# Sheet1.net
KiCad netlist of a schematic drawn in Altium Designer
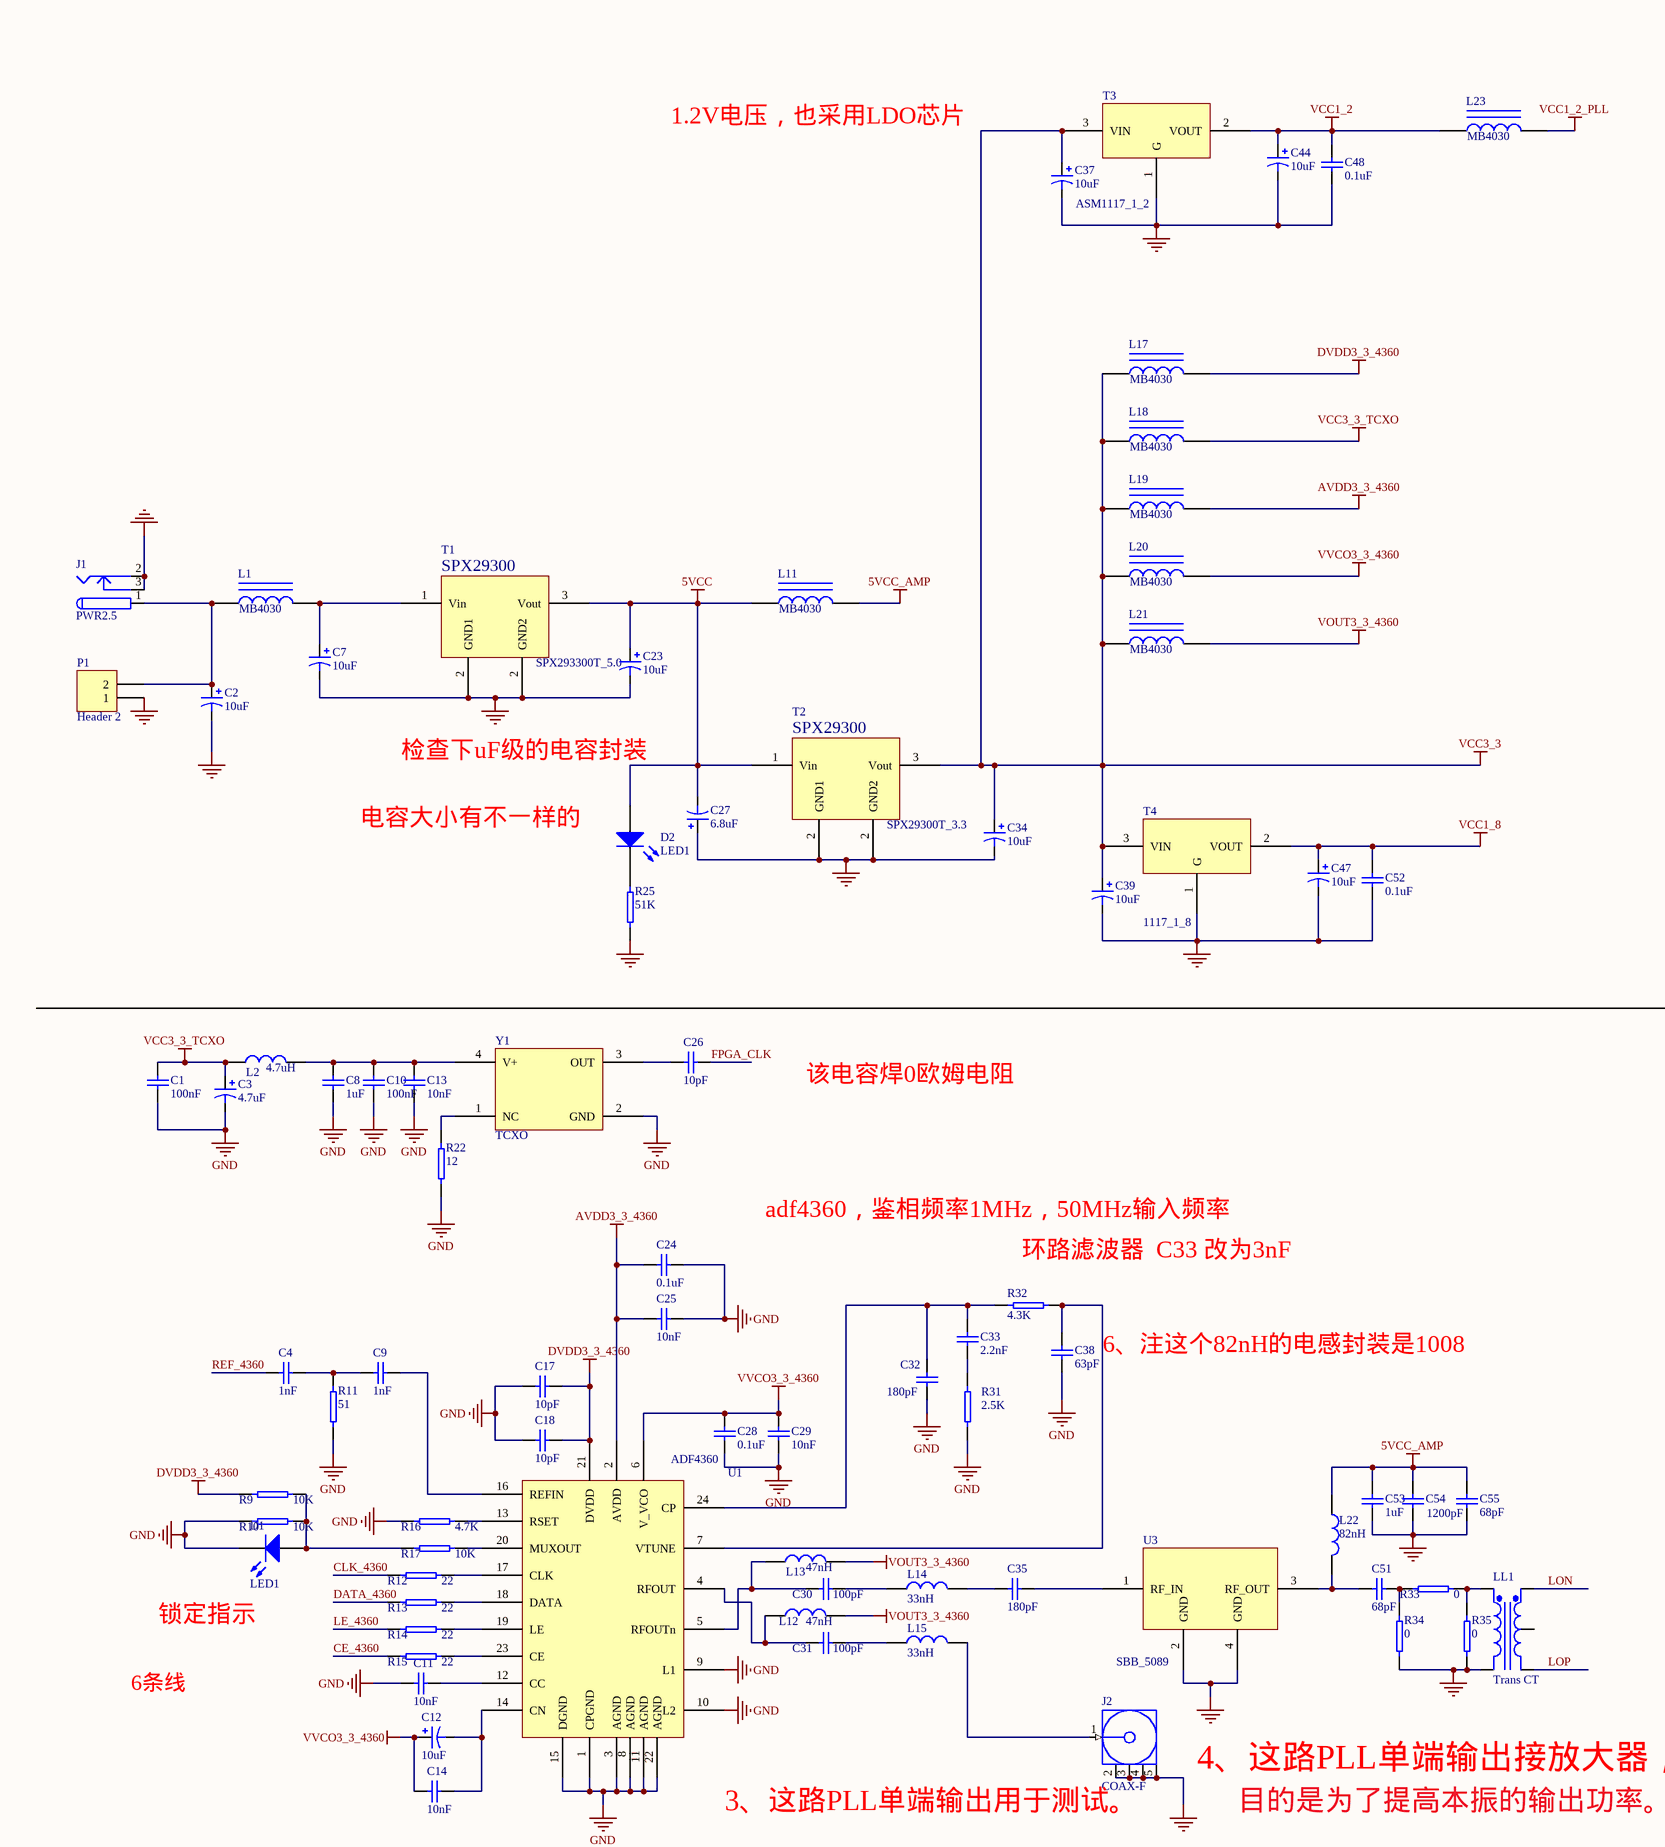
[diagram p0: Sheet1.SchDoc, top left]
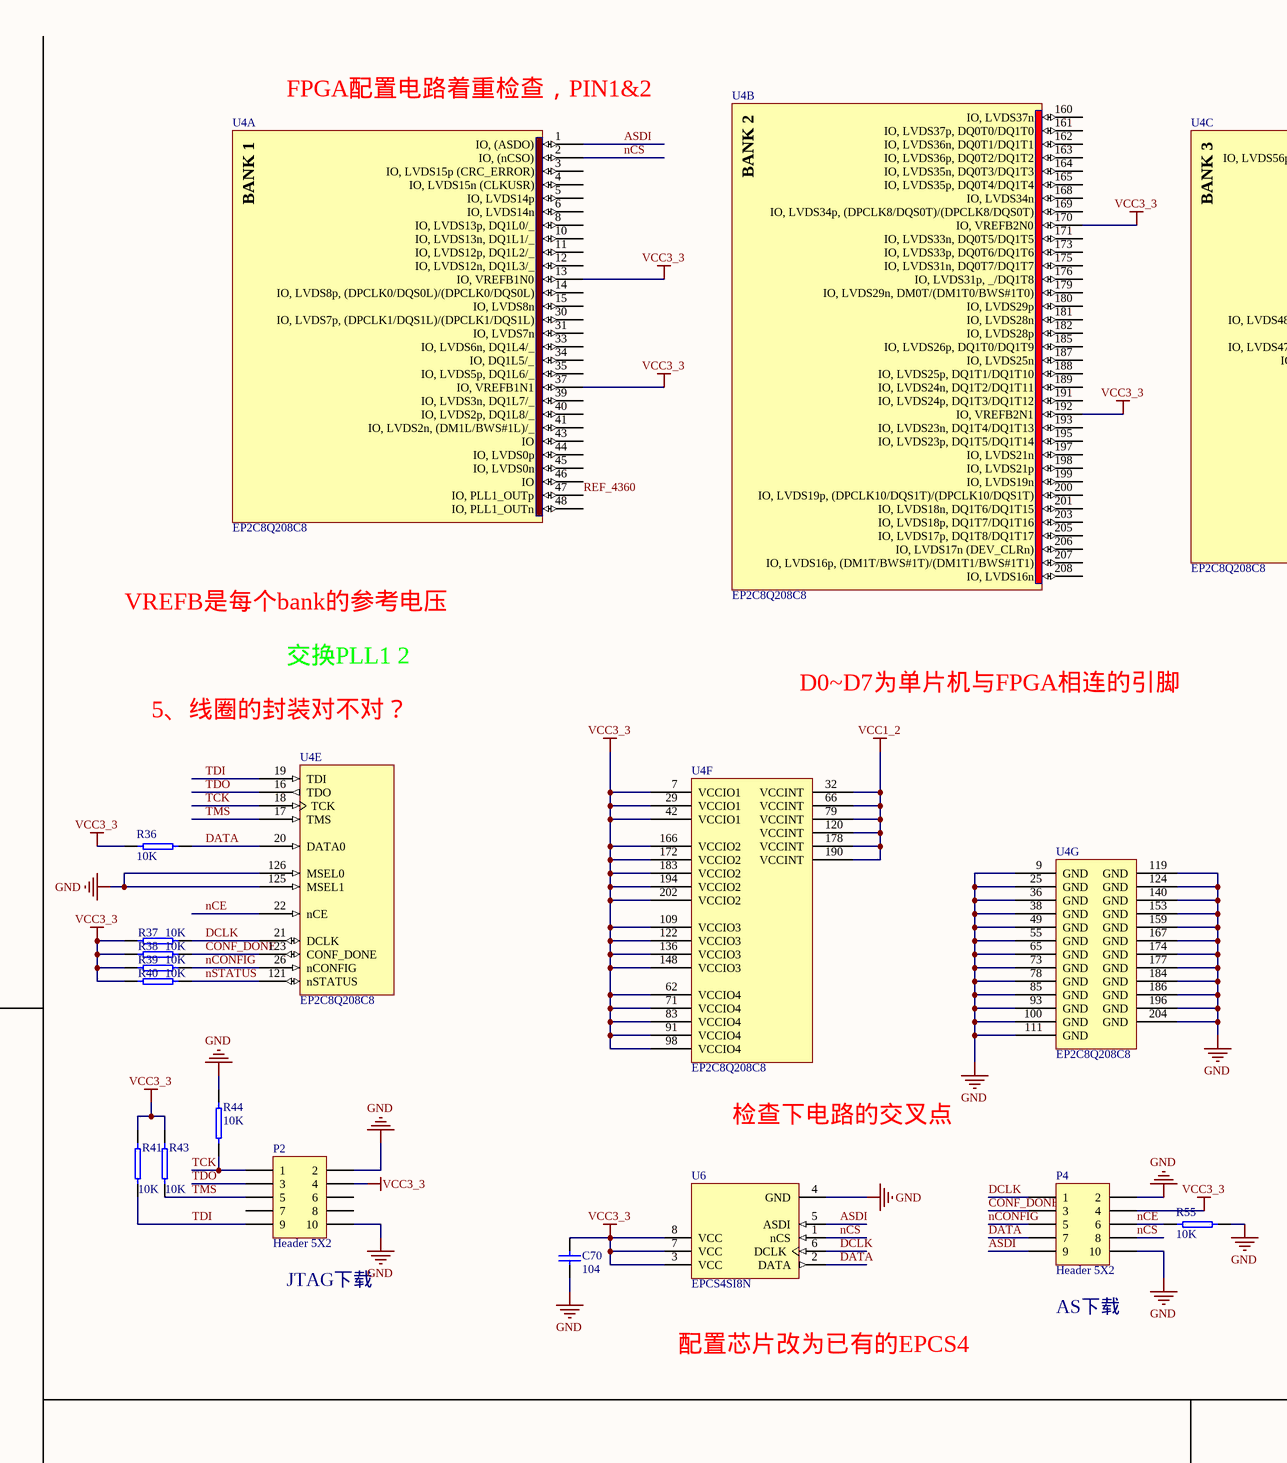
[diagram p1: Sheet1.SchDoc, top middle]
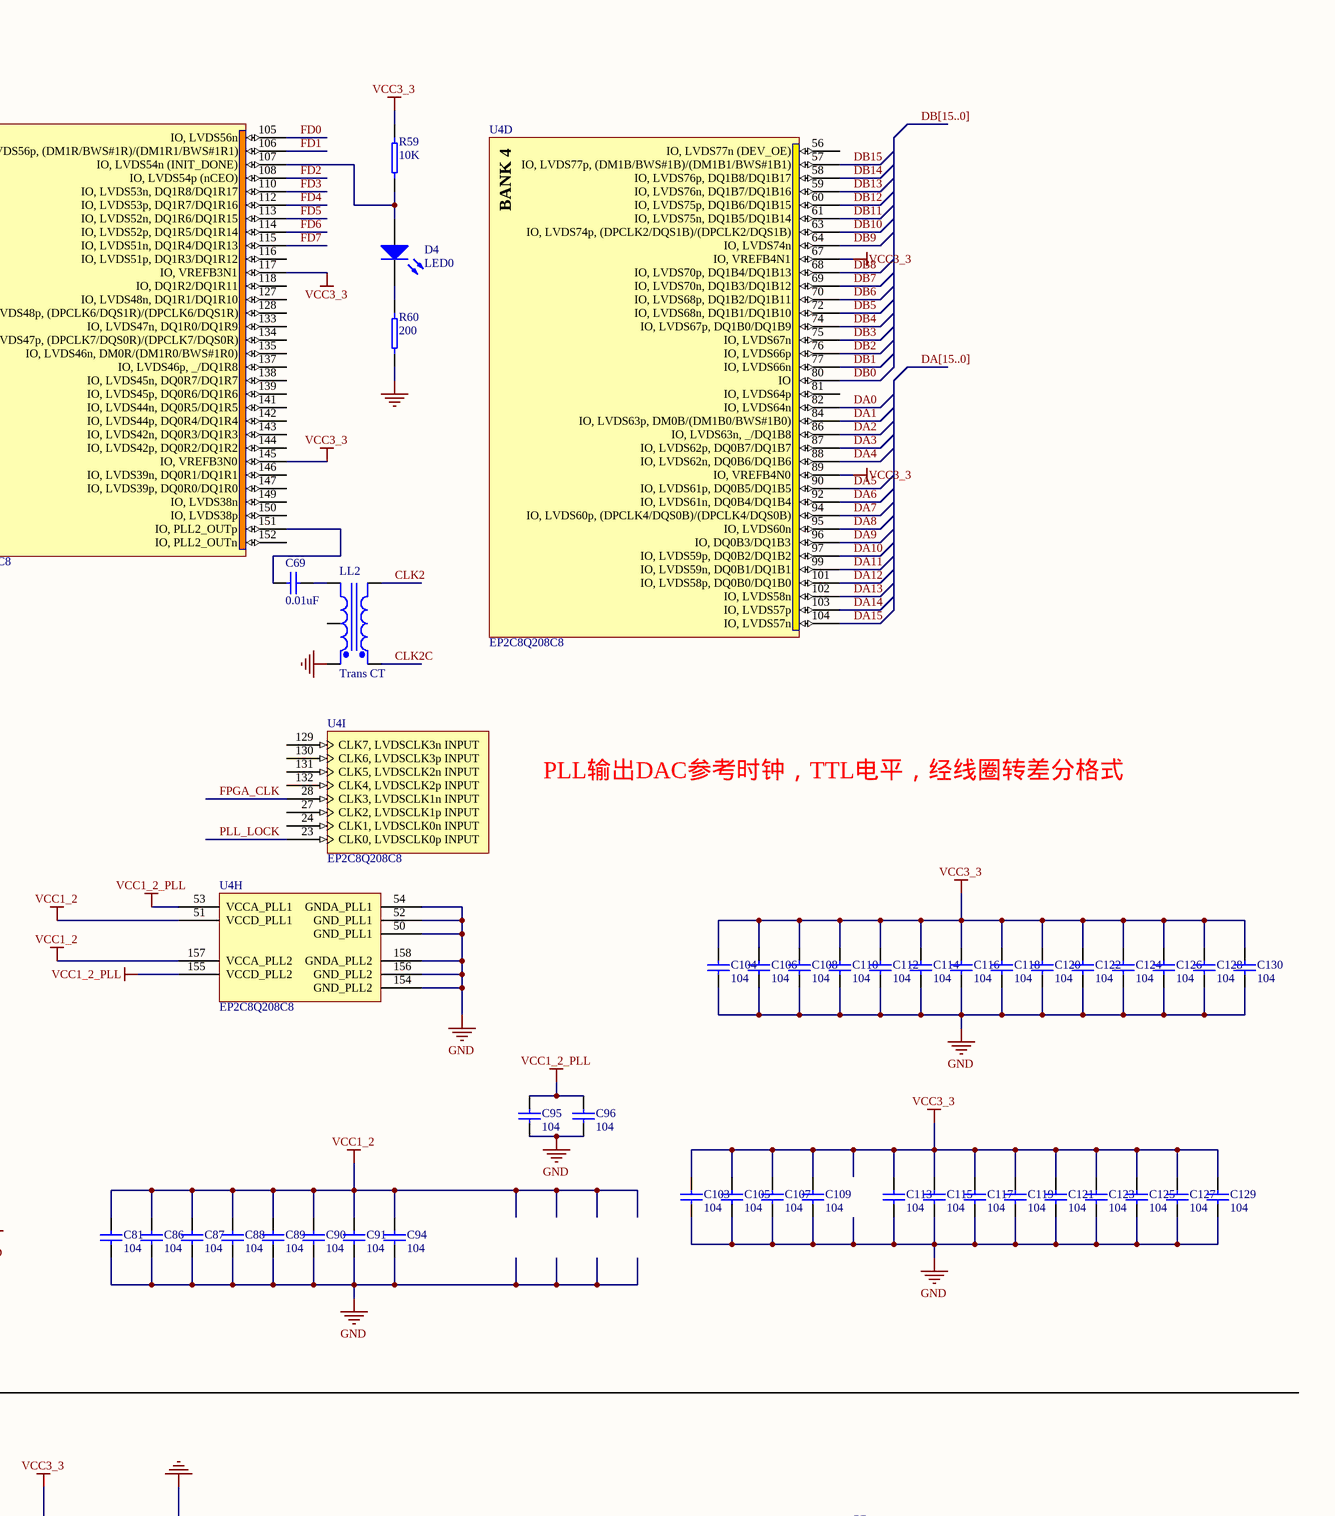
[diagram p2: Sheet1.SchDoc, top right]
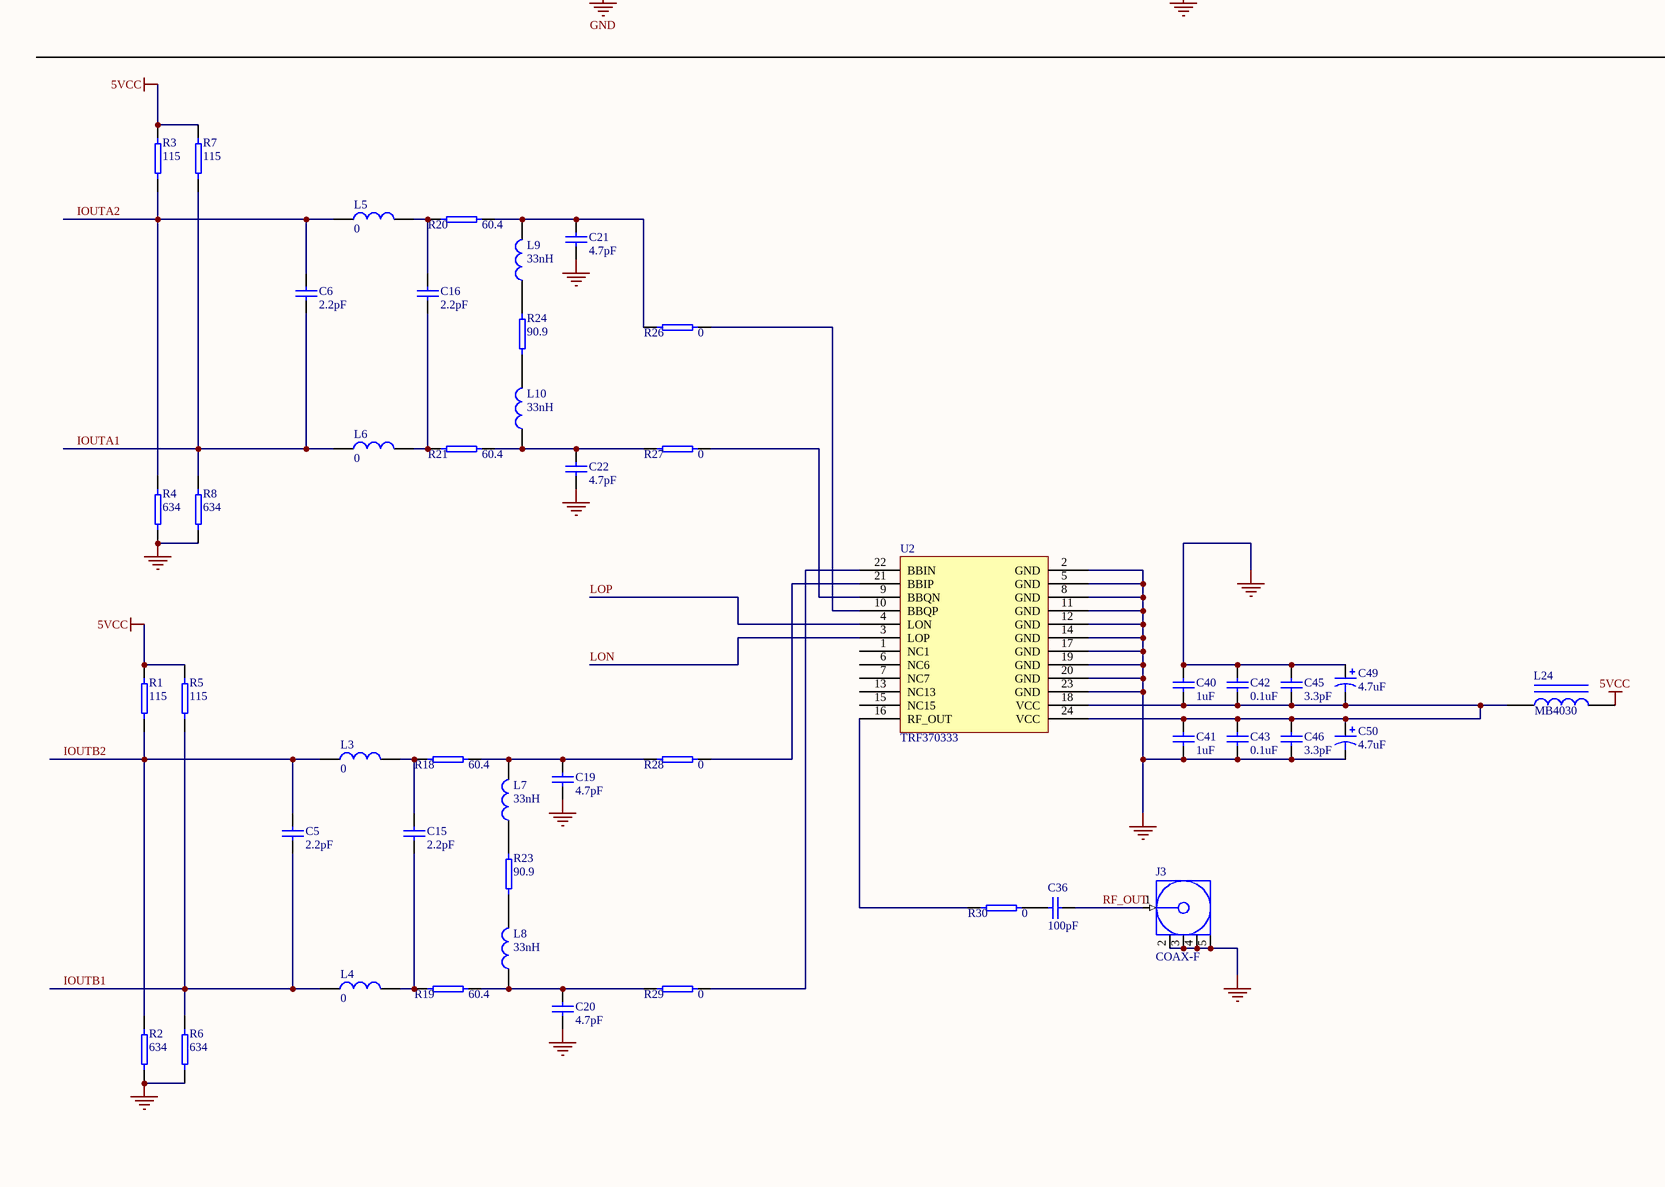
[diagram p3: Sheet1.SchDoc, bottom left]
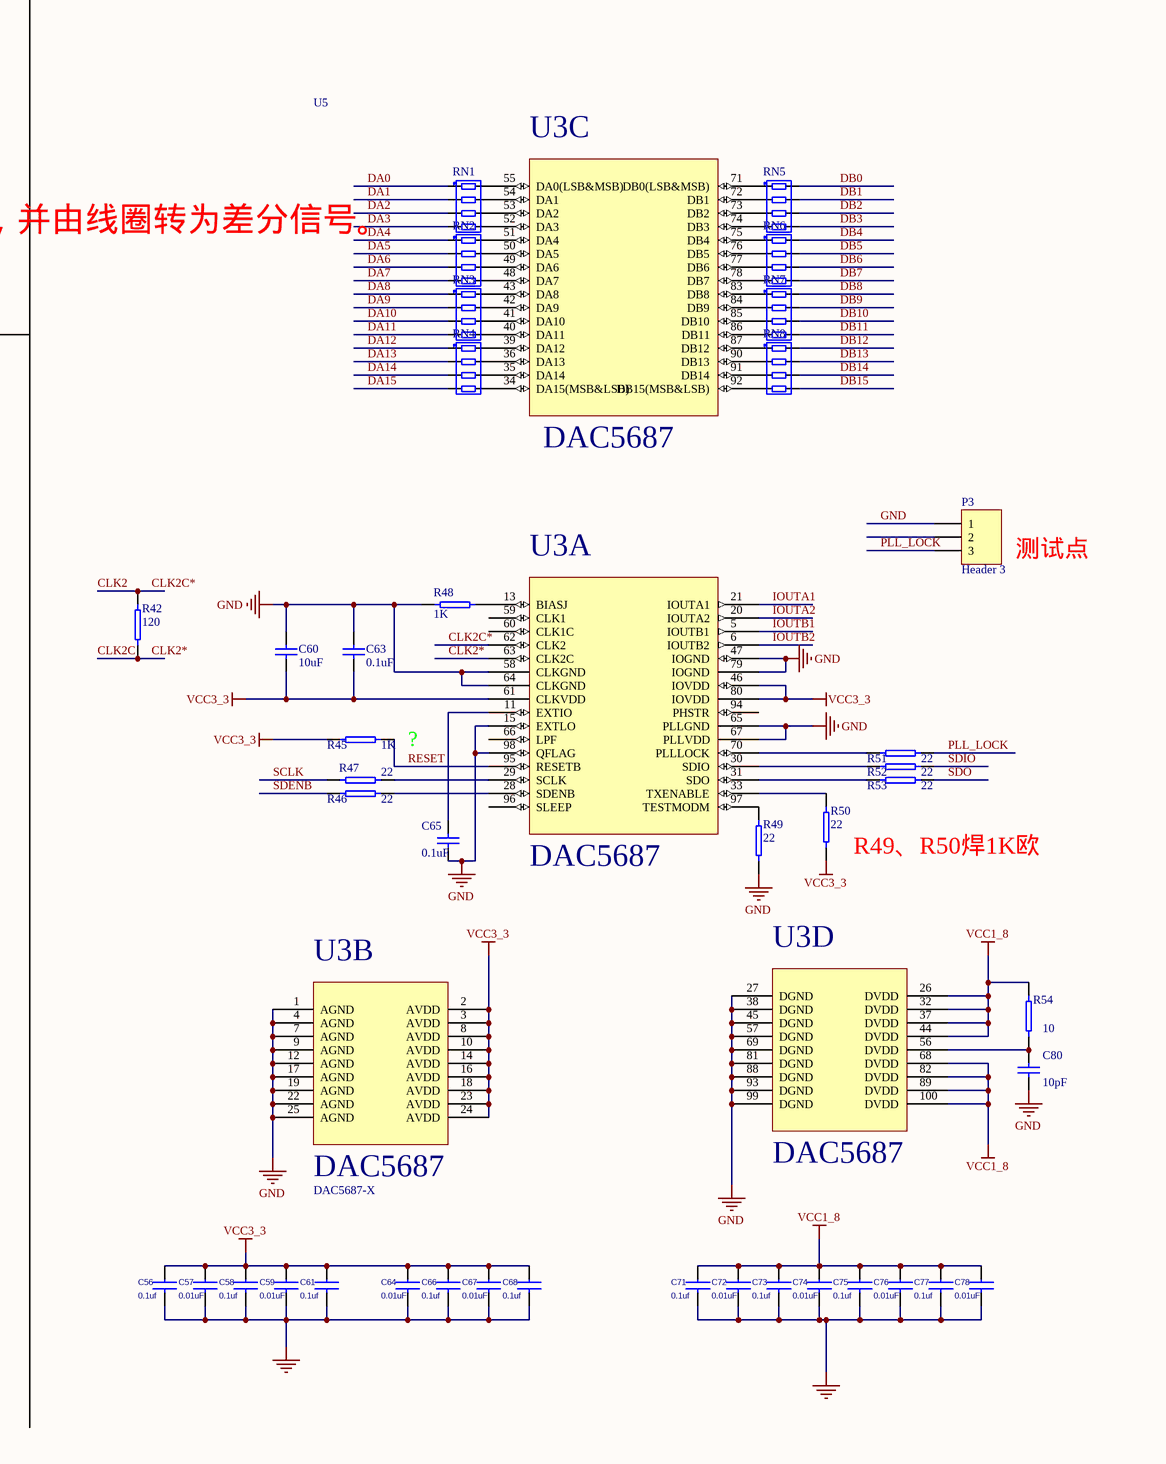
[diagram p4: Sheet1.SchDoc, bottom middle]
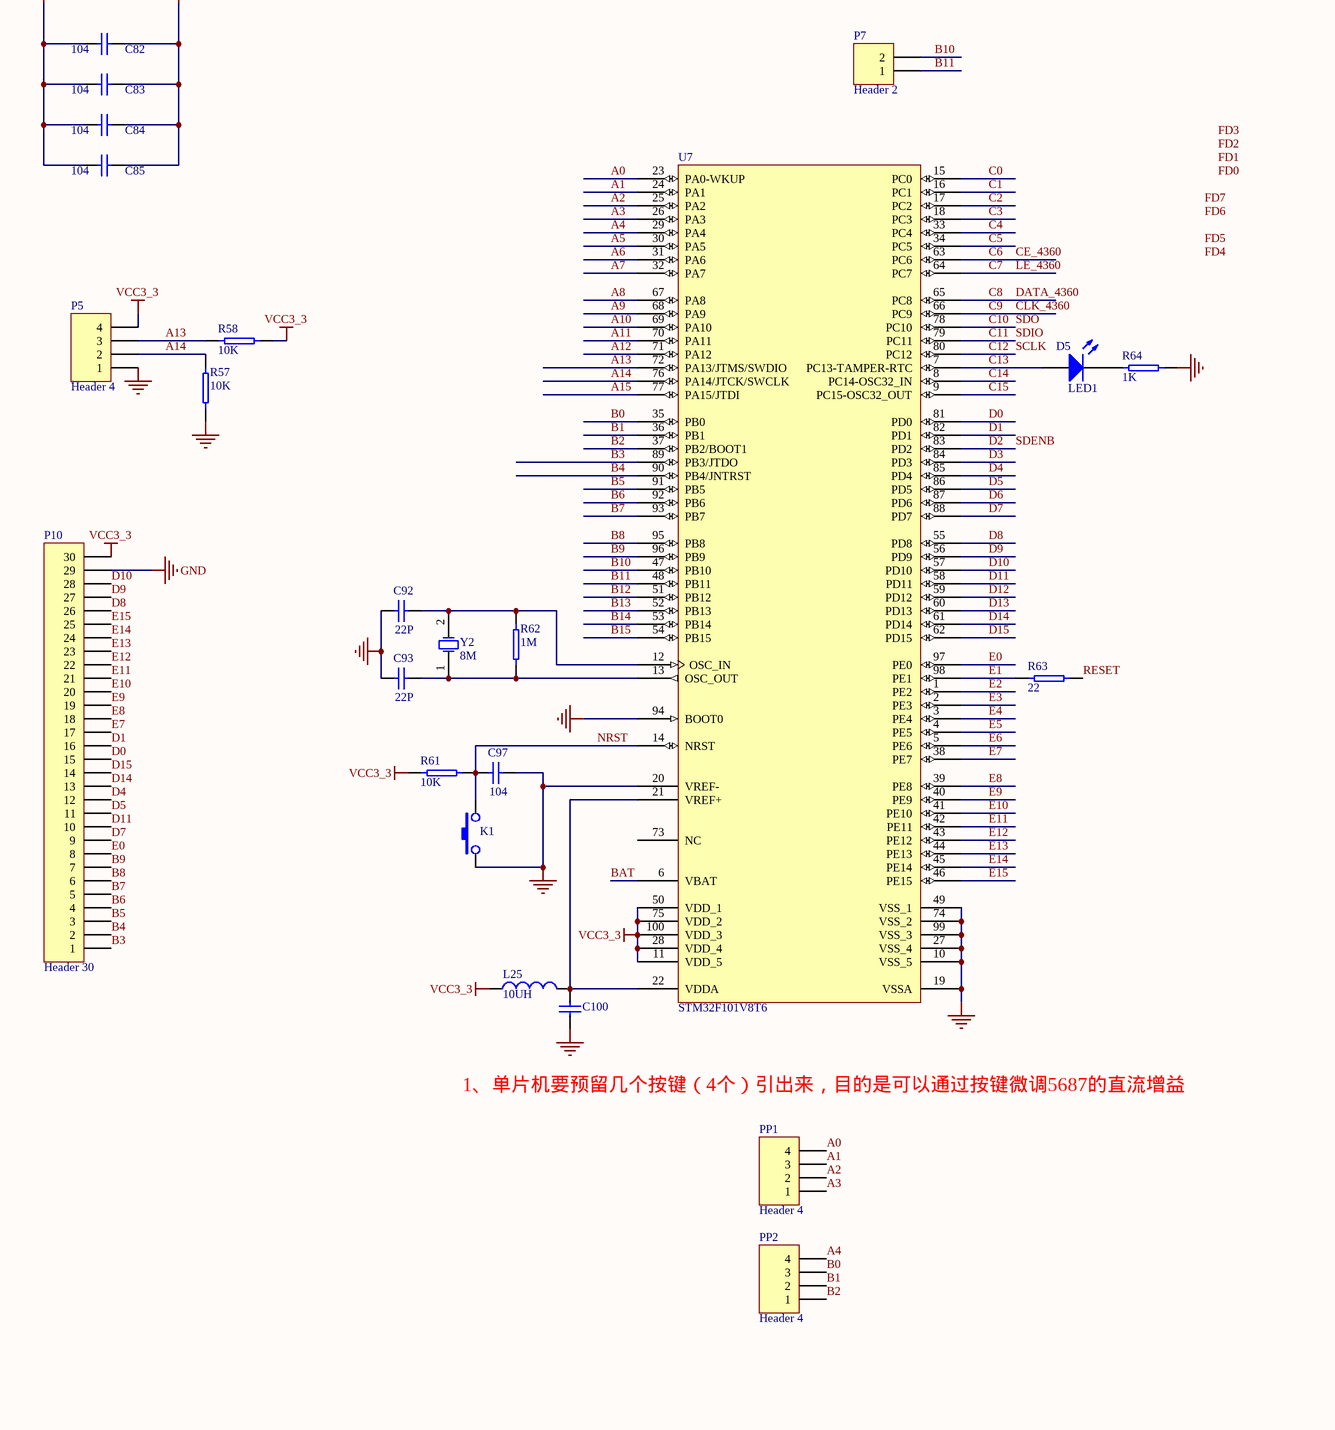
[diagram p5: Sheet1.SchDoc, bottom right]

(export (version "E")
  (design (tool "Eeschema 10.0.6"))
  (components
    (comp (ref "C1")
      (value "100nF")
      (footprint "0805C")
      (description "Capacitor")
      (fields (field (name "Comment") "Cap") (field (name "PUBLISHER") "Altium Limited"))
      (libsource (lib "Miscellaneous Devices") (part "Cap"))
    )
    (comp (ref "C2") (value "10uF") (footprint "1206") (libsource (lib "原理图封装库") (part "CAP+")))
    (comp (ref "C3") (value "4.7uF") (footprint "1206") (libsource (lib "原理图封装库") (part "CAP+")))
    (comp (ref "C4")
      (value "1nF")
      (footprint "0805C")
      (description "Capacitor")
      (fields (field (name "Comment") "Cap") (field (name "PUBLISHER") "Altium Limited"))
      (libsource (lib "Miscellaneous Devices") (part "Cap"))
    )
    (comp (ref "C5")
      (value "2.2pF")
      (footprint "0805C")
      (description "Capacitor")
      (fields (field (name "Comment") "Cap") (field (name "PUBLISHER") "Altium Limited"))
      (libsource (lib "Miscellaneous Devices") (part "Cap"))
    )
    (comp (ref "C6")
      (value "2.2pF")
      (footprint "0805C")
      (description "Capacitor")
      (fields (field (name "Comment") "Cap") (field (name "PUBLISHER") "Altium Limited"))
      (libsource (lib "Miscellaneous Devices") (part "Cap"))
    )
    (comp (ref "C7") (value "10uF") (footprint "1206") (libsource (lib "原理图封装库") (part "CAP+")))
    (comp (ref "C8")
      (value "1uF")
      (footprint "0805C")
      (description "Capacitor")
      (fields (field (name "Comment") "Cap") (field (name "PUBLISHER") "Altium Limited"))
      (libsource (lib "Miscellaneous Devices") (part "Cap"))
    )
    (comp (ref "C9")
      (value "1nF")
      (footprint "0805C")
      (description "Capacitor")
      (fields (field (name "Comment") "Cap") (field (name "PUBLISHER") "Altium Limited"))
      (libsource (lib "Miscellaneous Devices") (part "Cap"))
    )
    (comp (ref "C10")
      (value "100nF")
      (footprint "0805C")
      (description "Capacitor")
      (fields (field (name "Comment") "Cap") (field (name "PUBLISHER") "Altium Limited"))
      (libsource (lib "Miscellaneous Devices") (part "Cap"))
    )
    (comp (ref "C11")
      (value "10nF")
      (footprint "0805C")
      (description "Capacitor")
      (fields (field (name "Comment") "Cap") (field (name "PUBLISHER") "Altium Limited"))
      (libsource (lib "Miscellaneous Devices") (part "Cap"))
    )
    (comp (ref "C12") (value "10uF") (footprint "1206") (libsource (lib "原理图封装库") (part "CAP+")))
    (comp (ref "C13")
      (value "10nF")
      (footprint "0805C")
      (description "Capacitor")
      (fields (field (name "Comment") "Cap") (field (name "PUBLISHER") "Altium Limited"))
      (libsource (lib "Miscellaneous Devices") (part "Cap"))
    )
    (comp (ref "C14")
      (value "10nF")
      (footprint "0805C")
      (description "Capacitor")
      (fields (field (name "Comment") "Cap") (field (name "PUBLISHER") "Altium Limited"))
      (libsource (lib "Miscellaneous Devices") (part "Cap"))
    )
    (comp (ref "C15")
      (value "2.2pF")
      (footprint "0805C")
      (description "Capacitor")
      (fields (field (name "Comment") "Cap") (field (name "PUBLISHER") "Altium Limited"))
      (libsource (lib "Miscellaneous Devices") (part "Cap"))
    )
    (comp (ref "C16")
      (value "2.2pF")
      (footprint "0805C")
      (description "Capacitor")
      (fields (field (name "Comment") "Cap") (field (name "PUBLISHER") "Altium Limited"))
      (libsource (lib "Miscellaneous Devices") (part "Cap"))
    )
    (comp (ref "C17")
      (value "10pF")
      (footprint "0805C")
      (description "Capacitor")
      (fields (field (name "Comment") "Cap") (field (name "PUBLISHER") "Altium Limited"))
      (libsource (lib "Miscellaneous Devices") (part "Cap"))
    )
    (comp (ref "C18")
      (value "10pF")
      (footprint "0805C")
      (description "Capacitor")
      (fields (field (name "Comment") "Cap") (field (name "PUBLISHER") "Altium Limited"))
      (libsource (lib "Miscellaneous Devices") (part "Cap"))
    )
    (comp (ref "C19")
      (value "4.7pF")
      (footprint "0805C")
      (description "Capacitor")
      (fields (field (name "Comment") "Cap") (field (name "PUBLISHER") "Altium Limited"))
      (libsource (lib "Miscellaneous Devices") (part "Cap"))
    )
    (comp (ref "C20")
      (value "4.7pF")
      (footprint "0805C")
      (description "Capacitor")
      (fields (field (name "Comment") "Cap") (field (name "PUBLISHER") "Altium Limited"))
      (libsource (lib "Miscellaneous Devices") (part "Cap"))
    )
    (comp (ref "C21")
      (value "4.7pF")
      (footprint "0805C")
      (description "Capacitor")
      (fields (field (name "Comment") "Cap") (field (name "PUBLISHER") "Altium Limited"))
      (libsource (lib "Miscellaneous Devices") (part "Cap"))
    )
    (comp (ref "C22")
      (value "4.7pF")
      (footprint "0805C")
      (description "Capacitor")
      (fields (field (name "Comment") "Cap") (field (name "PUBLISHER") "Altium Limited"))
      (libsource (lib "Miscellaneous Devices") (part "Cap"))
    )
    (comp (ref "C23") (value "10uF") (footprint "1206") (libsource (lib "原理图封装库") (part "CAP+")))
    (comp (ref "C24")
      (value "0.1uF")
      (footprint "0805C")
      (description "Capacitor")
      (fields (field (name "Comment") "Cap") (field (name "PUBLISHER") "Altium Limited"))
      (libsource (lib "Miscellaneous Devices") (part "Cap"))
    )
    (comp (ref "C25")
      (value "10nF")
      (footprint "0805C")
      (description "Capacitor")
      (fields (field (name "Comment") "Cap") (field (name "PUBLISHER") "Altium Limited"))
      (libsource (lib "Miscellaneous Devices") (part "Cap"))
    )
    (comp (ref "C26")
      (value "10pF")
      (footprint "0805C")
      (description "Capacitor")
      (fields (field (name "Comment") "Cap") (field (name "PUBLISHER") "Altium Limited"))
      (libsource (lib "Miscellaneous Devices") (part "Cap"))
    )
    (comp (ref "C27") (value "6.8uF") (footprint "1206") (libsource (lib "原理图封装库") (part "CAP+")))
    (comp (ref "C28")
      (value "0.1uF")
      (footprint "0805C")
      (description "Capacitor")
      (fields (field (name "Comment") "Cap") (field (name "PUBLISHER") "Altium Limited"))
      (libsource (lib "Miscellaneous Devices") (part "Cap"))
    )
    (comp (ref "C29")
      (value "10nF")
      (footprint "0805C")
      (description "Capacitor")
      (fields (field (name "Comment") "Cap") (field (name "PUBLISHER") "Altium Limited"))
      (libsource (lib "Miscellaneous Devices") (part "Cap"))
    )
    (comp (ref "C30")
      (value "100pF")
      (footprint "0805C")
      (description "Capacitor")
      (fields (field (name "Comment") "Cap") (field (name "PUBLISHER") "Altium Limited"))
      (libsource (lib "Miscellaneous Devices") (part "Cap"))
    )
    (comp (ref "C31")
      (value "100pF")
      (footprint "0805C")
      (description "Capacitor")
      (fields (field (name "Comment") "Cap") (field (name "PUBLISHER") "Altium Limited"))
      (libsource (lib "Miscellaneous Devices") (part "Cap"))
    )
    (comp (ref "C32")
      (value "180pF")
      (footprint "0805C")
      (description "Capacitor")
      (fields (field (name "Comment") "Cap") (field (name "PUBLISHER") "Altium Limited"))
      (libsource (lib "Miscellaneous Devices") (part "Cap"))
    )
    (comp (ref "C33")
      (value "2.2nF")
      (footprint "0805C")
      (description "Capacitor")
      (fields (field (name "Comment") "Cap") (field (name "PUBLISHER") "Altium Limited"))
      (libsource (lib "Miscellaneous Devices") (part "Cap"))
    )
    (comp (ref "C34") (value "10uF") (footprint "1206") (libsource (lib "原理图封装库") (part "CAP+")))
    (comp (ref "C35")
      (value "180pF")
      (footprint "0805C")
      (description "Capacitor")
      (fields (field (name "Comment") "Cap") (field (name "PUBLISHER") "Altium Limited"))
      (libsource (lib "Miscellaneous Devices") (part "Cap"))
    )
    (comp (ref "C36")
      (value "100pF")
      (footprint "0805C")
      (description "Capacitor")
      (fields (field (name "Comment") "Cap") (field (name "PUBLISHER") "Altium Limited"))
      (libsource (lib "Miscellaneous Devices") (part "Cap"))
    )
    (comp (ref "C37") (value "10uF") (footprint "1206") (libsource (lib "原理图封装库") (part "CAP+")))
    (comp (ref "C38")
      (value "63pF")
      (footprint "0805C")
      (description "Capacitor")
      (fields (field (name "Comment") "Cap") (field (name "PUBLISHER") "Altium Limited"))
      (libsource (lib "Miscellaneous Devices") (part "Cap"))
    )
    (comp (ref "C39") (value "10uF") (footprint "1206") (libsource (lib "原理图封装库") (part "CAP+")))
    (comp (ref "C40")
      (value "1uF")
      (footprint "0805C")
      (description "Capacitor")
      (fields (field (name "Comment") "Cap") (field (name "PUBLISHER") "Altium Limited"))
      (libsource (lib "Miscellaneous Devices") (part "Cap"))
    )
    (comp (ref "C41")
      (value "1uF")
      (footprint "0805C")
      (description "Capacitor")
      (fields (field (name "Comment") "Cap") (field (name "PUBLISHER") "Altium Limited"))
      (libsource (lib "Miscellaneous Devices") (part "Cap"))
    )
    (comp (ref "C42")
      (value "0.1uF")
      (footprint "0805C")
      (description "Capacitor")
      (fields (field (name "Comment") "Cap") (field (name "PUBLISHER") "Altium Limited"))
      (libsource (lib "Miscellaneous Devices") (part "Cap"))
    )
    (comp (ref "C43")
      (value "0.1uF")
      (footprint "0805C")
      (description "Capacitor")
      (fields (field (name "Comment") "Cap") (field (name "PUBLISHER") "Altium Limited"))
      (libsource (lib "Miscellaneous Devices") (part "Cap"))
    )
    (comp (ref "C44") (value "10uF") (footprint "1206") (libsource (lib "原理图封装库") (part "CAP+")))
    (comp (ref "C45")
      (value "3.3pF")
      (footprint "0805C")
      (description "Capacitor")
      (fields (field (name "Comment") "Cap") (field (name "PUBLISHER") "Altium Limited"))
      (libsource (lib "Miscellaneous Devices") (part "Cap"))
    )
    (comp (ref "C46")
      (value "3.3pF")
      (footprint "0805C")
      (description "Capacitor")
      (fields (field (name "Comment") "Cap") (field (name "PUBLISHER") "Altium Limited"))
      (libsource (lib "Miscellaneous Devices") (part "Cap"))
    )
    (comp (ref "C47") (value "10uF") (footprint "1206") (libsource (lib "原理图封装库") (part "CAP+")))
    (comp (ref "C48")
      (value "0.1uF")
      (footprint "0805C")
      (description "Capacitor")
      (fields (field (name "Comment") "Cap") (field (name "PUBLISHER") "Altium Limited"))
      (libsource (lib "Miscellaneous Devices") (part "Cap"))
    )
    (comp (ref "C49") (value "4.7uF") (footprint "1206") (libsource (lib "原理图封装库") (part "CAP+")))
    (comp (ref "C50") (value "4.7uF") (footprint "1206") (libsource (lib "原理图封装库") (part "CAP+")))
    (comp (ref "C51")
      (value "68pF")
      (footprint "0805C")
      (description "Capacitor")
      (fields (field (name "Comment") "Cap") (field (name "PUBLISHER") "Altium Limited"))
      (libsource (lib "Miscellaneous Devices") (part "Cap"))
    )
    (comp (ref "C52")
      (value "0.1uF")
      (footprint "0805C")
      (description "Capacitor")
      (fields (field (name "Comment") "Cap") (field (name "PUBLISHER") "Altium Limited"))
      (libsource (lib "Miscellaneous Devices") (part "Cap"))
    )
    (comp (ref "C53")
      (value "1uF")
      (footprint "0805C")
      (description "Capacitor")
      (fields (field (name "Comment") "Cap") (field (name "PUBLISHER") "Altium Limited"))
      (libsource (lib "Miscellaneous Devices") (part "Cap"))
    )
    (comp (ref "C54")
      (value "1200pF")
      (footprint "0805C")
      (description "Capacitor")
      (fields (field (name "Comment") "Cap") (field (name "PUBLISHER") "Altium Limited"))
      (libsource (lib "Miscellaneous Devices") (part "Cap"))
    )
    (comp (ref "C55")
      (value "68pF")
      (footprint "0805C")
      (description "Capacitor")
      (fields (field (name "Comment") "Cap") (field (name "PUBLISHER") "Altium Limited"))
      (libsource (lib "Miscellaneous Devices") (part "Cap"))
    )
    (comp (ref "C56") (value "0.1uf") (footprint "0603") (libsource (lib "*") (part "CAP NP_Dup3")))
    (comp (ref "C57") (value "0.01uF") (footprint "0603") (libsource (lib "*") (part "CAP NP_Dup3")))
    (comp (ref "C58") (value "0.1uf") (footprint "0603") (libsource (lib "*") (part "CAP NP_Dup3")))
    (comp (ref "C59") (value "0.01uF") (footprint "0603") (libsource (lib "*") (part "CAP NP_Dup3")))
    (comp (ref "C60")
      (value "10uF")
      (footprint "0805C")
      (description "Capacitor")
      (fields (field (name "Comment") "Cap") (field (name "PUBLISHER") "Altium Limited"))
      (libsource (lib "Miscellaneous Devices") (part "Cap"))
    )
    (comp (ref "C61") (value "0.1uf") (footprint "0603") (libsource (lib "*") (part "CAP NP_Dup3")))
    (comp (ref "C63")
      (value "0.1uF")
      (footprint "0805C")
      (description "Capacitor")
      (fields (field (name "Comment") "Cap") (field (name "PUBLISHER") "Altium Limited"))
      (libsource (lib "Miscellaneous Devices") (part "Cap"))
    )
    (comp (ref "C64") (value "0.01uF") (footprint "0603") (libsource (lib "*") (part "CAP NP_Dup3")))
    (comp (ref "C65")
      (value "0.1uF")
      (footprint "0805C")
      (description "Capacitor")
      (fields (field (name "Comment") "Cap") (field (name "PUBLISHER") "Altium Limited"))
      (libsource (lib "Miscellaneous Devices") (part "Cap"))
    )
    (comp (ref "C66") (value "0.1uf") (footprint "0603") (libsource (lib "*") (part "CAP NP_Dup3")))
    (comp (ref "C67") (value "0.01uF") (footprint "0603") (libsource (lib "*") (part "CAP NP_Dup3")))
    (comp (ref "C68") (value "0.1uf") (footprint "0603") (libsource (lib "*") (part "CAP NP_Dup3")))
    (comp (ref "C69")
      (value "0.01uF")
      (footprint "0805C")
      (description "Capacitor")
      (fields (field (name "Comment") "Cap") (field (name "PUBLISHER") "Altium Limited"))
      (libsource (lib "Miscellaneous Devices") (part "Cap"))
    )
    (comp (ref "C70")
      (value "104")
      (footprint "0805C")
      (description "Capacitor")
      (fields (field (name "Comment") "Cap") (field (name "PUBLISHER") "Altium Limited"))
      (libsource (lib "Miscellaneous Devices") (part "Cap"))
    )
    (comp (ref "C71") (value "0.1uf") (footprint "0603") (libsource (lib "*") (part "CAP NP_Dup3")))
    (comp (ref "C72") (value "0.01uF") (footprint "0603") (libsource (lib "*") (part "CAP NP_Dup3")))
    (comp (ref "C73") (value "0.1uf") (footprint "0603") (libsource (lib "*") (part "CAP NP_Dup3")))
    (comp (ref "C74") (value "0.01uF") (footprint "0603") (libsource (lib "*") (part "CAP NP_Dup3")))
    (comp (ref "C75") (value "0.1uf") (footprint "0603") (libsource (lib "*") (part "CAP NP_Dup3")))
    (comp (ref "C76") (value "0.01uF") (footprint "0603") (libsource (lib "*") (part "CAP NP_Dup3")))
    (comp (ref "C77") (value "0.1uf") (footprint "0603") (libsource (lib "*") (part "CAP NP_Dup3")))
    (comp (ref "C78") (value "0.01uF") (footprint "0603") (libsource (lib "*") (part "CAP NP_Dup3")))
    (comp (ref "C80")
      (value "10pF")
      (footprint "0805C")
      (description "Capacitor")
      (fields (field (name "Comment") "Cap") (field (name "PUBLISHER") "Altium Limited"))
      (libsource (lib "Miscellaneous Devices") (part "Cap"))
    )
    (comp (ref "C81")
      (value "104")
      (footprint "0603")
      (description "Capacitor")
      (fields (field (name "Comment") "Cap") (field (name "PUBLISHER") "Altium Limited"))
      (libsource (lib "Miscellaneous Devices") (part "Cap"))
    )
    (comp (ref "C82")
      (value "104")
      (footprint "0805C")
      (description "Capacitor")
      (fields (field (name "PUBLISHER") "Altium Limited"))
      (libsource (lib "Miscellaneous Devices") (part "Cap"))
    )
    (comp (ref "C83")
      (value "104")
      (footprint "0805C")
      (description "Capacitor")
      (fields (field (name "PUBLISHER") "Altium Limited"))
      (libsource (lib "Miscellaneous Devices") (part "Cap"))
    )
    (comp (ref "C84")
      (value "104")
      (footprint "0805C")
      (description "Capacitor")
      (fields (field (name "PUBLISHER") "Altium Limited"))
      (libsource (lib "Miscellaneous Devices") (part "Cap"))
    )
    (comp (ref "C85")
      (value "104")
      (footprint "0805C")
      (description "Capacitor")
      (fields (field (name "PUBLISHER") "Altium Limited"))
      (libsource (lib "Miscellaneous Devices") (part "Cap"))
    )
    (comp (ref "C86")
      (value "104")
      (footprint "0603")
      (description "Capacitor")
      (fields (field (name "Comment") "Cap") (field (name "PUBLISHER") "Altium Limited"))
      (libsource (lib "Miscellaneous Devices") (part "Cap"))
    )
    (comp (ref "C87")
      (value "104")
      (footprint "0603")
      (description "Capacitor")
      (fields (field (name "Comment") "Cap") (field (name "PUBLISHER") "Altium Limited"))
      (libsource (lib "Miscellaneous Devices") (part "Cap"))
    )
    (comp (ref "C88")
      (value "104")
      (footprint "0603")
      (description "Capacitor")
      (fields (field (name "Comment") "Cap") (field (name "PUBLISHER") "Altium Limited"))
      (libsource (lib "Miscellaneous Devices") (part "Cap"))
    )
    (comp (ref "C89")
      (value "104")
      (footprint "0603")
      (description "Capacitor")
      (fields (field (name "Comment") "Cap") (field (name "PUBLISHER") "Altium Limited"))
      (libsource (lib "Miscellaneous Devices") (part "Cap"))
    )
    (comp (ref "C90")
      (value "104")
      (footprint "0603")
      (description "Capacitor")
      (fields (field (name "Comment") "Cap") (field (name "PUBLISHER") "Altium Limited"))
      (libsource (lib "Miscellaneous Devices") (part "Cap"))
    )
    (comp (ref "C91")
      (value "104")
      (footprint "0603")
      (description "Capacitor")
      (fields (field (name "Comment") "Cap") (field (name "PUBLISHER") "Altium Limited"))
      (libsource (lib "Miscellaneous Devices") (part "Cap"))
    )
    (comp (ref "C92")
      (value "22P")
      (footprint "0805C")
      (description "Capacitor")
      (fields (field (name "Comment") "Cap") (field (name "PUBLISHER") "Altium Limited"))
      (libsource (lib "Miscellaneous Devices") (part "Cap"))
    )
    (comp (ref "C93")
      (value "22P")
      (footprint "0805C")
      (description "Capacitor")
      (fields (field (name "Comment") "Cap") (field (name "PUBLISHER") "Altium Limited"))
      (libsource (lib "Miscellaneous Devices") (part "Cap"))
    )
    (comp (ref "C94")
      (value "104")
      (footprint "0603")
      (description "Capacitor")
      (fields (field (name "Comment") "Cap") (field (name "PUBLISHER") "Altium Limited"))
      (libsource (lib "Miscellaneous Devices") (part "Cap"))
    )
    (comp (ref "C95")
      (value "104")
      (footprint "0603")
      (description "Capacitor")
      (fields (field (name "Comment") "Cap") (field (name "PUBLISHER") "Altium Limited"))
      (libsource (lib "Miscellaneous Devices") (part "Cap"))
    )
    (comp (ref "C96")
      (value "104")
      (footprint "0603")
      (description "Capacitor")
      (fields (field (name "Comment") "Cap") (field (name "PUBLISHER") "Altium Limited"))
      (libsource (lib "Miscellaneous Devices") (part "Cap"))
    )
    (comp (ref "C97")
      (value "104")
      (footprint "0805C")
      (description "Capacitor")
      (fields (field (name "Comment") "Cap") (field (name "PUBLISHER") "Altium Limited"))
      (libsource (lib "Miscellaneous Devices") (part "Cap"))
    )
    (comp (ref "C100")
      (value "Cap")
      (footprint "0805C")
      (description "Capacitor")
      (fields (field (name "PUBLISHER") "Altium Limited"))
      (libsource (lib "Miscellaneous Devices") (part "Cap"))
    )
    (comp (ref "C103")
      (value "104")
      (footprint "0603")
      (description "Capacitor")
      (fields (field (name "Comment") "Cap") (field (name "PUBLISHER") "Altium Limited"))
      (libsource (lib "Miscellaneous Devices") (part "Cap"))
    )
    (comp (ref "C104")
      (value "104")
      (footprint "0603")
      (description "Capacitor")
      (fields (field (name "Comment") "Cap") (field (name "PUBLISHER") "Altium Limited"))
      (libsource (lib "Miscellaneous Devices") (part "Cap"))
    )
    (comp (ref "C105")
      (value "104")
      (footprint "0603")
      (description "Capacitor")
      (fields (field (name "Comment") "Cap") (field (name "PUBLISHER") "Altium Limited"))
      (libsource (lib "Miscellaneous Devices") (part "Cap"))
    )
    (comp (ref "C106")
      (value "104")
      (footprint "0603")
      (description "Capacitor")
      (fields (field (name "Comment") "Cap") (field (name "PUBLISHER") "Altium Limited"))
      (libsource (lib "Miscellaneous Devices") (part "Cap"))
    )
    (comp (ref "C107")
      (value "104")
      (footprint "0603")
      (description "Capacitor")
      (fields (field (name "Comment") "Cap") (field (name "PUBLISHER") "Altium Limited"))
      (libsource (lib "Miscellaneous Devices") (part "Cap"))
    )
    (comp (ref "C108")
      (value "104")
      (footprint "0603")
      (description "Capacitor")
      (fields (field (name "Comment") "Cap") (field (name "PUBLISHER") "Altium Limited"))
      (libsource (lib "Miscellaneous Devices") (part "Cap"))
    )
    (comp (ref "C109")
      (value "104")
      (footprint "0603")
      (description "Capacitor")
      (fields (field (name "Comment") "Cap") (field (name "PUBLISHER") "Altium Limited"))
      (libsource (lib "Miscellaneous Devices") (part "Cap"))
    )
    (comp (ref "C110")
      (value "104")
      (footprint "0603")
      (description "Capacitor")
      (fields (field (name "Comment") "Cap") (field (name "PUBLISHER") "Altium Limited"))
      (libsource (lib "Miscellaneous Devices") (part "Cap"))
    )
    (comp (ref "C112")
      (value "104")
      (footprint "0603")
      (description "Capacitor")
      (fields (field (name "Comment") "Cap") (field (name "PUBLISHER") "Altium Limited"))
      (libsource (lib "Miscellaneous Devices") (part "Cap"))
    )
    (comp (ref "C113")
      (value "104")
      (footprint "0603")
      (description "Capacitor")
      (fields (field (name "Comment") "Cap") (field (name "PUBLISHER") "Altium Limited"))
      (libsource (lib "Miscellaneous Devices") (part "Cap"))
    )
    (comp (ref "C114")
      (value "104")
      (footprint "0603")
      (description "Capacitor")
      (fields (field (name "Comment") "Cap") (field (name "PUBLISHER") "Altium Limited"))
      (libsource (lib "Miscellaneous Devices") (part "Cap"))
    )
    (comp (ref "C115")
      (value "104")
      (footprint "0603")
      (description "Capacitor")
      (fields (field (name "Comment") "Cap") (field (name "PUBLISHER") "Altium Limited"))
      (libsource (lib "Miscellaneous Devices") (part "Cap"))
    )
    (comp (ref "C116")
      (value "104")
      (footprint "0603")
      (description "Capacitor")
      (fields (field (name "Comment") "Cap") (field (name "PUBLISHER") "Altium Limited"))
      (libsource (lib "Miscellaneous Devices") (part "Cap"))
    )
    (comp (ref "C117")
      (value "104")
      (footprint "0603")
      (description "Capacitor")
      (fields (field (name "Comment") "Cap") (field (name "PUBLISHER") "Altium Limited"))
      (libsource (lib "Miscellaneous Devices") (part "Cap"))
    )
    (comp (ref "C118")
      (value "104")
      (footprint "0603")
      (description "Capacitor")
      (fields (field (name "Comment") "Cap") (field (name "PUBLISHER") "Altium Limited"))
      (libsource (lib "Miscellaneous Devices") (part "Cap"))
    )
    (comp (ref "C119")
      (value "104")
      (footprint "0603")
      (description "Capacitor")
      (fields (field (name "Comment") "Cap") (field (name "PUBLISHER") "Altium Limited"))
      (libsource (lib "Miscellaneous Devices") (part "Cap"))
    )
    (comp (ref "C120")
      (value "104")
      (footprint "0603")
      (description "Capacitor")
      (fields (field (name "Comment") "Cap") (field (name "PUBLISHER") "Altium Limited"))
      (libsource (lib "Miscellaneous Devices") (part "Cap"))
    )
    (comp (ref "C121")
      (value "104")
      (footprint "0603")
      (description "Capacitor")
      (fields (field (name "Comment") "Cap") (field (name "PUBLISHER") "Altium Limited"))
      (libsource (lib "Miscellaneous Devices") (part "Cap"))
    )
    (comp (ref "C122")
      (value "104")
      (footprint "0603")
      (description "Capacitor")
      (fields (field (name "Comment") "Cap") (field (name "PUBLISHER") "Altium Limited"))
      (libsource (lib "Miscellaneous Devices") (part "Cap"))
    )
    (comp (ref "C123")
      (value "104")
      (footprint "0603")
      (description "Capacitor")
      (fields (field (name "Comment") "Cap") (field (name "PUBLISHER") "Altium Limited"))
      (libsource (lib "Miscellaneous Devices") (part "Cap"))
    )
    (comp (ref "C124")
      (value "104")
      (footprint "0603")
      (description "Capacitor")
      (fields (field (name "Comment") "Cap") (field (name "PUBLISHER") "Altium Limited"))
      (libsource (lib "Miscellaneous Devices") (part "Cap"))
    )
    (comp (ref "C125")
      (value "104")
      (footprint "0603")
      (description "Capacitor")
      (fields (field (name "Comment") "Cap") (field (name "PUBLISHER") "Altium Limited"))
      (libsource (lib "Miscellaneous Devices") (part "Cap"))
    )
    (comp (ref "C126")
      (value "104")
      (footprint "0603")
      (description "Capacitor")
      (fields (field (name "Comment") "Cap") (field (name "PUBLISHER") "Altium Limited"))
      (libsource (lib "Miscellaneous Devices") (part "Cap"))
    )
    (comp (ref "C127")
      (value "104")
      (footprint "0603")
      (description "Capacitor")
      (fields (field (name "Comment") "Cap") (field (name "PUBLISHER") "Altium Limited"))
      (libsource (lib "Miscellaneous Devices") (part "Cap"))
    )
    (comp (ref "C128")
      (value "104")
      (footprint "0603")
      (description "Capacitor")
      (fields (field (name "Comment") "Cap") (field (name "PUBLISHER") "Altium Limited"))
      (libsource (lib "Miscellaneous Devices") (part "Cap"))
    )
    (comp (ref "C129")
      (value "104")
      (footprint "0603")
      (description "Capacitor")
      (fields (field (name "Comment") "Cap") (field (name "PUBLISHER") "Altium Limited"))
      (libsource (lib "Miscellaneous Devices") (part "Cap"))
    )
    (comp (ref "C130")
      (value "104")
      (footprint "0603")
      (description "Capacitor")
      (fields (field (name "Comment") "Cap") (field (name "PUBLISHER") "Altium Limited"))
      (libsource (lib "Miscellaneous Devices") (part "Cap"))
    )
    (comp (ref "D1")
      (value "LED1")
      (footprint "0805D")
      (description "Typical INFRARED GaAs LED")
      (fields (field (name "PUBLISHER") "Altium Limited"))
      (libsource (lib "Miscellaneous Devices") (part "LED0"))
    )
    (comp (ref "D2")
      (value "LED1")
      (footprint "0805D")
      (description "Typical INFRARED GaAs LED")
      (fields (field (name "PUBLISHER") "Altium Limited"))
      (libsource (lib "Miscellaneous Devices") (part "LED0"))
    )
    (comp (ref "D4")
      (value "LED0")
      (footprint "0805D")
      (description "Typical INFRARED GaAs LED")
      (fields (field (name "PUBLISHER") "Altium Limited"))
      (libsource (lib "Miscellaneous Devices") (part "LED0"))
    )
    (comp (ref "D5")
      (value "LED1")
      (footprint "0805D")
      (description "Typical INFRARED GaAs LED")
      (fields (field (name "PUBLISHER") "Altium Limited"))
      (libsource (lib "Miscellaneous Devices") (part "LED0"))
    )
    (comp (ref "J1")
      (value "PWR2.5")
      (footprint "DS-3")
      (description "Low Voltage Power Supply Connector")
      (fields (field (name "PUBLISHER") "Altium Limited"))
      (libsource (lib "Miscellaneous Connectors") (part "PWR2.5"))
    )
    (comp (ref "J2")
      (value "COAX-F")
      (footprint "MCX5.08-H5")
      (fields (field (name "PUBLISHER") "Altium Limited"))
      (libsource (lib "Miscellaneous Connectors") (part "COAX-F"))
    )
    (comp (ref "J3")
      (value "COAX-F")
      (footprint "MCX5.08-H5")
      (fields (field (name "PUBLISHER") "Altium Limited"))
      (libsource (lib "Miscellaneous Connectors") (part "COAX-F"))
    )
    (comp (ref "K1") (value "BUTTON") (footprint "k1") (libsource (lib "原理图封装库") (part "BUTTON")))
    (comp (ref "L1")
      (value "MB4030")
      (footprint "0805L")
      (description "Magnetic-Core Inductor")
      (fields (field (name "Comment") "Inductor Iron") (field (name "PUBLISHER") "Altium Limited"))
      (libsource (lib "Miscellaneous Devices") (part "Inductor Iron"))
    )
    (comp (ref "L2") (value "4.7uH") (footprint "0805L") (libsource (lib "原理图封装库") (part "H")))
    (comp (ref "L3") (value "0") (footprint "0805L") (libsource (lib "原理图封装库") (part "H")))
    (comp (ref "L4") (value "0") (footprint "0805L") (libsource (lib "原理图封装库") (part "H")))
    (comp (ref "L5") (value "0") (footprint "0805L") (libsource (lib "原理图封装库") (part "H")))
    (comp (ref "L6") (value "0") (footprint "0805L") (libsource (lib "原理图封装库") (part "H")))
    (comp (ref "L7") (value "33nH") (footprint "0805L") (libsource (lib "原理图封装库") (part "H")))
    (comp (ref "L8") (value "33nH") (footprint "0805L") (libsource (lib "原理图封装库") (part "H")))
    (comp (ref "L9") (value "33nH") (footprint "0805L") (libsource (lib "原理图封装库") (part "H")))
    (comp (ref "L10") (value "33nH") (footprint "0805L") (libsource (lib "原理图封装库") (part "H")))
    (comp (ref "L11")
      (value "MB4030")
      (footprint "0805L")
      (description "Magnetic-Core Inductor")
      (fields (field (name "Comment") "Inductor Iron") (field (name "PUBLISHER") "Altium Limited"))
      (libsource (lib "Miscellaneous Devices") (part "Inductor Iron"))
    )
    (comp (ref "L12") (value "47nH") (footprint "0805L") (libsource (lib "原理图封装库") (part "H")))
    (comp (ref "L13") (value "47nH") (footprint "0805L") (libsource (lib "原理图封装库") (part "H")))
    (comp (ref "L14") (value "33nH") (footprint "0805L") (libsource (lib "原理图封装库") (part "H")))
    (comp (ref "L15") (value "33nH") (footprint "0805L") (libsource (lib "原理图封装库") (part "H")))
    (comp (ref "L17")
      (value "MB4030")
      (footprint "0805L")
      (description "Magnetic-Core Inductor")
      (fields (field (name "Comment") "Inductor Iron") (field (name "PUBLISHER") "Altium Limited"))
      (libsource (lib "Miscellaneous Devices") (part "Inductor Iron"))
    )
    (comp (ref "L18")
      (value "MB4030")
      (footprint "0805L")
      (description "Magnetic-Core Inductor")
      (fields (field (name "Comment") "Inductor Iron") (field (name "PUBLISHER") "Altium Limited"))
      (libsource (lib "Miscellaneous Devices") (part "Inductor Iron"))
    )
    (comp (ref "L19")
      (value "MB4030")
      (footprint "0805L")
      (description "Magnetic-Core Inductor")
      (fields (field (name "Comment") "Inductor Iron") (field (name "PUBLISHER") "Altium Limited"))
      (libsource (lib "Miscellaneous Devices") (part "Inductor Iron"))
    )
    (comp (ref "L20")
      (value "MB4030")
      (footprint "0805L")
      (description "Magnetic-Core Inductor")
      (fields (field (name "Comment") "Inductor Iron") (field (name "PUBLISHER") "Altium Limited"))
      (libsource (lib "Miscellaneous Devices") (part "Inductor Iron"))
    )
    (comp (ref "L21")
      (value "MB4030")
      (footprint "0805L")
      (description "Magnetic-Core Inductor")
      (fields (field (name "Comment") "Inductor Iron") (field (name "PUBLISHER") "Altium Limited"))
      (libsource (lib "Miscellaneous Devices") (part "Inductor Iron"))
    )
    (comp (ref "L22") (value "82nH") (footprint "0805L") (libsource (lib "原理图封装库") (part "H")))
    (comp (ref "L23")
      (value "MB4030")
      (footprint "0805L")
      (description "Magnetic-Core Inductor")
      (fields (field (name "Comment") "Inductor Iron") (field (name "PUBLISHER") "Altium Limited"))
      (libsource (lib "Miscellaneous Devices") (part "Inductor Iron"))
    )
    (comp (ref "L24")
      (value "MB4030")
      (footprint "0805L")
      (description "Magnetic-Core Inductor")
      (fields (field (name "Comment") "Inductor Iron") (field (name "PUBLISHER") "Altium Limited"))
      (libsource (lib "Miscellaneous Devices") (part "Inductor Iron"))
    )
    (comp (ref "L25")
      (value "10UH")
      (footprint "0805L")
      (description "Inductor")
      (fields (field (name "PUBLISHER") "Altium Limited"))
      (libsource (lib "Miscellaneous Devices") (part "Inductor"))
    )
    (comp (ref "LL1")
      (value "Trans CT")
      (footprint "SOT23-5")
      (description "Center-Tapped Transformer (Coupled Inductor Model)")
      (fields (field (name "PUBLISHER") "Altium Limited"))
      (libsource (lib "Miscellaneous Devices") (part "Trans CT"))
    )
    (comp (ref "LL2")
      (value "Trans CT")
      (footprint "SOT23-5")
      (description "Center-Tapped Transformer (Coupled Inductor Model)")
      (fields (field (name "PUBLISHER") "Altium Limited"))
      (libsource (lib "Miscellaneous Devices") (part "Trans CT"))
    )
    (comp (ref "P1")
      (value "Header 2")
      (footprint "SIP2-T0")
      (description "Header, 2-Pin")
      (fields (field (name "PUBLISHER") "Altium Limited"))
      (libsource (lib "Miscellaneous Connectors") (part "Header 2"))
    )
    (comp (ref "P2")
      (value "Header 5X2")
      (footprint "IDC5")
      (description "Header, 5-Pin, Dual row")
      (fields (field (name "PUBLISHER") "Altium Limited"))
      (libsource (lib "Miscellaneous Connectors") (part "Header 5X2"))
    )
    (comp (ref "P3")
      (value "Header 3")
      (footprint "SIP3-T0")
      (description "Header, 3-Pin")
      (fields (field (name "PUBLISHER") "Altium Limited"))
      (libsource (lib "Miscellaneous Connectors") (part "Header 3"))
    )
    (comp (ref "P4")
      (value "Header 5X2")
      (footprint "IDC5")
      (description "Header, 5-Pin, Dual row")
      (fields (field (name "PUBLISHER") "Altium Limited"))
      (libsource (lib "Miscellaneous Connectors") (part "Header 5X2"))
    )
    (comp (ref "P5")
      (value "Header 4")
      (footprint "SIP4-T0")
      (description "Header, 4-Pin")
      (fields (field (name "PUBLISHER") "Altium Limited"))
      (libsource (lib "Miscellaneous Connectors") (part "Header 4"))
    )
    (comp (ref "P7")
      (value "Header 2")
      (footprint "SIP2-T0")
      (description "Header, 2-Pin")
      (fields (field (name "PUBLISHER") "Altium Limited"))
      (libsource (lib "Miscellaneous Connectors") (part "Header 2"))
    )
    (comp (ref "P10")
      (value "Header 30")
      (footprint "FFC_30P_0.5MM")
      (description "Header, 30-Pin")
      (fields (field (name "PUBLISHER") "Altium Limited"))
      (libsource (lib "rhyme-SCH") (part "Header 30"))
    )
    (comp (ref "PP1")
      (value "Header 4")
      (footprint "SIP4-T0")
      (description "Header, 4-Pin")
      (fields (field (name "PUBLISHER") "Altium Limited"))
      (libsource (lib "Miscellaneous Connectors") (part "Header 4"))
    )
    (comp (ref "PP2")
      (value "Header 4")
      (footprint "SIP4-T0")
      (description "Header, 4-Pin")
      (fields (field (name "PUBLISHER") "Altium Limited"))
      (libsource (lib "Miscellaneous Connectors") (part "Header 4"))
    )
    (comp (ref "R1") (value "115") (footprint "0805") (libsource (lib "原理图封装库") (part "RES")))
    (comp (ref "R2") (value "634") (footprint "0805") (libsource (lib "原理图封装库") (part "RES")))
    (comp (ref "R3") (value "115") (footprint "0805") (libsource (lib "原理图封装库") (part "RES")))
    (comp (ref "R4") (value "634") (footprint "0805") (libsource (lib "原理图封装库") (part "RES")))
    (comp (ref "R5") (value "115") (footprint "0805") (libsource (lib "原理图封装库") (part "RES")))
    (comp (ref "R6") (value "634") (footprint "0805") (libsource (lib "原理图封装库") (part "RES")))
    (comp (ref "R7") (value "115") (footprint "0805") (libsource (lib "原理图封装库") (part "RES")))
    (comp (ref "R8") (value "634") (footprint "0805") (libsource (lib "原理图封装库") (part "RES")))
    (comp (ref "R9") (value "10K") (footprint "0805") (libsource (lib "原理图封装库") (part "RES")))
    (comp (ref "R10") (value "10K") (footprint "0805") (libsource (lib "原理图封装库") (part "RES")))
    (comp (ref "R11") (value "51") (footprint "0805") (libsource (lib "原理图封装库") (part "RES")))
    (comp (ref "R12") (value "22") (footprint "0805") (libsource (lib "原理图封装库") (part "RES")))
    (comp (ref "R13") (value "22") (footprint "0805") (libsource (lib "原理图封装库") (part "RES")))
    (comp (ref "R14") (value "22") (footprint "0805") (libsource (lib "原理图封装库") (part "RES")))
    (comp (ref "R15") (value "22") (footprint "0805") (libsource (lib "原理图封装库") (part "RES")))
    (comp (ref "R16") (value "4.7K") (footprint "0805") (libsource (lib "原理图封装库") (part "RES")))
    (comp (ref "R17") (value "10K") (footprint "0805") (libsource (lib "原理图封装库") (part "RES")))
    (comp (ref "R18") (value "60.4") (footprint "0805") (libsource (lib "原理图封装库") (part "RES")))
    (comp (ref "R19") (value "60.4") (footprint "0805") (libsource (lib "原理图封装库") (part "RES")))
    (comp (ref "R20") (value "60.4") (footprint "0805") (libsource (lib "原理图封装库") (part "RES")))
    (comp (ref "R21") (value "60.4") (footprint "0805") (libsource (lib "原理图封装库") (part "RES")))
    (comp (ref "R22") (value "12") (footprint "0805") (libsource (lib "原理图封装库") (part "RES")))
    (comp (ref "R23") (value "90.9") (footprint "0805") (libsource (lib "原理图封装库") (part "RES")))
    (comp (ref "R24") (value "90.9") (footprint "0805") (libsource (lib "原理图封装库") (part "RES")))
    (comp (ref "R25") (value "51K") (footprint "0805") (libsource (lib "原理图封装库") (part "RES")))
    (comp (ref "R26") (value "0") (footprint "0805") (libsource (lib "原理图封装库") (part "RES")))
    (comp (ref "R27") (value "0") (footprint "0805") (libsource (lib "原理图封装库") (part "RES")))
    (comp (ref "R28") (value "0") (footprint "0805") (libsource (lib "原理图封装库") (part "RES")))
    (comp (ref "R29") (value "0") (footprint "0805") (libsource (lib "原理图封装库") (part "RES")))
    (comp (ref "R30") (value "0") (footprint "0805") (libsource (lib "原理图封装库") (part "RES")))
    (comp (ref "R31") (value "2.5K") (footprint "0805") (libsource (lib "原理图封装库") (part "RES")))
    (comp (ref "R32") (value "4.3K") (footprint "0805") (libsource (lib "原理图封装库") (part "RES")))
    (comp (ref "R33") (value "0") (footprint "0805") (libsource (lib "原理图封装库") (part "RES")))
    (comp (ref "R34") (value "0") (footprint "0805") (libsource (lib "原理图封装库") (part "RES")))
    (comp (ref "R35") (value "0") (footprint "0805") (libsource (lib "原理图封装库") (part "RES")))
    (comp (ref "R36") (value "10K") (footprint "0805") (libsource (lib "原理图封装库") (part "RES")))
    (comp (ref "R37") (value "10K") (footprint "0805") (libsource (lib "原理图封装库") (part "RES")))
    (comp (ref "R38") (value "10K") (footprint "0805") (libsource (lib "原理图封装库") (part "RES")))
    (comp (ref "R39") (value "10K") (footprint "0805") (libsource (lib "原理图封装库") (part "RES")))
    (comp (ref "R40") (value "10K") (footprint "0805") (libsource (lib "原理图封装库") (part "RES")))
    (comp (ref "R41") (value "10K") (footprint "0805") (libsource (lib "原理图封装库") (part "RES")))
    (comp (ref "R42") (value "120") (footprint "0805") (libsource (lib "原理图封装库") (part "RES")))
    (comp (ref "R43") (value "10K") (footprint "0805") (libsource (lib "原理图封装库") (part "RES")))
    (comp (ref "R44") (value "10K") (footprint "0805") (libsource (lib "原理图封装库") (part "RES")))
    (comp (ref "R45") (value "1K") (footprint "0805") (libsource (lib "原理图封装库") (part "RES")))
    (comp (ref "R46") (value "22") (footprint "0805") (libsource (lib "原理图封装库") (part "RES")))
    (comp (ref "R47") (value "22") (footprint "0805") (libsource (lib "原理图封装库") (part "RES")))
    (comp (ref "R48") (value "1K") (footprint "0805") (libsource (lib "原理图封装库") (part "RES")))
    (comp (ref "R49") (value "22") (footprint "0805") (libsource (lib "原理图封装库") (part "RES")))
    (comp (ref "R50") (value "22") (footprint "0805") (libsource (lib "原理图封装库") (part "RES")))
    (comp (ref "R51") (value "22") (footprint "0805") (libsource (lib "原理图封装库") (part "RES")))
    (comp (ref "R52") (value "22") (footprint "0805") (libsource (lib "原理图封装库") (part "RES")))
    (comp (ref "R53") (value "22") (footprint "0805") (libsource (lib "原理图封装库") (part "RES")))
    (comp (ref "R54") (value "10") (footprint "0805") (libsource (lib "原理图封装库") (part "RES")))
    (comp (ref "R55") (value "10K") (footprint "0805") (libsource (lib "原理图封装库") (part "RES")))
    (comp (ref "R57") (value "10K") (footprint "0805") (libsource (lib "原理图封装库") (part "RES")))
    (comp (ref "R58") (value "10K") (footprint "0805") (libsource (lib "原理图封装库") (part "RES")))
    (comp (ref "R59") (value "10K") (footprint "0805") (libsource (lib "原理图封装库") (part "RES")))
    (comp (ref "R60") (value "200") (footprint "0805") (libsource (lib "原理图封装库") (part "RES")))
    (comp (ref "R61") (value "10K") (footprint "0805") (libsource (lib "原理图封装库") (part "RES")))
    (comp (ref "R62") (value "1M") (footprint "0805") (libsource (lib "原理图封装库") (part "RES")))
    (comp (ref "R63") (value "22") (footprint "0805") (libsource (lib "原理图封装库") (part "RES")))
    (comp (ref "R64") (value "1K") (footprint "0805") (libsource (lib "原理图封装库") (part "RES")))
    (comp (ref "RN1") (value "RES*4") (footprint "0603*4反") (libsource (lib "原理图封装库") (part "RES*4")))
    (comp (ref "RN2") (value "RES*4") (footprint "0603*4反") (libsource (lib "原理图封装库") (part "RES*4")))
    (comp (ref "RN3") (value "RES*4") (footprint "0603*4反") (libsource (lib "原理图封装库") (part "RES*4")))
    (comp (ref "RN4") (value "RES*4") (footprint "0603*4反") (libsource (lib "原理图封装库") (part "RES*4")))
    (comp (ref "RN5") (value "RES*4") (footprint "0603*4反") (libsource (lib "原理图封装库") (part "RES*4")))
    (comp (ref "RN6") (value "RES*4") (footprint "0603*4反") (libsource (lib "原理图封装库") (part "RES*4")))
    (comp (ref "RN7") (value "RES*4") (footprint "0603*4反") (libsource (lib "原理图封装库") (part "RES*4")))
    (comp (ref "RN8") (value "RES*4") (footprint "0603*4反") (libsource (lib "原理图封装库") (part "RES*4")))
    (comp (ref "T1")
      (value "SPX293300T_5.0")
      (footprint "TO-263")
      (libsource (lib "原理图封装库") (part "SPX29300T"))
    )
    (comp (ref "T2")
      (value "SPX29300T_3.3")
      (footprint "TO-263")
      (libsource (lib "原理图封装库") (part "SPX29300T"))
    )
    (comp (ref "T3") (value "ASM1117_1_2") (footprint "SOT-223") (libsource (lib "原理图封装库") (part "117")))
    (comp (ref "T4") (value "1117_1_8") (footprint "SOT-223") (libsource (lib "原理图封装库") (part "117")))
    (comp (ref "U1") (value "ADF4360") (footprint "QFN24") (libsource (lib "原理图封装库") (part "ADF4360")))
    (comp (ref "U2") (value "TRF370333") (footprint "QFN24") (libsource (lib "原理图封装库") (part "TRF370333")))
    (comp (ref "U3")
      (value "SBB_5089")
      (footprint "SBB_5089")
      (libsource (lib "rhyme-SCH") (part "SBB_5089"))
    )
    (comp (ref "U4")
      (value "EP2C8Q208C8")
      (footprint "FPGA208")
      (description "Cyclone II Family, 1.2V FPGA, 138 I/O Pins, 2 PLLs, 208-Pin PQFP, Speed Grade 8, Commercial Grade")
      (fields (field (name "PUBLISHER") "Altium Limited"))
      (libsource (lib "Altera Cyclone II") (part "EP2C8Q208C8"))
    )
    (comp (ref "U5") (value "DAC5687-X") (footprint "TQFP100") (libsource (lib "原理图封装库") (part "DAC5687-X")))
    (comp (ref "U6")
      (value "EPCS4SI8N")
      (footprint "SOP8")
      (fields (field (name "PUBLISHER") "Altium Limited"))
      (libsource (lib "Altera EPCS Configuration Device") (part "EPCS4SI8N"))
    )
    (comp (ref "U7")
      (value "STM32F101V8T6")
      (footprint "TQFP100")
      (description "STM32 ARM-based 32-bit MCU with 64 Kbytes Flash, 100-pin LQFP, Industrial Temperature")
      (fields (field (name "PUBLISHER") "Altium Limited"))
      (libsource (lib "ST Microcontroller 32-Bit STM32") (part "STM32F101V8T6"))
    )
    (comp (ref "Y1") (value "TCXO") (footprint "晶振7050") (libsource (lib "原理图封装库") (part "TCXO")))
    (comp (ref "Y2")
      (value "8M")
      (footprint "晶振-1")
      (description "Crystal Oscillator")
      (fields (field (name "PUBLISHER") "Altium Limited"))
      (libsource (lib "Miscellaneous Devices") (part "XTAL"))
    )
  )
  (nets
    (net (code "1") (name "/A0") (class "Default")
      (node (ref "PP1") (pin "4") (pinfunction "4_4") (pintype "passive"))
      (node (ref "U7") (pin "23") (pinfunction "PA0-WKUP_23") (pintype "bidirectional"))
    )
    (net (code "2") (name "/A1") (class "Default")
      (node (ref "PP1") (pin "3") (pinfunction "3_3") (pintype "passive"))
      (node (ref "U7") (pin "24") (pinfunction "PA1_24") (pintype "bidirectional"))
    )
    (net (code "3") (name "/A2") (class "Default")
      (node (ref "PP1") (pin "2") (pinfunction "2_2") (pintype "passive"))
      (node (ref "U7") (pin "25") (pinfunction "PA2_25") (pintype "bidirectional"))
    )
    (net (code "4") (name "/A3") (class "Default")
      (node (ref "PP1") (pin "1") (pinfunction "1_1") (pintype "passive"))
      (node (ref "U7") (pin "26") (pinfunction "PA3_26") (pintype "bidirectional"))
    )
    (net (code "5") (name "/A4") (class "Default")
      (node (ref "PP2") (pin "4") (pinfunction "4_4") (pintype "passive"))
      (node (ref "U7") (pin "29") (pinfunction "PA4_29") (pintype "bidirectional"))
    )
    (net (code "6") (name "/A5") (class "Default")
      (node (ref "U7") (pin "30") (pinfunction "PA5_30") (pintype "bidirectional"))
    )
    (net (code "7") (name "/A6") (class "Default")
      (node (ref "U7") (pin "31") (pinfunction "PA6_31") (pintype "bidirectional"))
    )
    (net (code "8") (name "/A7") (class "Default")
      (node (ref "U7") (pin "32") (pinfunction "PA7_32") (pintype "bidirectional"))
    )
    (net (code "9") (name "/A8") (class "Default")
      (node (ref "U7") (pin "67") (pinfunction "PA8_67") (pintype "bidirectional"))
    )
    (net (code "10") (name "/A9") (class "Default")
      (node (ref "U7") (pin "68") (pinfunction "PA9_68") (pintype "bidirectional"))
    )
    (net (code "11") (name "/A10") (class "Default")
      (node (ref "U7") (pin "69") (pinfunction "PA10_69") (pintype "bidirectional"))
    )
    (net (code "12") (name "/A11") (class "Default")
      (node (ref "U7") (pin "70") (pinfunction "PA11_70") (pintype "bidirectional"))
    )
    (net (code "13") (name "/A12") (class "Default")
      (node (ref "U7") (pin "71") (pinfunction "PA12_71") (pintype "bidirectional"))
    )
    (net (code "14") (name "/A13") (class "Default")
      (node (ref "P5") (pin "3") (pinfunction "3_3") (pintype "passive"))
      (node (ref "R58") (pin "2") (pinfunction "2_2") (pintype "passive"))
      (node (ref "U7") (pin "72") (pinfunction "PA13/JTMS/SWDIO_72") (pintype "bidirectional"))
    )
    (net (code "15") (name "/A14") (class "Default")
      (node (ref "P5") (pin "2") (pinfunction "2_2") (pintype "passive"))
      (node (ref "R57") (pin "1") (pinfunction "1_1") (pintype "passive"))
      (node (ref "U7") (pin "76") (pinfunction "PA14/JTCK/SWCLK_76") (pintype "bidirectional"))
    )
    (net (code "16") (name "/A15") (class "Default")
      (node (ref "U7") (pin "77") (pinfunction "PA15/JTDI_77") (pintype "bidirectional"))
    )
    (net (code "17") (name "/ASDI") (class "Default")
      (node (ref "P4") (pin "9") (pinfunction "9_9") (pintype "passive"))
      (node (ref "U4") (pin "1") (pinfunction "IO,_(ASDO)_1") (pintype "bidirectional"))
      (node (ref "U6") (pin "5") (pinfunction "ASDI_5") (pintype "input"))
    )
    (net (code "18") (name "/B0") (class "Default")
      (node (ref "PP2") (pin "3") (pinfunction "3_3") (pintype "passive"))
      (node (ref "U7") (pin "35") (pinfunction "PB0_35") (pintype "bidirectional"))
    )
    (net (code "19") (name "/B1") (class "Default")
      (node (ref "PP2") (pin "2") (pinfunction "2_2") (pintype "passive"))
      (node (ref "U7") (pin "36") (pinfunction "PB1_36") (pintype "bidirectional"))
    )
    (net (code "20") (name "/B2") (class "Default")
      (node (ref "PP2") (pin "1") (pinfunction "1_1") (pintype "passive"))
      (node (ref "U7") (pin "37") (pinfunction "PB2/BOOT1_37") (pintype "bidirectional"))
    )
    (net (code "21") (name "/B3") (class "Default")
      (node (ref "P10") (pin "1") (pinfunction "1_1") (pintype "passive"))
      (node (ref "U7") (pin "89") (pinfunction "PB3/JTDO_89") (pintype "bidirectional"))
    )
    (net (code "22") (name "/B4") (class "Default")
      (node (ref "P10") (pin "2") (pinfunction "2_2") (pintype "passive"))
      (node (ref "U7") (pin "90") (pinfunction "PB4/JNTRST_90") (pintype "bidirectional"))
    )
    (net (code "23") (name "/B5") (class "Default")
      (node (ref "P10") (pin "3") (pinfunction "3_3") (pintype "passive"))
      (node (ref "U7") (pin "91") (pinfunction "PB5_91") (pintype "bidirectional"))
    )
    (net (code "24") (name "/B6") (class "Default")
      (node (ref "P10") (pin "4") (pinfunction "4_4") (pintype "passive"))
      (node (ref "U7") (pin "92") (pinfunction "PB6_92") (pintype "bidirectional"))
    )
    (net (code "25") (name "/B7") (class "Default")
      (node (ref "P10") (pin "5") (pinfunction "5_5") (pintype "passive"))
      (node (ref "U7") (pin "93") (pinfunction "PB7_93") (pintype "bidirectional"))
    )
    (net (code "26") (name "/B8") (class "Default")
      (node (ref "P10") (pin "6") (pinfunction "6_6") (pintype "passive"))
      (node (ref "U7") (pin "95") (pinfunction "PB8_95") (pintype "bidirectional"))
    )
    (net (code "27") (name "/B9") (class "Default")
      (node (ref "P10") (pin "7") (pinfunction "7_7") (pintype "passive"))
      (node (ref "U7") (pin "96") (pinfunction "PB9_96") (pintype "bidirectional"))
    )
    (net (code "28") (name "/B10") (class "Default")
      (node (ref "P7") (pin "2") (pinfunction "2_2") (pintype "passive"))
      (node (ref "U7") (pin "47") (pinfunction "PB10_47") (pintype "bidirectional"))
    )
    (net (code "29") (name "/B11") (class "Default")
      (node (ref "P7") (pin "1") (pinfunction "1_1") (pintype "passive"))
      (node (ref "U7") (pin "48") (pinfunction "PB11_48") (pintype "bidirectional"))
    )
    (net (code "30") (name "/B12") (class "Default")
      (node (ref "U7") (pin "51") (pinfunction "PB12_51") (pintype "bidirectional"))
    )
    (net (code "31") (name "/B13") (class "Default")
      (node (ref "U7") (pin "52") (pinfunction "PB13_52") (pintype "bidirectional"))
    )
    (net (code "32") (name "/B14") (class "Default")
      (node (ref "U7") (pin "53") (pinfunction "PB14_53") (pintype "bidirectional"))
    )
    (net (code "33") (name "/B15") (class "Default")
      (node (ref "U7") (pin "54") (pinfunction "PB15_54") (pintype "bidirectional"))
    )
    (net (code "34") (name "/BAT") (class "Default")
      (node (ref "U7") (pin "6") (pinfunction "VBAT_6") (pintype "power_in"))
    )
    (net (code "35") (name "/C0") (class "Default")
      (node (ref "U7") (pin "15") (pinfunction "PC0_15") (pintype "bidirectional"))
    )
    (net (code "36") (name "/C1") (class "Default")
      (node (ref "U7") (pin "16") (pinfunction "PC1_16") (pintype "bidirectional"))
    )
    (net (code "37") (name "/C2") (class "Default")
      (node (ref "U7") (pin "17") (pinfunction "PC2_17") (pintype "bidirectional"))
    )
    (net (code "38") (name "/C3") (class "Default")
      (node (ref "U7") (pin "18") (pinfunction "PC3_18") (pintype "bidirectional"))
    )
    (net (code "39") (name "/C4") (class "Default")
      (node (ref "U7") (pin "33") (pinfunction "PC4_33") (pintype "bidirectional"))
    )
    (net (code "40") (name "/C5") (class "Default")
      (node (ref "U7") (pin "34") (pinfunction "PC5_34") (pintype "bidirectional"))
    )
    (net (code "41") (name "/C6") (class "Default")
      (node (ref "R15") (pin "2") (pinfunction "2_2") (pintype "passive"))
      (node (ref "U7") (pin "63") (pinfunction "PC6_63") (pintype "bidirectional"))
    )
    (net (code "42") (name "/C7") (class "Default")
      (node (ref "R14") (pin "2") (pinfunction "2_2") (pintype "passive"))
      (node (ref "U7") (pin "64") (pinfunction "PC7_64") (pintype "bidirectional"))
    )
    (net (code "43") (name "/C8") (class "Default")
      (node (ref "R13") (pin "2") (pinfunction "2_2") (pintype "passive"))
      (node (ref "U7") (pin "65") (pinfunction "PC8_65") (pintype "bidirectional"))
    )
    (net (code "44") (name "/C9") (class "Default")
      (node (ref "R12") (pin "2") (pinfunction "2_2") (pintype "passive"))
      (node (ref "U7") (pin "66") (pinfunction "PC9_66") (pintype "bidirectional"))
    )
    (net (code "45") (name "/C10") (class "Default")
      (node (ref "R53") (pin "1") (pinfunction "1_1") (pintype "passive"))
      (node (ref "U7") (pin "78") (pinfunction "PC10_78") (pintype "bidirectional"))
    )
    (net (code "46") (name "/C11") (class "Default")
      (node (ref "R52") (pin "1") (pinfunction "1_1") (pintype "passive"))
      (node (ref "U7") (pin "79") (pinfunction "PC11_79") (pintype "bidirectional"))
    )
    (net (code "47") (name "/C12") (class "Default")
      (node (ref "R47") (pin "2") (pinfunction "2_2") (pintype "passive"))
      (node (ref "U7") (pin "80") (pinfunction "PC12_80") (pintype "bidirectional"))
    )
    (net (code "48") (name "/C13") (class "Default")
      (node (ref "D5") (pin "1") (pinfunction "A_1") (pintype "passive"))
      (node (ref "U7") (pin "7") (pinfunction "PC13-TAMPER-RTC_7") (pintype "bidirectional"))
    )
    (net (code "49") (name "/C14") (class "Default")
      (node (ref "U7") (pin "8") (pinfunction "PC14-OSC32_IN_8") (pintype "bidirectional"))
    )
    (net (code "50") (name "/C15") (class "Default")
      (node (ref "U7") (pin "9") (pinfunction "PC15-OSC32_OUT_9") (pintype "bidirectional"))
    )
    (net (code "51") (name "/CLK2") (class "Default")
      (node (ref "LL2") (pin "4") (pinfunction "Pri-_4") (pintype "passive"))
      (node (ref "R42") (pin "1") (pinfunction "1_1") (pintype "passive"))
      (node (ref "U5") (pin "62") (pinfunction "CLK2_62") (pintype "bidirectional"))
    )
    (net (code "52") (name "/CLK2*") (class "Default")
      (node (ref "LL2") (pin "5") (pinfunction "Pri+_5") (pintype "passive"))
      (node (ref "R42") (pin "2") (pinfunction "2_2") (pintype "passive"))
      (node (ref "U5") (pin "63") (pinfunction "CLK2C_63") (pintype "bidirectional"))
    )
    (net (code "53") (name "/CONF_DONE") (class "Default")
      (node (ref "P4") (pin "3") (pinfunction "3_3") (pintype "passive"))
      (node (ref "R38") (pin "1") (pinfunction "1_1") (pintype "passive"))
      (node (ref "U4") (pin "123") (pinfunction "CONF_DONE_123") (pintype "bidirectional"))
    )
    (net (code "54") (name "/D0") (class "Default")
      (node (ref "P10") (pin "15") (pinfunction "15_15") (pintype "passive"))
      (node (ref "U7") (pin "81") (pinfunction "PD0_81") (pintype "bidirectional"))
    )
    (net (code "55") (name "/D1") (class "Default")
      (node (ref "P10") (pin "16") (pinfunction "16_16") (pintype "passive"))
      (node (ref "U7") (pin "82") (pinfunction "PD1_82") (pintype "bidirectional"))
    )
    (net (code "56") (name "/D2") (class "Default")
      (node (ref "R46") (pin "2") (pinfunction "2_2") (pintype "passive"))
      (node (ref "U7") (pin "83") (pinfunction "PD2_83") (pintype "bidirectional"))
    )
    (net (code "57") (name "/D3") (class "Default")
      (node (ref "U7") (pin "84") (pinfunction "PD3_84") (pintype "bidirectional"))
    )
    (net (code "58") (name "/D4") (class "Default")
      (node (ref "P10") (pin "12") (pinfunction "12_12") (pintype "passive"))
      (node (ref "U7") (pin "85") (pinfunction "PD4_85") (pintype "bidirectional"))
    )
    (net (code "59") (name "/D5") (class "Default")
      (node (ref "P10") (pin "11") (pinfunction "11_11") (pintype "passive"))
      (node (ref "U7") (pin "86") (pinfunction "PD5_86") (pintype "bidirectional"))
    )
    (net (code "60") (name "/D6") (class "Default")
      (node (ref "U7") (pin "87") (pinfunction "PD6_87") (pintype "bidirectional"))
    )
    (net (code "61") (name "/D7") (class "Default")
      (node (ref "P10") (pin "9") (pinfunction "9_9") (pintype "passive"))
      (node (ref "U7") (pin "88") (pinfunction "PD7_88") (pintype "bidirectional"))
    )
    (net (code "62") (name "/D8") (class "Default")
      (node (ref "P10") (pin "26") (pinfunction "26_26") (pintype "passive"))
      (node (ref "U7") (pin "55") (pinfunction "PD8_55") (pintype "bidirectional"))
    )
    (net (code "63") (name "/D9") (class "Default")
      (node (ref "P10") (pin "27") (pinfunction "27_27") (pintype "passive"))
      (node (ref "U7") (pin "56") (pinfunction "PD9_56") (pintype "bidirectional"))
    )
    (net (code "64") (name "/D10") (class "Default")
      (node (ref "P10") (pin "28") (pinfunction "28_28") (pintype "passive"))
      (node (ref "U7") (pin "57") (pinfunction "PD10_57") (pintype "bidirectional"))
    )
    (net (code "65") (name "/D11") (class "Default")
      (node (ref "P10") (pin "10") (pinfunction "10_10") (pintype "passive"))
      (node (ref "U7") (pin "58") (pinfunction "PD11_58") (pintype "bidirectional"))
    )
    (net (code "66") (name "/D12") (class "Default")
      (node (ref "U7") (pin "59") (pinfunction "PD12_59") (pintype "bidirectional"))
    )
    (net (code "67") (name "/D13") (class "Default")
      (node (ref "U7") (pin "60") (pinfunction "PD13_60") (pintype "bidirectional"))
    )
    (net (code "68") (name "/D14") (class "Default")
      (node (ref "P10") (pin "13") (pinfunction "13_13") (pintype "passive"))
      (node (ref "U7") (pin "61") (pinfunction "PD14_61") (pintype "bidirectional"))
    )
    (net (code "69") (name "/D15") (class "Default")
      (node (ref "P10") (pin "14") (pinfunction "14_14") (pintype "passive"))
      (node (ref "U7") (pin "62") (pinfunction "PD15_62") (pintype "bidirectional"))
    )
    (net (code "70") (name "/DA0") (class "Default")
      (node (ref "RN1") (pin "1") (pintype "passive"))
      (node (ref "U4") (pin "82") (pinfunction "IO,_LVDS64n_82") (pintype "bidirectional"))
    )
    (net (code "71") (name "/DA1") (class "Default")
      (node (ref "RN1") (pin "2") (pintype "passive"))
      (node (ref "U4") (pin "84") (pinfunction "IO,_LVDS63p,_DM0B/(DM1B0/BWS#1B0)_84") (pintype "bidirectional"))
    )
    (net (code "72") (name "/DA2") (class "Default")
      (node (ref "RN1") (pin "3") (pintype "passive"))
      (node (ref "U4") (pin "86") (pinfunction "IO,_LVDS63n,__/DQ1B8_86") (pintype "bidirectional"))
    )
    (net (code "73") (name "/DA3") (class "Default")
      (node (ref "RN1") (pin "4") (pintype "passive"))
      (node (ref "U4") (pin "87") (pinfunction "IO,_LVDS62p,_DQ0B7/DQ1B7_87") (pintype "bidirectional"))
    )
    (net (code "74") (name "/DA4") (class "Default")
      (node (ref "RN2") (pin "1") (pintype "passive"))
      (node (ref "U4") (pin "88") (pinfunction "IO,_LVDS62n,_DQ0B6/DQ1B6_88") (pintype "bidirectional"))
    )
    (net (code "75") (name "/DA5") (class "Default")
      (node (ref "RN2") (pin "2") (pintype "passive"))
      (node (ref "U4") (pin "90") (pinfunction "IO,_LVDS61p,_DQ0B5/DQ1B5_90") (pintype "bidirectional"))
    )
    (net (code "76") (name "/DA6") (class "Default")
      (node (ref "RN2") (pin "3") (pintype "passive"))
      (node (ref "U4") (pin "92") (pinfunction "IO,_LVDS61n,_DQ0B4/DQ1B4_92") (pintype "bidirectional"))
    )
    (net (code "77") (name "/DA7") (class "Default")
      (node (ref "RN2") (pin "4") (pintype "passive"))
      (node (ref "U4") (pin "94") (pinfunction "IO,_LVDS60p,_(DPCLK4/DQS0B)/(DPCLK4/DQS0B)_94") (pintype "bidirectional"))
    )
    (net (code "78") (name "/DA8") (class "Default")
      (node (ref "RN3") (pin "1") (pintype "passive"))
      (node (ref "U4") (pin "95") (pinfunction "IO,_LVDS60n_95") (pintype "bidirectional"))
    )
    (net (code "79") (name "/DA9") (class "Default")
      (node (ref "RN3") (pin "2") (pintype "passive"))
      (node (ref "U4") (pin "96") (pinfunction "IO,_DQ0B3/DQ1B3_96") (pintype "bidirectional"))
    )
    (net (code "80") (name "/DA10") (class "Default")
      (node (ref "RN3") (pin "3") (pintype "passive"))
      (node (ref "U4") (pin "97") (pinfunction "IO,_LVDS59p,_DQ0B2/DQ1B2_97") (pintype "bidirectional"))
    )
    (net (code "81") (name "/DA11") (class "Default")
      (node (ref "RN3") (pin "4") (pintype "passive"))
      (node (ref "U4") (pin "99") (pinfunction "IO,_LVDS59n,_DQ0B1/DQ1B1_99") (pintype "bidirectional"))
    )
    (net (code "82") (name "/DA12") (class "Default")
      (node (ref "RN4") (pin "1") (pintype "passive"))
      (node (ref "U4") (pin "101") (pinfunction "IO,_LVDS58p,_DQ0B0/DQ1B0_101") (pintype "bidirectional"))
    )
    (net (code "83") (name "/DA13") (class "Default")
      (node (ref "RN4") (pin "2") (pintype "passive"))
      (node (ref "U4") (pin "102") (pinfunction "IO,_LVDS58n_102") (pintype "bidirectional"))
    )
    (net (code "84") (name "/DA14") (class "Default")
      (node (ref "RN4") (pin "3") (pintype "passive"))
      (node (ref "U4") (pin "103") (pinfunction "IO,_LVDS57p_103") (pintype "bidirectional"))
    )
    (net (code "85") (name "/DA15") (class "Default")
      (node (ref "RN4") (pin "4") (pintype "passive"))
      (node (ref "U4") (pin "104") (pinfunction "IO,_LVDS57n_104") (pintype "bidirectional"))
    )
    (net (code "86") (name "/DATA") (class "Default")
      (node (ref "P4") (pin "7") (pinfunction "7_7") (pintype "passive"))
      (node (ref "R36") (pin "1") (pinfunction "1_1") (pintype "passive"))
      (node (ref "U4") (pin "20") (pinfunction "DATA0_20") (pintype "input"))
      (node (ref "U6") (pin "2") (pinfunction "DATA_2") (pintype "output"))
    )
    (net (code "88") (name "/DB0") (class "Default")
      (node (ref "RN5") (pin "8") (pintype "passive"))
      (node (ref "U4") (pin "80") (pinfunction "IO_80") (pintype "bidirectional"))
    )
    (net (code "89") (name "/DB1") (class "Default")
      (node (ref "RN5") (pin "7") (pintype "passive"))
      (node (ref "U4") (pin "77") (pinfunction "IO,_LVDS66n_77") (pintype "bidirectional"))
    )
    (net (code "90") (name "/DB2") (class "Default")
      (node (ref "RN5") (pin "6") (pintype "passive"))
      (node (ref "U4") (pin "76") (pinfunction "IO,_LVDS66p_76") (pintype "bidirectional"))
    )
    (net (code "91") (name "/DB3") (class "Default")
      (node (ref "RN5") (pin "5") (pintype "passive"))
      (node (ref "U4") (pin "75") (pinfunction "IO,_LVDS67n_75") (pintype "bidirectional"))
    )
    (net (code "92") (name "/DB4") (class "Default")
      (node (ref "RN6") (pin "8") (pintype "passive"))
      (node (ref "U4") (pin "74") (pinfunction "IO,_LVDS67p,_DQ1B0/DQ1B9_74") (pintype "bidirectional"))
    )
    (net (code "93") (name "/DB5") (class "Default")
      (node (ref "RN6") (pin "7") (pintype "passive"))
      (node (ref "U4") (pin "72") (pinfunction "IO,_LVDS68n,_DQ1B1/DQ1B10_72") (pintype "bidirectional"))
    )
    (net (code "94") (name "/DB6") (class "Default")
      (node (ref "RN6") (pin "6") (pintype "passive"))
      (node (ref "U4") (pin "70") (pinfunction "IO,_LVDS68p,_DQ1B2/DQ1B11_70") (pintype "bidirectional"))
    )
    (net (code "95") (name "/DB7") (class "Default")
      (node (ref "RN6") (pin "5") (pintype "passive"))
      (node (ref "U4") (pin "69") (pinfunction "IO,_LVDS70n,_DQ1B3/DQ1B12_69") (pintype "bidirectional"))
    )
    (net (code "96") (name "/DB8") (class "Default")
      (node (ref "RN7") (pin "8") (pintype "passive"))
      (node (ref "U4") (pin "68") (pinfunction "IO,_LVDS70p,_DQ1B4/DQ1B13_68") (pintype "bidirectional"))
    )
    (net (code "97") (name "/DB9") (class "Default")
      (node (ref "RN7") (pin "7") (pintype "passive"))
      (node (ref "U4") (pin "64") (pinfunction "IO,_LVDS74n_64") (pintype "bidirectional"))
    )
    (net (code "98") (name "/DB10") (class "Default")
      (node (ref "RN7") (pin "6") (pintype "passive"))
      (node (ref "U4") (pin "63") (pinfunction "IO,_LVDS74p,_(DPCLK2/DQS1B)/(DPCLK2/DQS1B)_63") (pintype "bidirectional"))
    )
    (net (code "99") (name "/DB11") (class "Default")
      (node (ref "RN7") (pin "5") (pintype "passive"))
      (node (ref "U4") (pin "61") (pinfunction "IO,_LVDS75n,_DQ1B5/DQ1B14_61") (pintype "bidirectional"))
    )
    (net (code "100") (name "/DB12") (class "Default")
      (node (ref "RN8") (pin "8") (pintype "passive"))
      (node (ref "U4") (pin "60") (pinfunction "IO,_LVDS75p,_DQ1B6/DQ1B15_60") (pintype "bidirectional"))
    )
    (net (code "101") (name "/DB13") (class "Default")
      (node (ref "RN8") (pin "7") (pintype "passive"))
      (node (ref "U4") (pin "59") (pinfunction "IO,_LVDS76n,_DQ1B7/DQ1B16_59") (pintype "bidirectional"))
    )
    (net (code "102") (name "/DB14") (class "Default")
      (node (ref "RN8") (pin "6") (pintype "passive"))
      (node (ref "U4") (pin "58") (pinfunction "IO,_LVDS76p,_DQ1B8/DQ1B17_58") (pintype "bidirectional"))
    )
    (net (code "103") (name "/DB15") (class "Default")
      (node (ref "RN8") (pin "5") (pintype "passive"))
      (node (ref "U4") (pin "57") (pinfunction "IO,_LVDS77p,_(DM1B/BWS#1B)/(DM1B1/BWS#1B1)_57") (pintype "bidirectional"))
    )
    (net (code "105") (name "/DCLK") (class "Default")
      (node (ref "P4") (pin "1") (pinfunction "1_1") (pintype "passive"))
      (node (ref "R37") (pin "1") (pinfunction "1_1") (pintype "passive"))
      (node (ref "U4") (pin "21") (pinfunction "DCLK_21") (pintype "bidirectional"))
      (node (ref "U6") (pin "6") (pinfunction "DCLK_6") (pintype "input"))
    )
    (net (code "106") (name "/E0") (class "Default")
      (node (ref "P10") (pin "8") (pinfunction "8_8") (pintype "passive"))
      (node (ref "U7") (pin "97") (pinfunction "PE0_97") (pintype "bidirectional"))
    )
    (net (code "107") (name "/E1") (class "Default")
      (node (ref "R63") (pin "1") (pinfunction "1_1") (pintype "passive"))
      (node (ref "U7") (pin "98") (pinfunction "PE1_98") (pintype "bidirectional"))
    )
    (net (code "108") (name "/E2") (class "Default")
      (node (ref "U7") (pin "1") (pinfunction "PE2_1") (pintype "bidirectional"))
    )
    (net (code "109") (name "/E3") (class "Default")
      (node (ref "U7") (pin "2") (pinfunction "PE3_2") (pintype "bidirectional"))
    )
    (net (code "110") (name "/E4") (class "Default")
      (node (ref "U7") (pin "3") (pinfunction "PE4_3") (pintype "bidirectional"))
    )
    (net (code "111") (name "/E5") (class "Default")
      (node (ref "U7") (pin "4") (pinfunction "PE5_4") (pintype "bidirectional"))
    )
    (net (code "112") (name "/E6") (class "Default")
      (node (ref "U7") (pin "5") (pinfunction "PE6_5") (pintype "bidirectional"))
    )
    (net (code "113") (name "/E7") (class "Default")
      (node (ref "P10") (pin "17") (pinfunction "17_17") (pintype "passive"))
      (node (ref "U7") (pin "38") (pinfunction "PE7_38") (pintype "bidirectional"))
    )
    (net (code "114") (name "/E8") (class "Default")
      (node (ref "P10") (pin "18") (pinfunction "18_18") (pintype "passive"))
      (node (ref "U7") (pin "39") (pinfunction "PE8_39") (pintype "bidirectional"))
    )
    (net (code "115") (name "/E9") (class "Default")
      (node (ref "P10") (pin "19") (pinfunction "19_19") (pintype "passive"))
      (node (ref "U7") (pin "40") (pinfunction "PE9_40") (pintype "bidirectional"))
    )
    (net (code "116") (name "/E10") (class "Default")
      (node (ref "P10") (pin "20") (pinfunction "20_20") (pintype "passive"))
      (node (ref "U7") (pin "41") (pinfunction "PE10_41") (pintype "bidirectional"))
    )
    (net (code "117") (name "/E11") (class "Default")
      (node (ref "P10") (pin "21") (pinfunction "21_21") (pintype "passive"))
      (node (ref "U7") (pin "42") (pinfunction "PE11_42") (pintype "bidirectional"))
    )
    (net (code "118") (name "/E12") (class "Default")
      (node (ref "P10") (pin "22") (pinfunction "22_22") (pintype "passive"))
      (node (ref "U7") (pin "43") (pinfunction "PE12_43") (pintype "bidirectional"))
    )
    (net (code "119") (name "/E13") (class "Default")
      (node (ref "P10") (pin "23") (pinfunction "23_23") (pintype "passive"))
      (node (ref "U7") (pin "44") (pinfunction "PE13_44") (pintype "bidirectional"))
    )
    (net (code "120") (name "/E14") (class "Default")
      (node (ref "P10") (pin "24") (pinfunction "24_24") (pintype "passive"))
      (node (ref "U7") (pin "45") (pinfunction "PE14_45") (pintype "bidirectional"))
    )
    (net (code "121") (name "/E15") (class "Default")
      (node (ref "P10") (pin "25") (pinfunction "25_25") (pintype "passive"))
      (node (ref "U7") (pin "46") (pinfunction "PE15_46") (pintype "bidirectional"))
    )
    (net (code "122") (name "/FD0") (class "Default")
      (node (ref "U4") (pin "105") (pinfunction "IO,_LVDS56n_105") (pintype "bidirectional"))
    )
    (net (code "123") (name "/FD1") (class "Default")
      (node (ref "U4") (pin "106") (pinfunction "IO,_LVDS56p,_(DM1R/BWS#1R)/(DM1R1/BWS#1R1)_106") (pintype "bidirectional"))
    )
    (net (code "124") (name "/FD2") (class "Default")
      (node (ref "U4") (pin "108") (pinfunction "IO,_LVDS54p_(nCEO)_108") (pintype "bidirectional"))
    )
    (net (code "125") (name "/FD3") (class "Default")
      (node (ref "U4") (pin "110") (pinfunction "IO,_LVDS53n,_DQ1R8/DQ1R17_110") (pintype "bidirectional"))
    )
    (net (code "126") (name "/FD4") (class "Default")
      (node (ref "U4") (pin "112") (pinfunction "IO,_LVDS53p,_DQ1R7/DQ1R16_112") (pintype "bidirectional"))
    )
    (net (code "127") (name "/FD5") (class "Default")
      (node (ref "U4") (pin "113") (pinfunction "IO,_LVDS52n,_DQ1R6/DQ1R15_113") (pintype "bidirectional"))
    )
    (net (code "128") (name "/FD6") (class "Default")
      (node (ref "U4") (pin "114") (pinfunction "IO,_LVDS52p,_DQ1R5/DQ1R14_114") (pintype "bidirectional"))
    )
    (net (code "129") (name "/FD7") (class "Default")
      (node (ref "U4") (pin "115") (pinfunction "IO,_LVDS51n,_DQ1R4/DQ1R13_115") (pintype "bidirectional"))
    )
    (net (code "130") (name "/FPGA_CLK") (class "Default")
      (node (ref "C26") (pin "1") (pinfunction "1_1") (pintype "passive"))
      (node (ref "U4") (pin "28") (pinfunction "CLK3,_LVDSCLK1n_INPUT_28") (pintype "input"))
    )
    (net (code "131") (name "/IOUTA1") (class "Default")
      (node (ref "C6") (pin "1") (pinfunction "1_1") (pintype "passive"))
      (node (ref "L6") (pin "1") (pinfunction "1_1") (pintype "passive"))
      (node (ref "R7") (pin "2") (pinfunction "2_2") (pintype "passive"))
      (node (ref "R8") (pin "1") (pinfunction "1_1") (pintype "passive"))
      (node (ref "U5") (pin "21") (pinfunction "IOUTA1_21") (pintype "output"))
    )
    (net (code "132") (name "/IOUTA2") (class "Default")
      (node (ref "C6") (pin "2") (pinfunction "2_2") (pintype "passive"))
      (node (ref "L5") (pin "1") (pinfunction "1_1") (pintype "passive"))
      (node (ref "R3") (pin "2") (pinfunction "2_2") (pintype "passive"))
      (node (ref "R4") (pin "1") (pinfunction "1_1") (pintype "passive"))
      (node (ref "U5") (pin "20") (pinfunction "IOUTA2_20") (pintype "output"))
    )
    (net (code "133") (name "/IOUTB1") (class "Default")
      (node (ref "C5") (pin "1") (pinfunction "1_1") (pintype "passive"))
      (node (ref "L4") (pin "1") (pinfunction "1_1") (pintype "passive"))
      (node (ref "R5") (pin "2") (pinfunction "2_2") (pintype "passive"))
      (node (ref "R6") (pin "1") (pinfunction "1_1") (pintype "passive"))
      (node (ref "U5") (pin "5") (pinfunction "IOUTB1_5") (pintype "output"))
    )
    (net (code "134") (name "/IOUTB2") (class "Default")
      (node (ref "C5") (pin "2") (pinfunction "2_2") (pintype "passive"))
      (node (ref "L3") (pin "1") (pinfunction "1_1") (pintype "passive"))
      (node (ref "R1") (pin "2") (pinfunction "2_2") (pintype "passive"))
      (node (ref "R2") (pin "1") (pinfunction "1_1") (pintype "passive"))
      (node (ref "U5") (pin "6") (pinfunction "IOUTB2_6") (pintype "output"))
    )
    (net (code "135") (name "/LON") (class "Default")
      (node (ref "LL1") (pin "3") (pinfunction "Sec+_3") (pintype "passive"))
      (node (ref "U2") (pin "3") (pinfunction "LOP_3") (pintype "passive"))
    )
    (net (code "136") (name "/LOP") (class "Default")
      (node (ref "LL1") (pin "1") (pinfunction "Sec-_1") (pintype "passive"))
      (node (ref "U2") (pin "4") (pinfunction "LON_4") (pintype "passive"))
    )
    (net (code "137") (name "/NRST") (class "Default")
      (node (ref "C97") (pin "1") (pinfunction "1_1") (pintype "passive"))
      (node (ref "K1") (pin "2") (pinfunction "2_2") (pintype "passive"))
      (node (ref "R61") (pin "1") (pinfunction "1_1") (pintype "passive"))
      (node (ref "U7") (pin "14") (pinfunction "NRST_14") (pintype "bidirectional"))
    )
    (net (code "138") (name "/PLL_LOCK") (class "Default")
      (node (ref "P3") (pin "3") (pinfunction "3_3") (pintype "passive"))
      (node (ref "R51") (pin "1") (pinfunction "1_1") (pintype "passive"))
      (node (ref "U4") (pin "23") (pinfunction "CLK0,_LVDSCLK0p_INPUT_23") (pintype "input"))
    )
    (net (code "139") (name "/REF_4360") (class "Default")
      (node (ref "C4") (pin "1") (pinfunction "1_1") (pintype "passive"))
      (node (ref "U4") (pin "47") (pinfunction "IO,_PLL1_OUTp_47") (pintype "bidirectional"))
    )
    (net (code "140") (name "/RESET") (class "Default")
      (node (ref "R45") (pin "1") (pinfunction "1_1") (pintype "passive"))
      (node (ref "R63") (pin "2") (pinfunction "2_2") (pintype "passive"))
      (node (ref "U5") (pin "95") (pinfunction "RESETB_95") (pintype "bidirectional"))
    )
    (net (code "141") (name "/RF_OUT") (class "Default")
      (node (ref "C36") (pin "2") (pinfunction "2_2") (pintype "passive"))
      (node (ref "J3") (pin "1") (pinfunction "Signal_1") (pintype "input"))
    )
    (net (code "142") (name "/TCK") (class "Default")
      (node (ref "P2") (pin "1") (pinfunction "1_1") (pintype "passive"))
      (node (ref "R44") (pin "2") (pinfunction "2_2") (pintype "passive"))
      (node (ref "U4") (pin "18") (pinfunction "TCK_18") (pintype "input"))
    )
    (net (code "143") (name "/TDI") (class "Default")
      (node (ref "P2") (pin "9") (pinfunction "9_9") (pintype "passive"))
      (node (ref "R41") (pin "2") (pinfunction "2_2") (pintype "passive"))
      (node (ref "U4") (pin "19") (pinfunction "TDI_19") (pintype "input"))
    )
    (net (code "144") (name "/TDO") (class "Default")
      (node (ref "P2") (pin "3") (pinfunction "3_3") (pintype "passive"))
      (node (ref "U4") (pin "16") (pinfunction "TDO_16") (pintype "output"))
    )
    (net (code "145") (name "/TMS") (class "Default")
      (node (ref "P2") (pin "5") (pinfunction "5_5") (pintype "passive"))
      (node (ref "R43") (pin "1") (pinfunction "1_1") (pintype "passive"))
      (node (ref "U4") (pin "17") (pinfunction "TMS_17") (pintype "input"))
    )
    (net (code "146") (name "/nCE") (class "Default")
      (node (ref "P4") (pin "6") (pinfunction "6_6") (pintype "passive"))
      (node (ref "R55") (pin "2") (pinfunction "2_2") (pintype "passive"))
      (node (ref "U4") (pin "22") (pinfunction "nCE_22") (pintype "input"))
    )
    (net (code "147") (name "/nCONFIG") (class "Default")
      (node (ref "P4") (pin "5") (pinfunction "5_5") (pintype "passive"))
      (node (ref "R39") (pin "1") (pinfunction "1_1") (pintype "passive"))
      (node (ref "U4") (pin "26") (pinfunction "nCONFIG_26") (pintype "input"))
    )
    (net (code "148") (name "/nCS") (class "Default")
      (node (ref "P4") (pin "8") (pinfunction "8_8") (pintype "passive"))
      (node (ref "U4") (pin "2") (pinfunction "IO,_(nCSO)_2") (pintype "bidirectional"))
      (node (ref "U6") (pin "1") (pinfunction "nCS_1") (pintype "input"))
    )
    (net (code "149") (name "/nSTATUS") (class "Default")
      (node (ref "R40") (pin "1") (pinfunction "1_1") (pintype "passive"))
      (node (ref "U4") (pin "121") (pinfunction "nSTATUS_121") (pintype "bidirectional"))
    )
    (net (code "150") (name "5VCC") (class "Default")
      (node (ref "C23") (pin "1") (pinfunction "1_1") (pintype "passive"))
      (node (ref "C27") (pin "2") (pinfunction "2_2") (pintype "passive"))
      (node (ref "D2") (pin "1") (pinfunction "A_1") (pintype "passive"))
      (node (ref "L11") (pin "1") (pinfunction "1_1") (pintype "passive"))
      (node (ref "L24") (pin "2") (pinfunction "2_2") (pintype "passive"))
      (node (ref "R1") (pin "1") (pinfunction "1_1") (pintype "passive"))
      (node (ref "R3") (pin "1") (pinfunction "1_1") (pintype "passive"))
      (node (ref "R5") (pin "1") (pinfunction "1_1") (pintype "passive"))
      (node (ref "R7") (pin "1") (pinfunction "1_1") (pintype "passive"))
      (node (ref "T1") (pin "3") (pinfunction "Vout_3") (pintype "passive"))
      (node (ref "T2") (pin "1") (pinfunction "Vin_1") (pintype "passive"))
    )
    (net (code "151") (name "5VCC_AMP") (class "Default")
      (node (ref "C53") (pin "2") (pinfunction "2_2") (pintype "passive"))
      (node (ref "C54") (pin "2") (pinfunction "2_2") (pintype "passive"))
      (node (ref "C55") (pin "2") (pinfunction "2_2") (pintype "passive"))
      (node (ref "L11") (pin "2") (pinfunction "2_2") (pintype "passive"))
      (node (ref "L22") (pin "1") (pinfunction "1_1") (pintype "passive"))
    )
    (net (code "152") (name "AVDD3_3_4360") (class "Default")
      (node (ref "C24") (pin "2") (pinfunction "2_2") (pintype "passive"))
      (node (ref "C25") (pin "2") (pinfunction "2_2") (pintype "passive"))
      (node (ref "L19") (pin "2") (pinfunction "2_2") (pintype "passive"))
      (node (ref "U1") (pin "2") (pinfunction "AVDD_2") (pintype "passive"))
    )
    (net (code "153") (name "DVDD3_3_4360") (class "Default")
      (node (ref "C17") (pin "1") (pinfunction "1_1") (pintype "passive"))
      (node (ref "C18") (pin "1") (pinfunction "1_1") (pintype "passive"))
      (node (ref "L17") (pin "2") (pinfunction "2_2") (pintype "passive"))
      (node (ref "R9") (pin "2") (pinfunction "2_2") (pintype "passive"))
      (node (ref "U1") (pin "21") (pinfunction "DVDD_21") (pintype "passive"))
    )
    (net (code "154") (name "GND") (class "Default")
      (node (ref "C1") (pin "1") (pinfunction "1_1") (pintype "passive"))
      (node (ref "C10") (pin "2") (pinfunction "2_2") (pintype "passive"))
      (node (ref "C100") (pin "2") (pinfunction "2_2") (pintype "passive"))
      (node (ref "C103") (pin "1") (pinfunction "1_1") (pintype "passive"))
      (node (ref "C104") (pin "1") (pinfunction "1_1") (pintype "passive"))
      (node (ref "C105") (pin "1") (pinfunction "1_1") (pintype "passive"))
      (node (ref "C106") (pin "1") (pinfunction "1_1") (pintype "passive"))
      (node (ref "C107") (pin "1") (pinfunction "1_1") (pintype "passive"))
      (node (ref "C108") (pin "1") (pinfunction "1_1") (pintype "passive"))
      (node (ref "C109") (pin "1") (pinfunction "1_1") (pintype "passive"))
      (node (ref "C11") (pin "2") (pinfunction "2_2") (pintype "passive"))
      (node (ref "C110") (pin "1") (pinfunction "1_1") (pintype "passive"))
      (node (ref "C112") (pin "1") (pinfunction "1_1") (pintype "passive"))
      (node (ref "C113") (pin "1") (pinfunction "1_1") (pintype "passive"))
      (node (ref "C114") (pin "1") (pinfunction "1_1") (pintype "passive"))
      (node (ref "C115") (pin "1") (pinfunction "1_1") (pintype "passive"))
      (node (ref "C116") (pin "1") (pinfunction "1_1") (pintype "passive"))
      (node (ref "C117") (pin "1") (pinfunction "1_1") (pintype "passive"))
      (node (ref "C118") (pin "1") (pinfunction "1_1") (pintype "passive"))
      (node (ref "C119") (pin "1") (pinfunction "1_1") (pintype "passive"))
      (node (ref "C120") (pin "1") (pinfunction "1_1") (pintype "passive"))
      (node (ref "C121") (pin "1") (pinfunction "1_1") (pintype "passive"))
      (node (ref "C122") (pin "1") (pinfunction "1_1") (pintype "passive"))
      (node (ref "C123") (pin "1") (pinfunction "1_1") (pintype "passive"))
      (node (ref "C124") (pin "1") (pinfunction "1_1") (pintype "passive"))
      (node (ref "C125") (pin "1") (pinfunction "1_1") (pintype "passive"))
      (node (ref "C126") (pin "1") (pinfunction "1_1") (pintype "passive"))
      (node (ref "C127") (pin "1") (pinfunction "1_1") (pintype "passive"))
      (node (ref "C128") (pin "1") (pinfunction "1_1") (pintype "passive"))
      (node (ref "C129") (pin "1") (pinfunction "1_1") (pintype "passive"))
      (node (ref "C13") (pin "2") (pinfunction "2_2") (pintype "passive"))
      (node (ref "C130") (pin "1") (pinfunction "1_1") (pintype "passive"))
      (node (ref "C17") (pin "2") (pinfunction "2_2") (pintype "passive"))
      (node (ref "C18") (pin "2") (pinfunction "2_2") (pintype "passive"))
      (node (ref "C19") (pin "1") (pinfunction "1_1") (pintype "passive"))
      (node (ref "C2") (pin "2") (pinfunction "2_2") (pintype "passive"))
      (node (ref "C20") (pin "1") (pinfunction "1_1") (pintype "passive"))
      (node (ref "C21") (pin "1") (pinfunction "1_1") (pintype "passive"))
      (node (ref "C22") (pin "1") (pinfunction "1_1") (pintype "passive"))
      (node (ref "C23") (pin "2") (pinfunction "2_2") (pintype "passive"))
      (node (ref "C24") (pin "1") (pinfunction "1_1") (pintype "passive"))
      (node (ref "C25") (pin "1") (pinfunction "1_1") (pintype "passive"))
      (node (ref "C27") (pin "1") (pinfunction "1_1") (pintype "passive"))
      (node (ref "C28") (pin "2") (pinfunction "2_2") (pintype "passive"))
      (node (ref "C29") (pin "2") (pinfunction "2_2") (pintype "passive"))
      (node (ref "C3") (pin "2") (pinfunction "2_2") (pintype "passive"))
      (node (ref "C32") (pin "2") (pinfunction "2_2") (pintype "passive"))
      (node (ref "C34") (pin "2") (pinfunction "2_2") (pintype "passive"))
      (node (ref "C37") (pin "2") (pinfunction "2_2") (pintype "passive"))
      (node (ref "C38") (pin "2") (pinfunction "2_2") (pintype "passive"))
      (node (ref "C39") (pin "2") (pinfunction "2_2") (pintype "passive"))
      (node (ref "C40") (pin "1") (pinfunction "1_1") (pintype "passive"))
      (node (ref "C41") (pin "2") (pinfunction "2_2") (pintype "passive"))
      (node (ref "C42") (pin "1") (pinfunction "1_1") (pintype "passive"))
      (node (ref "C43") (pin "2") (pinfunction "2_2") (pintype "passive"))
      (node (ref "C44") (pin "2") (pinfunction "2_2") (pintype "passive"))
      (node (ref "C45") (pin "1") (pinfunction "1_1") (pintype "passive"))
      (node (ref "C46") (pin "2") (pinfunction "2_2") (pintype "passive"))
      (node (ref "C47") (pin "2") (pinfunction "2_2") (pintype "passive"))
      (node (ref "C48") (pin "1") (pinfunction "1_1") (pintype "passive"))
      (node (ref "C49") (pin "1") (pinfunction "1_1") (pintype "passive"))
      (node (ref "C50") (pin "2") (pinfunction "2_2") (pintype "passive"))
      (node (ref "C52") (pin "1") (pinfunction "1_1") (pintype "passive"))
      (node (ref "C53") (pin "1") (pinfunction "1_1") (pintype "passive"))
      (node (ref "C54") (pin "1") (pinfunction "1_1") (pintype "passive"))
      (node (ref "C55") (pin "1") (pinfunction "1_1") (pintype "passive"))
      (node (ref "C56") (pin "2") (pinfunction "2_2") (pintype "passive"))
      (node (ref "C57") (pin "2") (pinfunction "2_2") (pintype "passive"))
      (node (ref "C58") (pin "2") (pinfunction "2_2") (pintype "passive"))
      (node (ref "C59") (pin "2") (pinfunction "2_2") (pintype "passive"))
      (node (ref "C60") (pin "1") (pinfunction "1_1") (pintype "passive"))
      (node (ref "C61") (pin "2") (pinfunction "2_2") (pintype "passive"))
      (node (ref "C63") (pin "1") (pinfunction "1_1") (pintype "passive"))
      (node (ref "C64") (pin "2") (pinfunction "2_2") (pintype "passive"))
      (node (ref "C65") (pin "1") (pinfunction "1_1") (pintype "passive"))
      (node (ref "C66") (pin "2") (pinfunction "2_2") (pintype "passive"))
      (node (ref "C67") (pin "2") (pinfunction "2_2") (pintype "passive"))
      (node (ref "C68") (pin "2") (pinfunction "2_2") (pintype "passive"))
      (node (ref "C7") (pin "2") (pinfunction "2_2") (pintype "passive"))
      (node (ref "C70") (pin "1") (pinfunction "1_1") (pintype "passive"))
      (node (ref "C71") (pin "2") (pinfunction "2_2") (pintype "passive"))
      (node (ref "C72") (pin "2") (pinfunction "2_2") (pintype "passive"))
      (node (ref "C73") (pin "2") (pinfunction "2_2") (pintype "passive"))
      (node (ref "C74") (pin "2") (pinfunction "2_2") (pintype "passive"))
      (node (ref "C75") (pin "2") (pinfunction "2_2") (pintype "passive"))
      (node (ref "C76") (pin "2") (pinfunction "2_2") (pintype "passive"))
      (node (ref "C77") (pin "2") (pinfunction "2_2") (pintype "passive"))
      (node (ref "C78") (pin "2") (pinfunction "2_2") (pintype "passive"))
      (node (ref "C8") (pin "1") (pinfunction "1_1") (pintype "passive"))
      (node (ref "C80") (pin "1") (pinfunction "1_1") (pintype "passive"))
      (node (ref "C81") (pin "1") (pinfunction "1_1") (pintype "passive"))
      (node (ref "C82") (pin "1") (pinfunction "1_1") (pintype "passive"))
      (node (ref "C83") (pin "1") (pinfunction "1_1") (pintype "passive"))
      (node (ref "C84") (pin "1") (pinfunction "1_1") (pintype "passive"))
      (node (ref "C85") (pin "1") (pinfunction "1_1") (pintype "passive"))
      (node (ref "C86") (pin "1") (pinfunction "1_1") (pintype "passive"))
      (node (ref "C87") (pin "1") (pinfunction "1_1") (pintype "passive"))
      (node (ref "C88") (pin "1") (pinfunction "1_1") (pintype "passive"))
      (node (ref "C89") (pin "1") (pinfunction "1_1") (pintype "passive"))
      (node (ref "C90") (pin "1") (pinfunction "1_1") (pintype "passive"))
      (node (ref "C91") (pin "1") (pinfunction "1_1") (pintype "passive"))
      (node (ref "C92") (pin "1") (pinfunction "1_1") (pintype "passive"))
      (node (ref "C93") (pin "1") (pinfunction "1_1") (pintype "passive"))
      (node (ref "C94") (pin "1") (pinfunction "1_1") (pintype "passive"))
      (node (ref "C95") (pin "1") (pinfunction "1_1") (pintype "passive"))
      (node (ref "C96") (pin "1") (pinfunction "1_1") (pintype "passive"))
      (node (ref "C97") (pin "2") (pinfunction "2_2") (pintype "passive"))
      (node (ref "D1") (pin "2") (pinfunction "K_2") (pintype "passive"))
      (node (ref "J1") (pin "2") (pinfunction "2_2") (pintype "power_in"))
      (node (ref "J1") (pin "3") (pinfunction "3_3") (pintype "power_in"))
      (node (ref "J2") (pin "2") (pinfunction "GND_2") (pintype "power_in"))
      (node (ref "J2") (pin "3") (pinfunction "GND_3") (pintype "power_in"))
      (node (ref "J2") (pin "4") (pinfunction "GND_4") (pintype "power_in"))
      (node (ref "J2") (pin "5") (pinfunction "GND_5") (pintype "power_in"))
      (node (ref "J3") (pin "2") (pinfunction "GND_2") (pintype "power_in"))
      (node (ref "J3") (pin "3") (pinfunction "GND_3") (pintype "power_in"))
      (node (ref "J3") (pin "4") (pinfunction "GND_4") (pintype "power_in"))
      (node (ref "J3") (pin "5") (pinfunction "GND_5") (pintype "power_in"))
      (node (ref "K1") (pin "1") (pinfunction "1_1") (pintype "passive"))
      (node (ref "LL1") (pin "4") (pinfunction "Pri-_4") (pintype "passive"))
      (node (ref "LL2") (pin "3") (pinfunction "Sec+_3") (pintype "passive"))
      (node (ref "P1") (pin "1") (pinfunction "1_1") (pintype "passive"))
      (node (ref "P10") (pin "29") (pinfunction "29_29") (pintype "passive"))
      (node (ref "P2") (pin "10") (pinfunction "10_10") (pintype "passive"))
      (node (ref "P2") (pin "2") (pinfunction "2_2") (pintype "passive"))
      (node (ref "P3") (pin "1") (pinfunction "1_1") (pintype "passive"))
      (node (ref "P4") (pin "10") (pinfunction "10_10") (pintype "passive"))
      (node (ref "P4") (pin "2") (pinfunction "2_2") (pintype "passive"))
      (node (ref "P5") (pin "1") (pinfunction "1_1") (pintype "passive"))
      (node (ref "R10") (pin "2") (pinfunction "2_2") (pintype "passive"))
      (node (ref "R11") (pin "2") (pinfunction "2_2") (pintype "passive"))
      (node (ref "R16") (pin "2") (pinfunction "2_2") (pintype "passive"))
      (node (ref "R2") (pin "2") (pinfunction "2_2") (pintype "passive"))
      (node (ref "R22") (pin "2") (pinfunction "2_2") (pintype "passive"))
      (node (ref "R25") (pin "1") (pinfunction "1_1") (pintype "passive"))
      (node (ref "R31") (pin "2") (pinfunction "2_2") (pintype "passive"))
      (node (ref "R34") (pin "2") (pinfunction "2_2") (pintype "passive"))
      (node (ref "R35") (pin "2") (pinfunction "2_2") (pintype "passive"))
      (node (ref "R4") (pin "2") (pinfunction "2_2") (pintype "passive"))
      (node (ref "R44") (pin "1") (pinfunction "1_1") (pintype "passive"))
      (node (ref "R48") (pin "2") (pinfunction "2_2") (pintype "passive"))
      (node (ref "R49") (pin "2") (pinfunction "2_2") (pintype "passive"))
      (node (ref "R55") (pin "1") (pinfunction "1_1") (pintype "passive"))
      (node (ref "R57") (pin "2") (pinfunction "2_2") (pintype "passive"))
      (node (ref "R6") (pin "2") (pinfunction "2_2") (pintype "passive"))
      (node (ref "R60") (pin "1") (pinfunction "1_1") (pintype "passive"))
      (node (ref "R64") (pin "2") (pinfunction "2_2") (pintype "passive"))
      (node (ref "R8") (pin "2") (pinfunction "2_2") (pintype "passive"))
      (node (ref "T1") (pin "2") (pinfunction "GND1_2") (pintype "passive"))
      (node (ref "T2") (pin "2") (pinfunction "GND2_2") (pintype "passive"))
      (node (ref "T3") (pin "1") (pinfunction "G_1") (pintype "passive"))
      (node (ref "T4") (pin "1") (pinfunction "G_1") (pintype "passive"))
      (node (ref "U1") (pin "1") (pinfunction "CPGND_1") (pintype "passive"))
      (node (ref "U1") (pin "10") (pinfunction "L2_10") (pintype "passive"))
      (node (ref "U1") (pin "11") (pinfunction "AGND_11") (pintype "passive"))
      (node (ref "U1") (pin "15") (pinfunction "DGND_15") (pintype "passive"))
      (node (ref "U1") (pin "22") (pinfunction "AGND_22") (pintype "passive"))
      (node (ref "U1") (pin "3") (pinfunction "AGND_3") (pintype "passive"))
      (node (ref "U1") (pin "8") (pinfunction "AGND_8") (pintype "passive"))
      (node (ref "U1") (pin "9") (pinfunction "L1_9") (pintype "passive"))
      (node (ref "U2") (pin "11") (pinfunction "GND_11") (pintype "passive"))
      (node (ref "U2") (pin "12") (pinfunction "GND_12") (pintype "passive"))
      (node (ref "U2") (pin "14") (pinfunction "GND_14") (pintype "passive"))
      (node (ref "U2") (pin "17") (pinfunction "GND_17") (pintype "passive"))
      (node (ref "U2") (pin "19") (pinfunction "GND_19") (pintype "passive"))
      (node (ref "U2") (pin "2") (pinfunction "GND_2") (pintype "passive"))
      (node (ref "U2") (pin "20") (pinfunction "GND_20") (pintype "passive"))
      (node (ref "U2") (pin "23") (pinfunction "GND_23") (pintype "passive"))
      (node (ref "U2") (pin "5") (pinfunction "GND_5") (pintype "passive"))
      (node (ref "U2") (pin "8") (pinfunction "GND_8") (pintype "passive"))
      (node (ref "U3") (pin "2") (pinfunction "GND_2") (pintype "passive"))
      (node (ref "U3") (pin "4") (pinfunction "GND_4") (pintype "passive"))
      (node (ref "U4") (pin "100") (pinfunction "GND_100") (pintype "power_in"))
      (node (ref "U4") (pin "111") (pinfunction "GND_111") (pintype "power_in"))
      (node (ref "U4") (pin "119") (pinfunction "GND_119") (pintype "power_in"))
      (node (ref "U4") (pin "124") (pinfunction "GND_124") (pintype "power_in"))
      (node (ref "U4") (pin "125") (pinfunction "MSEL1_125") (pintype "input"))
      (node (ref "U4") (pin "126") (pinfunction "MSEL0_126") (pintype "input"))
      (node (ref "U4") (pin "140") (pinfunction "GND_140") (pintype "power_in"))
      (node (ref "U4") (pin "153") (pinfunction "GND_153") (pintype "power_in"))
      (node (ref "U4") (pin "154") (pinfunction "GND_PLL2_154") (pintype "power_in"))
      (node (ref "U4") (pin "156") (pinfunction "GND_PLL2_156") (pintype "power_in"))
      (node (ref "U4") (pin "158") (pinfunction "GNDA_PLL2_158") (pintype "power_in"))
      (node (ref "U4") (pin "159") (pinfunction "GND_159") (pintype "power_in"))
      (node (ref "U4") (pin "167") (pinfunction "GND_167") (pintype "power_in"))
      (node (ref "U4") (pin "174") (pinfunction "GND_174") (pintype "power_in"))
      (node (ref "U4") (pin "177") (pinfunction "GND_177") (pintype "power_in"))
      (node (ref "U4") (pin "184") (pinfunction "GND_184") (pintype "power_in"))
      (node (ref "U4") (pin "186") (pinfunction "GND_186") (pintype "power_in"))
      (node (ref "U4") (pin "196") (pinfunction "GND_196") (pintype "power_in"))
      (node (ref "U4") (pin "204") (pinfunction "GND_204") (pintype "power_in"))
      (node (ref "U4") (pin "25") (pinfunction "GND_25") (pintype "power_in"))
      (node (ref "U4") (pin "36") (pinfunction "GND_36") (pintype "power_in"))
      (node (ref "U4") (pin "38") (pinfunction "GND_38") (pintype "power_in"))
      (node (ref "U4") (pin "49") (pinfunction "GND_49") (pintype "power_in"))
      (node (ref "U4") (pin "50") (pinfunction "GND_PLL1_50") (pintype "power_in"))
      (node (ref "U4") (pin "52") (pinfunction "GND_PLL1_52") (pintype "power_in"))
      (node (ref "U4") (pin "54") (pinfunction "GNDA_PLL1_54") (pintype "power_in"))
      (node (ref "U4") (pin "55") (pinfunction "GND_55") (pintype "power_in"))
      (node (ref "U4") (pin "65") (pinfunction "GND_65") (pintype "power_in"))
      (node (ref "U4") (pin "73") (pinfunction "GND_73") (pintype "power_in"))
      (node (ref "U4") (pin "78") (pinfunction "GND_78") (pintype "power_in"))
      (node (ref "U4") (pin "85") (pinfunction "GND_85") (pintype "power_in"))
      (node (ref "U4") (pin "9") (pinfunction "GND_9") (pintype "power_in"))
      (node (ref "U4") (pin "93") (pinfunction "GND_93") (pintype "power_in"))
      (node (ref "U5") (pin "1") (pinfunction "AGND_1") (pintype "power_in"))
      (node (ref "U5") (pin "12") (pinfunction "AGND_12") (pintype "power_in"))
      (node (ref "U5") (pin "15") (pinfunction "EXTLO_15") (pintype "bidirectional"))
      (node (ref "U5") (pin "17") (pinfunction "AGND_17") (pintype "power_in"))
      (node (ref "U5") (pin "19") (pinfunction "AGND_19") (pintype "power_in"))
      (node (ref "U5") (pin "22") (pinfunction "AGND_22") (pintype "power_in"))
      (node (ref "U5") (pin "25") (pinfunction "AGND_25") (pintype "power_in"))
      (node (ref "U5") (pin "27") (pinfunction "DGND_27") (pintype "power_in"))
      (node (ref "U5") (pin "38") (pinfunction "DGND_38") (pintype "power_in"))
      (node (ref "U5") (pin "4") (pinfunction "AGND_4") (pintype "power_in"))
      (node (ref "U5") (pin "45") (pinfunction "DGND_45") (pintype "power_in"))
      (node (ref "U5") (pin "47") (pinfunction "IOGND_47") (pintype "bidirectional"))
      (node (ref "U5") (pin "57") (pinfunction "DGND_57") (pintype "power_in"))
      (node (ref "U5") (pin "58") (pinfunction "CLKGND_58") (pintype "power_in"))
      (node (ref "U5") (pin "64") (pinfunction "CLKGND_64") (pintype "power_in"))
      (node (ref "U5") (pin "65") (pinfunction "PLLGND_65") (pintype "power_in"))
      (node (ref "U5") (pin "67") (pinfunction "PLLVDD_67") (pintype "power_in"))
      (node (ref "U5") (pin "69") (pinfunction "DGND_69") (pintype "power_in"))
      (node (ref "U5") (pin "7") (pinfunction "AGND_7") (pintype "power_in"))
      (node (ref "U5") (pin "79") (pinfunction "IOGND_79") (pintype "power_in"))
      (node (ref "U5") (pin "81") (pinfunction "DGND_81") (pintype "power_in"))
      (node (ref "U5") (pin "88") (pinfunction "DGND_88") (pintype "passive"))
      (node (ref "U5") (pin "9") (pinfunction "AGND_9") (pintype "passive"))
      (node (ref "U5") (pin "93") (pinfunction "DGND_93") (pintype "power_in"))
      (node (ref "U5") (pin "98") (pinfunction "QFLAG_98") (pintype "bidirectional"))
      (node (ref "U5") (pin "99") (pinfunction "DGND_99") (pintype "power_in"))
      (node (ref "U6") (pin "4") (pinfunction "GND_4") (pintype "power_in"))
      (node (ref "U7") (pin "10") (pinfunction "VSS_5_10") (pintype "power_in"))
      (node (ref "U7") (pin "19") (pinfunction "VSSA_19") (pintype "power_in"))
      (node (ref "U7") (pin "20") (pinfunction "VREF-_20") (pintype "power_in"))
      (node (ref "U7") (pin "27") (pinfunction "VSS_4_27") (pintype "power_in"))
      (node (ref "U7") (pin "49") (pinfunction "VSS_1_49") (pintype "power_in"))
      (node (ref "U7") (pin "74") (pinfunction "VSS_2_74") (pintype "power_in"))
      (node (ref "U7") (pin "94") (pinfunction "BOOT0_94") (pintype "input"))
      (node (ref "U7") (pin "99") (pinfunction "VSS_3_99") (pintype "power_in"))
      (node (ref "Y1") (pin "2") (pinfunction "GND_2") (pintype "passive"))
    )
    (net (code "155") (name "Net-(C2-Pad1)") (class "Default")
      (node (ref "C2") (pin "1") (pinfunction "1_1") (pintype "passive"))
      (node (ref "J1") (pin "1") (pinfunction "1_1") (pintype "power_in"))
      (node (ref "L1") (pin "1") (pinfunction "1_1") (pintype "passive"))
      (node (ref "P1") (pin "2") (pinfunction "2_2") (pintype "passive"))
    )
    (net (code "156") (name "Net-(C4-Pad2)") (class "Default")
      (node (ref "C4") (pin "2") (pinfunction "2_2") (pintype "passive"))
      (node (ref "C9") (pin "2") (pinfunction "2_2") (pintype "passive"))
      (node (ref "R11") (pin "1") (pinfunction "1_1") (pintype "passive"))
    )
    (net (code "157") (name "Net-(C15-Pad1)") (class "Default")
      (node (ref "C15") (pin "1") (pinfunction "1_1") (pintype "passive"))
      (node (ref "L4") (pin "2") (pinfunction "2_2") (pintype "passive"))
      (node (ref "R19") (pin "2") (pinfunction "2_2") (pintype "passive"))
    )
    (net (code "158") (name "Net-(C15-Pad2)") (class "Default")
      (node (ref "C15") (pin "2") (pinfunction "2_2") (pintype "passive"))
      (node (ref "L3") (pin "2") (pinfunction "2_2") (pintype "passive"))
      (node (ref "R18") (pin "2") (pinfunction "2_2") (pintype "passive"))
    )
    (net (code "159") (name "Net-(C16-Pad1)") (class "Default")
      (node (ref "C16") (pin "1") (pinfunction "1_1") (pintype "passive"))
      (node (ref "L6") (pin "2") (pinfunction "2_2") (pintype "passive"))
      (node (ref "R21") (pin "2") (pinfunction "2_2") (pintype "passive"))
    )
    (net (code "160") (name "Net-(C16-Pad2)") (class "Default")
      (node (ref "C16") (pin "2") (pinfunction "2_2") (pintype "passive"))
      (node (ref "L5") (pin "2") (pinfunction "2_2") (pintype "passive"))
      (node (ref "R20") (pin "2") (pinfunction "2_2") (pintype "passive"))
    )
    (net (code "161") (name "Net-(C19-Pad2)") (class "Default")
      (node (ref "C19") (pin "2") (pinfunction "2_2") (pintype "passive"))
      (node (ref "L7") (pin "2") (pinfunction "2_2") (pintype "passive"))
      (node (ref "R18") (pin "1") (pinfunction "1_1") (pintype "passive"))
      (node (ref "R28") (pin "2") (pinfunction "2_2") (pintype "passive"))
    )
    (net (code "162") (name "Net-(C20-Pad2)") (class "Default")
      (node (ref "C20") (pin "2") (pinfunction "2_2") (pintype "passive"))
      (node (ref "L8") (pin "1") (pinfunction "1_1") (pintype "passive"))
      (node (ref "R19") (pin "1") (pinfunction "1_1") (pintype "passive"))
      (node (ref "R29") (pin "2") (pinfunction "2_2") (pintype "passive"))
    )
    (net (code "163") (name "Net-(C21-Pad2)") (class "Default")
      (node (ref "C21") (pin "2") (pinfunction "2_2") (pintype "passive"))
      (node (ref "L9") (pin "2") (pinfunction "2_2") (pintype "passive"))
      (node (ref "R20") (pin "1") (pinfunction "1_1") (pintype "passive"))
      (node (ref "R26") (pin "2") (pinfunction "2_2") (pintype "passive"))
    )
    (net (code "164") (name "Net-(C22-Pad2)") (class "Default")
      (node (ref "C22") (pin "2") (pinfunction "2_2") (pintype "passive"))
      (node (ref "L10") (pin "1") (pinfunction "1_1") (pintype "passive"))
      (node (ref "R21") (pin "1") (pinfunction "1_1") (pintype "passive"))
      (node (ref "R27") (pin "2") (pinfunction "2_2") (pintype "passive"))
    )
    (net (code "165") (name "Net-(C30-Pad1)") (class "Default")
      (node (ref "C30") (pin "1") (pinfunction "1_1") (pintype "passive"))
      (node (ref "L14") (pin "1") (pinfunction "1_1") (pintype "passive"))
    )
    (net (code "166") (name "Net-(C31-Pad1)") (class "Default")
      (node (ref "C31") (pin "1") (pinfunction "1_1") (pintype "passive"))
      (node (ref "L15") (pin "1") (pinfunction "1_1") (pintype "passive"))
    )
    (net (code "167") (name "Net-(C33-Pad2)") (class "Default")
      (node (ref "C33") (pin "2") (pinfunction "2_2") (pintype "passive"))
      (node (ref "R31") (pin "1") (pinfunction "1_1") (pintype "passive"))
    )
    (net (code "168") (name "Net-(C35-Pad1)") (class "Default")
      (node (ref "C35") (pin "1") (pinfunction "1_1") (pintype "passive"))
      (node (ref "L14") (pin "2") (pinfunction "2_2") (pintype "passive"))
    )
    (net (code "169") (name "Net-(C36-Pad1)") (class "Default")
      (node (ref "C36") (pin "1") (pinfunction "1_1") (pintype "passive"))
      (node (ref "R30") (pin "1") (pinfunction "1_1") (pintype "passive"))
    )
    (net (code "170") (name "Net-(C40-Pad2)") (class "Default")
      (node (ref "C40") (pin "2") (pinfunction "2_2") (pintype "passive"))
      (node (ref "C41") (pin "1") (pinfunction "1_1") (pintype "passive"))
      (node (ref "C42") (pin "2") (pinfunction "2_2") (pintype "passive"))
      (node (ref "C43") (pin "1") (pinfunction "1_1") (pintype "passive"))
      (node (ref "C45") (pin "2") (pinfunction "2_2") (pintype "passive"))
      (node (ref "C46") (pin "1") (pinfunction "1_1") (pintype "passive"))
      (node (ref "C49") (pin "2") (pinfunction "2_2") (pintype "passive"))
      (node (ref "C50") (pin "1") (pinfunction "1_1") (pintype "passive"))
      (node (ref "L24") (pin "1") (pinfunction "1_1") (pintype "passive"))
      (node (ref "U2") (pin "18") (pinfunction "VCC_18") (pintype "passive"))
      (node (ref "U2") (pin "24") (pinfunction "VCC_24") (pintype "passive"))
    )
    (net (code "171") (name "Net-(C51-Pad1)") (class "Default")
      (node (ref "C51") (pin "1") (pinfunction "1_1") (pintype "passive"))
      (node (ref "R33") (pin "2") (pinfunction "2_2") (pintype "passive"))
      (node (ref "R34") (pin "1") (pinfunction "1_1") (pintype "passive"))
    )
    (net (code "172") (name "Net-(C80-Pad2)") (class "Default")
      (node (ref "C80") (pin "2") (pinfunction "2_2") (pintype "passive"))
      (node (ref "R54") (pin "2") (pinfunction "2_2") (pintype "passive"))
      (node (ref "U5") (pin "56") (pinfunction "DVDD_56") (pintype "power_in"))
    )
    (net (code "173") (name "Net-(D1-A)") (class "Default")
      (node (ref "D1") (pin "1") (pinfunction "A_1") (pintype "passive"))
      (node (ref "R10") (pin "1") (pinfunction "1_1") (pintype "passive"))
      (node (ref "R17") (pin "2") (pinfunction "2_2") (pintype "passive"))
      (node (ref "R9") (pin "1") (pinfunction "1_1") (pintype "passive"))
    )
    (net (code "174") (name "Net-(D2-K)") (class "Default")
      (node (ref "D2") (pin "2") (pinfunction "K_2") (pintype "passive"))
      (node (ref "R25") (pin "2") (pinfunction "2_2") (pintype "passive"))
    )
    (net (code "175") (name "Net-(D4-A)") (class "Default")
      (node (ref "D4") (pin "1") (pinfunction "A_1") (pintype "passive"))
      (node (ref "R59") (pin "1") (pinfunction "1_1") (pintype "passive"))
      (node (ref "U4") (pin "107") (pinfunction "IO,_LVDS54n_(INIT_DONE)_107") (pintype "bidirectional"))
    )
    (net (code "176") (name "Net-(D4-K)") (class "Default")
      (node (ref "D4") (pin "2") (pinfunction "K_2") (pintype "passive"))
      (node (ref "R60") (pin "2") (pinfunction "2_2") (pintype "passive"))
    )
    (net (code "177") (name "Net-(D5-K)") (class "Default")
      (node (ref "D5") (pin "2") (pinfunction "K_2") (pintype "passive"))
      (node (ref "R64") (pin "1") (pinfunction "1_1") (pintype "passive"))
    )
    (net (code "178") (name "Net-(J2-Signal)") (class "Default")
      (node (ref "J2") (pin "1") (pinfunction "Signal_1") (pintype "input"))
      (node (ref "L15") (pin "2") (pinfunction "2_2") (pintype "passive"))
    )
    (net (code "179") (name "Net-(L7-Pad1)") (class "Default")
      (node (ref "L7") (pin "1") (pinfunction "1_1") (pintype "passive"))
      (node (ref "R23") (pin "1") (pinfunction "1_1") (pintype "passive"))
    )
    (net (code "180") (name "Net-(L8-Pad2)") (class "Default")
      (node (ref "L8") (pin "2") (pinfunction "2_2") (pintype "passive"))
      (node (ref "R23") (pin "2") (pinfunction "2_2") (pintype "passive"))
    )
    (net (code "181") (name "Net-(L9-Pad1)") (class "Default")
      (node (ref "L9") (pin "1") (pinfunction "1_1") (pintype "passive"))
      (node (ref "R24") (pin "1") (pinfunction "1_1") (pintype "passive"))
    )
    (net (code "182") (name "Net-(L10-Pad2)") (class "Default")
      (node (ref "L10") (pin "2") (pinfunction "2_2") (pintype "passive"))
      (node (ref "R24") (pin "2") (pinfunction "2_2") (pintype "passive"))
    )
    (net (code "183") (name "Net-(LL1-Pri+)") (class "Default")
      (node (ref "LL1") (pin "5") (pinfunction "Pri+_5") (pintype "passive"))
      (node (ref "R33") (pin "1") (pinfunction "1_1") (pintype "passive"))
      (node (ref "R35") (pin "1") (pinfunction "1_1") (pintype "passive"))
    )
    (net (code "184") (name "Net-(LL2-Sec-)") (class "Default")
      (node (ref "C69") (pin "1") (pinfunction "1_1") (pintype "passive"))
      (node (ref "LL2") (pin "1") (pinfunction "Sec-_1") (pintype "passive"))
    )
    (net (code "185") (name "Net-(T1-Vin)") (class "Default")
      (node (ref "C7") (pin "1") (pinfunction "1_1") (pintype "passive"))
      (node (ref "L1") (pin "2") (pinfunction "2_2") (pintype "passive"))
      (node (ref "T1") (pin "1") (pinfunction "Vin_1") (pintype "passive"))
    )
    (net (code "186") (name "Net-(U1-CC)") (class "Default")
      (node (ref "C11") (pin "1") (pinfunction "1_1") (pintype "passive"))
      (node (ref "U1") (pin "12") (pinfunction "CC_12") (pintype "passive"))
    )
    (net (code "187") (name "Net-(U1-CE)") (class "Default")
      (node (ref "R15") (pin "1") (pinfunction "1_1") (pintype "passive"))
      (node (ref "U1") (pin "23") (pinfunction "CE_23") (pintype "passive"))
    )
    (net (code "188") (name "Net-(U1-CLK)") (class "Default")
      (node (ref "R12") (pin "1") (pinfunction "1_1") (pintype "passive"))
      (node (ref "U1") (pin "17") (pinfunction "CLK_17") (pintype "passive"))
    )
    (net (code "189") (name "Net-(U1-CN)") (class "Default")
      (node (ref "C12") (pin "2") (pinfunction "2_2") (pintype "passive"))
      (node (ref "C14") (pin "2") (pinfunction "2_2") (pintype "passive"))
      (node (ref "U1") (pin "14") (pinfunction "CN_14") (pintype "passive"))
    )
    (net (code "190") (name "Net-(U1-CP)") (class "Default")
      (node (ref "C32") (pin "1") (pinfunction "1_1") (pintype "passive"))
      (node (ref "C33") (pin "1") (pinfunction "1_1") (pintype "passive"))
      (node (ref "R32") (pin "1") (pinfunction "1_1") (pintype "passive"))
      (node (ref "U1") (pin "24") (pinfunction "CP_24") (pintype "passive"))
    )
    (net (code "191") (name "Net-(U1-DATA)") (class "Default")
      (node (ref "R13") (pin "1") (pinfunction "1_1") (pintype "passive"))
      (node (ref "U1") (pin "18") (pinfunction "DATA_18") (pintype "passive"))
    )
    (net (code "192") (name "Net-(U1-LE)") (class "Default")
      (node (ref "R14") (pin "1") (pinfunction "1_1") (pintype "passive"))
      (node (ref "U1") (pin "19") (pinfunction "LE_19") (pintype "passive"))
    )
    (net (code "193") (name "Net-(U1-MUXOUT)") (class "Default")
      (node (ref "R17") (pin "1") (pinfunction "1_1") (pintype "passive"))
      (node (ref "U1") (pin "20") (pinfunction "MUXOUT_20") (pintype "passive"))
    )
    (net (code "194") (name "Net-(U1-REFIN)") (class "Default")
      (node (ref "C9") (pin "1") (pinfunction "1_1") (pintype "passive"))
      (node (ref "U1") (pin "16") (pinfunction "REFIN_16") (pintype "passive"))
    )
    (net (code "195") (name "Net-(U1-RFOUT)") (class "Default")
      (node (ref "C31") (pin "2") (pinfunction "2_2") (pintype "passive"))
      (node (ref "L12") (pin "1") (pinfunction "1_1") (pintype "passive"))
      (node (ref "U1") (pin "4") (pinfunction "RFOUT_4") (pintype "passive"))
    )
    (net (code "196") (name "Net-(U1-RFOUTn)") (class "Default")
      (node (ref "C30") (pin "2") (pinfunction "2_2") (pintype "passive"))
      (node (ref "L13") (pin "1") (pinfunction "1_1") (pintype "passive"))
      (node (ref "U1") (pin "5") (pinfunction "RFOUTn_5") (pintype "passive"))
    )
    (net (code "197") (name "Net-(U1-RSET)") (class "Default")
      (node (ref "R16") (pin "1") (pinfunction "1_1") (pintype "passive"))
      (node (ref "U1") (pin "13") (pinfunction "RSET_13") (pintype "passive"))
    )
    (net (code "198") (name "Net-(U1-VTUNE)") (class "Default")
      (node (ref "C38") (pin "1") (pinfunction "1_1") (pintype "passive"))
      (node (ref "R32") (pin "2") (pinfunction "2_2") (pintype "passive"))
      (node (ref "U1") (pin "7") (pinfunction "VTUNE_7") (pintype "passive"))
    )
    (net (code "199") (name "Net-(U2-BBIN)") (class "Default")
      (node (ref "R29") (pin "1") (pinfunction "1_1") (pintype "passive"))
      (node (ref "U2") (pin "22") (pinfunction "BBIN_22") (pintype "passive"))
    )
    (net (code "200") (name "Net-(U2-BBIP)") (class "Default")
      (node (ref "R28") (pin "1") (pinfunction "1_1") (pintype "passive"))
      (node (ref "U2") (pin "21") (pinfunction "BBIP_21") (pintype "passive"))
    )
    (net (code "201") (name "Net-(U2-BBQN)") (class "Default")
      (node (ref "R27") (pin "1") (pinfunction "1_1") (pintype "passive"))
      (node (ref "U2") (pin "9") (pinfunction "BBQN_9") (pintype "passive"))
    )
    (net (code "202") (name "Net-(U2-BBQP)") (class "Default")
      (node (ref "R26") (pin "1") (pinfunction "1_1") (pintype "passive"))
      (node (ref "U2") (pin "10") (pinfunction "BBQP_10") (pintype "passive"))
    )
    (net (code "203") (name "Net-(U2-RF_OUT)") (class "Default")
      (node (ref "R30") (pin "2") (pinfunction "2_2") (pintype "passive"))
      (node (ref "U2") (pin "16") (pinfunction "RF_OUT_16") (pintype "passive"))
    )
    (net (code "204") (name "Net-(U3-RF_IN)") (class "Default")
      (node (ref "C35") (pin "2") (pinfunction "2_2") (pintype "passive"))
      (node (ref "U3") (pin "1") (pinfunction "RF_IN_1") (pintype "passive"))
    )
    (net (code "205") (name "Net-(U3-RF_OUT)") (class "Default")
      (node (ref "C51") (pin "2") (pinfunction "2_2") (pintype "passive"))
      (node (ref "L22") (pin "2") (pinfunction "2_2") (pintype "passive"))
      (node (ref "U3") (pin "3") (pinfunction "RF_OUT_3") (pintype "passive"))
    )
    (net (code "206") (name "Net-(U4C-IO,_PLL2_OUTp)") (class "Default")
      (node (ref "C69") (pin "2") (pinfunction "2_2") (pintype "passive"))
      (node (ref "U4") (pin "151") (pinfunction "IO,_PLL2_OUTp_151") (pintype "bidirectional"))
    )
    (net (code "207") (name "Net-(U5-BIASJ)") (class "Default")
      (node (ref "R48") (pin "1") (pinfunction "1_1") (pintype "passive"))
      (node (ref "U5") (pin "13") (pinfunction "BIASJ_13") (pintype "bidirectional"))
    )
    (net (code "208") (name "Net-(U5-DA0(LSB&MSB))") (class "Default")
      (node (ref "RN1") (pin "8") (pintype "passive"))
      (node (ref "U5") (pin "55") (pinfunction "DA0(LSB&MSB)_55") (pintype "bidirectional"))
    )
    (net (code "209") (name "Net-(U5-DA1)") (class "Default")
      (node (ref "RN1") (pin "7") (pintype "passive"))
      (node (ref "U5") (pin "54") (pinfunction "DA1_54") (pintype "bidirectional"))
    )
    (net (code "210") (name "Net-(U5-DA2)") (class "Default")
      (node (ref "RN1") (pin "6") (pintype "passive"))
      (node (ref "U5") (pin "53") (pinfunction "DA2_53") (pintype "bidirectional"))
    )
    (net (code "211") (name "Net-(U5-DA3)") (class "Default")
      (node (ref "RN1") (pin "5") (pintype "passive"))
      (node (ref "U5") (pin "52") (pinfunction "DA3_52") (pintype "bidirectional"))
    )
    (net (code "212") (name "Net-(U5-DA4)") (class "Default")
      (node (ref "RN2") (pin "8") (pintype "passive"))
      (node (ref "U5") (pin "51") (pinfunction "DA4_51") (pintype "bidirectional"))
    )
    (net (code "213") (name "Net-(U5-DA5)") (class "Default")
      (node (ref "RN2") (pin "7") (pintype "passive"))
      (node (ref "U5") (pin "50") (pinfunction "DA5_50") (pintype "bidirectional"))
    )
    (net (code "214") (name "Net-(U5-DA6)") (class "Default")
      (node (ref "RN2") (pin "6") (pintype "passive"))
      (node (ref "U5") (pin "49") (pinfunction "DA6_49") (pintype "bidirectional"))
    )
    (net (code "215") (name "Net-(U5-DA7)") (class "Default")
      (node (ref "RN2") (pin "5") (pintype "passive"))
      (node (ref "U5") (pin "48") (pinfunction "DA7_48") (pintype "bidirectional"))
    )
    (net (code "216") (name "Net-(U5-DA8)") (class "Default")
      (node (ref "RN3") (pin "8") (pintype "passive"))
      (node (ref "U5") (pin "43") (pinfunction "DA8_43") (pintype "bidirectional"))
    )
    (net (code "217") (name "Net-(U5-DA9)") (class "Default")
      (node (ref "RN3") (pin "7") (pintype "passive"))
      (node (ref "U5") (pin "42") (pinfunction "DA9_42") (pintype "bidirectional"))
    )
    (net (code "218") (name "Net-(U5-DA10)") (class "Default")
      (node (ref "RN3") (pin "6") (pintype "passive"))
      (node (ref "U5") (pin "41") (pinfunction "DA10_41") (pintype "bidirectional"))
    )
    (net (code "219") (name "Net-(U5-DA11)") (class "Default")
      (node (ref "RN3") (pin "5") (pintype "passive"))
      (node (ref "U5") (pin "40") (pinfunction "DA11_40") (pintype "bidirectional"))
    )
    (net (code "220") (name "Net-(U5-DA12)") (class "Default")
      (node (ref "RN4") (pin "8") (pintype "passive"))
      (node (ref "U5") (pin "39") (pinfunction "DA12_39") (pintype "bidirectional"))
    )
    (net (code "221") (name "Net-(U5-DA13)") (class "Default")
      (node (ref "RN4") (pin "7") (pintype "passive"))
      (node (ref "U5") (pin "36") (pinfunction "DA13_36") (pintype "bidirectional"))
    )
    (net (code "222") (name "Net-(U5-DA14)") (class "Default")
      (node (ref "RN4") (pin "6") (pintype "passive"))
      (node (ref "U5") (pin "35") (pinfunction "DA14_35") (pintype "bidirectional"))
    )
    (net (code "223") (name "Net-(U5-DA15(MSB&LSB))") (class "Default")
      (node (ref "RN4") (pin "5") (pintype "passive"))
      (node (ref "U5") (pin "34") (pinfunction "DA15(MSB&LSB)_34") (pintype "bidirectional"))
    )
    (net (code "224") (name "Net-(U5-DB0(LSB&MSB))") (class "Default")
      (node (ref "RN5") (pin "1") (pintype "passive"))
      (node (ref "U5") (pin "71") (pinfunction "DB0(LSB&MSB)_71") (pintype "bidirectional"))
    )
    (net (code "225") (name "Net-(U5-DB1)") (class "Default")
      (node (ref "RN5") (pin "2") (pintype "passive"))
      (node (ref "U5") (pin "72") (pinfunction "DB1_72") (pintype "bidirectional"))
    )
    (net (code "226") (name "Net-(U5-DB2)") (class "Default")
      (node (ref "RN5") (pin "3") (pintype "passive"))
      (node (ref "U5") (pin "73") (pinfunction "DB2_73") (pintype "bidirectional"))
    )
    (net (code "227") (name "Net-(U5-DB3)") (class "Default")
      (node (ref "RN5") (pin "4") (pintype "passive"))
      (node (ref "U5") (pin "74") (pinfunction "DB3_74") (pintype "bidirectional"))
    )
    (net (code "228") (name "Net-(U5-DB4)") (class "Default")
      (node (ref "RN6") (pin "1") (pintype "passive"))
      (node (ref "U5") (pin "75") (pinfunction "DB4_75") (pintype "bidirectional"))
    )
    (net (code "229") (name "Net-(U5-DB5)") (class "Default")
      (node (ref "RN6") (pin "2") (pintype "passive"))
      (node (ref "U5") (pin "76") (pinfunction "DB5_76") (pintype "bidirectional"))
    )
    (net (code "230") (name "Net-(U5-DB6)") (class "Default")
      (node (ref "RN6") (pin "3") (pintype "passive"))
      (node (ref "U5") (pin "77") (pinfunction "DB6_77") (pintype "bidirectional"))
    )
    (net (code "231") (name "Net-(U5-DB7)") (class "Default")
      (node (ref "RN6") (pin "4") (pintype "passive"))
      (node (ref "U5") (pin "78") (pinfunction "DB7_78") (pintype "bidirectional"))
    )
    (net (code "232") (name "Net-(U5-DB8)") (class "Default")
      (node (ref "RN7") (pin "1") (pintype "passive"))
      (node (ref "U5") (pin "83") (pinfunction "DB8_83") (pintype "bidirectional"))
    )
    (net (code "233") (name "Net-(U5-DB9)") (class "Default")
      (node (ref "RN7") (pin "2") (pintype "passive"))
      (node (ref "U5") (pin "84") (pinfunction "DB9_84") (pintype "bidirectional"))
    )
    (net (code "234") (name "Net-(U5-DB10)") (class "Default")
      (node (ref "RN7") (pin "3") (pintype "passive"))
      (node (ref "U5") (pin "85") (pinfunction "DB10_85") (pintype "bidirectional"))
    )
    (net (code "235") (name "Net-(U5-DB11)") (class "Default")
      (node (ref "RN7") (pin "4") (pintype "passive"))
      (node (ref "U5") (pin "86") (pinfunction "DB11_86") (pintype "bidirectional"))
    )
    (net (code "236") (name "Net-(U5-DB12)") (class "Default")
      (node (ref "RN8") (pin "1") (pintype "passive"))
      (node (ref "U5") (pin "87") (pinfunction "DB12_87") (pintype "bidirectional"))
    )
    (net (code "237") (name "Net-(U5-DB13)") (class "Default")
      (node (ref "RN8") (pin "2") (pintype "passive"))
      (node (ref "U5") (pin "90") (pinfunction "DB13_90") (pintype "bidirectional"))
    )
    (net (code "238") (name "Net-(U5-DB14)") (class "Default")
      (node (ref "RN8") (pin "3") (pintype "passive"))
      (node (ref "U5") (pin "91") (pinfunction "DB14_91") (pintype "bidirectional"))
    )
    (net (code "239") (name "Net-(U5-DB15(MSB&LSB))") (class "Default")
      (node (ref "RN8") (pin "4") (pintype "passive"))
      (node (ref "U5") (pin "92") (pinfunction "DB15(MSB&LSB)_92") (pintype "bidirectional"))
    )
    (net (code "240") (name "Net-(U5-EXTIO)") (class "Default")
      (node (ref "C65") (pin "2") (pinfunction "2_2") (pintype "passive"))
      (node (ref "U5") (pin "11") (pinfunction "EXTIO_11") (pintype "bidirectional"))
    )
    (net (code "241") (name "Net-(U5-PLLLOCK)") (class "Default")
      (node (ref "R51") (pin "2") (pinfunction "2_2") (pintype "passive"))
      (node (ref "U5") (pin "70") (pinfunction "PLLLOCK_70") (pintype "bidirectional"))
    )
    (net (code "242") (name "Net-(U5-SCLK)") (class "Default")
      (node (ref "R47") (pin "1") (pinfunction "1_1") (pintype "passive"))
      (node (ref "U5") (pin "29") (pinfunction "SCLK_29") (pintype "bidirectional"))
    )
    (net (code "243") (name "Net-(U5-SDENB)") (class "Default")
      (node (ref "R46") (pin "1") (pinfunction "1_1") (pintype "passive"))
      (node (ref "U5") (pin "28") (pinfunction "SDENB_28") (pintype "bidirectional"))
    )
    (net (code "244") (name "Net-(U5-SDIO)") (class "Default")
      (node (ref "R52") (pin "2") (pinfunction "2_2") (pintype "passive"))
      (node (ref "U5") (pin "30") (pinfunction "SDIO_30") (pintype "bidirectional"))
    )
    (net (code "245") (name "Net-(U5-SDO)") (class "Default")
      (node (ref "R53") (pin "2") (pinfunction "2_2") (pintype "passive"))
      (node (ref "U5") (pin "31") (pinfunction "SDO_31") (pintype "bidirectional"))
    )
    (net (code "246") (name "Net-(U5-TESTMODM)") (class "Default")
      (node (ref "R49") (pin "1") (pinfunction "1_1") (pintype "passive"))
      (node (ref "U5") (pin "97") (pinfunction "TESTMODM_97") (pintype "bidirectional"))
    )
    (net (code "247") (name "Net-(U5-TXENABLE)") (class "Default")
      (node (ref "R50") (pin "1") (pinfunction "1_1") (pintype "passive"))
      (node (ref "U5") (pin "33") (pinfunction "TXENABLE_33") (pintype "bidirectional"))
    )
    (net (code "248") (name "Net-(U7-OSC_IN)") (class "Default")
      (node (ref "C92") (pin "2") (pinfunction "2_2") (pintype "passive"))
      (node (ref "R62") (pin "2") (pinfunction "2_2") (pintype "passive"))
      (node (ref "U7") (pin "12") (pinfunction "OSC_IN_12") (pintype "input"))
      (node (ref "Y2") (pin "2") (pinfunction "OSC2_2") (pintype "passive"))
    )
    (net (code "249") (name "Net-(U7-OSC_OUT)") (class "Default")
      (node (ref "C93") (pin "2") (pinfunction "2_2") (pintype "passive"))
      (node (ref "R62") (pin "1") (pinfunction "1_1") (pintype "passive"))
      (node (ref "U7") (pin "13") (pinfunction "OSC_OUT_13") (pintype "output"))
      (node (ref "Y2") (pin "1") (pinfunction "OSC1_1") (pintype "passive"))
    )
    (net (code "250") (name "Net-(U7-VDDA)") (class "Default")
      (node (ref "C100") (pin "1") (pinfunction "1_1") (pintype "passive"))
      (node (ref "L25") (pin "2") (pinfunction "2_2") (pintype "passive"))
      (node (ref "U7") (pin "21") (pinfunction "VREF+_21") (pintype "power_in"))
      (node (ref "U7") (pin "22") (pinfunction "VDDA_22") (pintype "power_in"))
    )
    (net (code "251") (name "Net-(Y1-NC)") (class "Default")
      (node (ref "R22") (pin "1") (pinfunction "1_1") (pintype "passive"))
      (node (ref "Y1") (pin "1") (pinfunction "NC_1") (pintype "passive"))
    )
    (net (code "252") (name "Net-(Y1-OUT)") (class "Default")
      (node (ref "C26") (pin "2") (pinfunction "2_2") (pintype "passive"))
      (node (ref "Y1") (pin "3") (pinfunction "OUT_3") (pintype "passive"))
    )
    (net (code "253") (name "Net-(Y1-V+)") (class "Default")
      (node (ref "C10") (pin "1") (pinfunction "1_1") (pintype "passive"))
      (node (ref "C13") (pin "1") (pinfunction "1_1") (pintype "passive"))
      (node (ref "C8") (pin "2") (pinfunction "2_2") (pintype "passive"))
      (node (ref "L2") (pin "2") (pinfunction "2_2") (pintype "passive"))
      (node (ref "Y1") (pin "4") (pinfunction "V+_4") (pintype "passive"))
    )
    (net (code "254") (name "VCC1_2") (class "Default")
      (node (ref "C44") (pin "1") (pinfunction "1_1") (pintype "passive"))
      (node (ref "C48") (pin "2") (pinfunction "2_2") (pintype "passive"))
      (node (ref "C81") (pin "2") (pinfunction "2_2") (pintype "passive"))
      (node (ref "C86") (pin "2") (pinfunction "2_2") (pintype "passive"))
      (node (ref "C87") (pin "2") (pinfunction "2_2") (pintype "passive"))
      (node (ref "C88") (pin "2") (pinfunction "2_2") (pintype "passive"))
      (node (ref "C89") (pin "2") (pinfunction "2_2") (pintype "passive"))
      (node (ref "C90") (pin "2") (pinfunction "2_2") (pintype "passive"))
      (node (ref "C91") (pin "2") (pinfunction "2_2") (pintype "passive"))
      (node (ref "C94") (pin "2") (pinfunction "2_2") (pintype "passive"))
      (node (ref "L23") (pin "1") (pinfunction "1_1") (pintype "passive"))
      (node (ref "T3") (pin "2") (pinfunction "VOUT_2") (pintype "passive"))
      (node (ref "U4") (pin "120") (pinfunction "VCCINT_120") (pintype "power_in"))
      (node (ref "U4") (pin "157") (pinfunction "VCCA_PLL2_157") (pintype "power_in"))
      (node (ref "U4") (pin "178") (pinfunction "VCCINT_178") (pintype "power_in"))
      (node (ref "U4") (pin "190") (pinfunction "VCCINT_190") (pintype "power_in"))
      (node (ref "U4") (pin "32") (pinfunction "VCCINT_32") (pintype "power_in"))
      (node (ref "U4") (pin "51") (pinfunction "VCCD_PLL1_51") (pintype "power_in"))
      (node (ref "U4") (pin "66") (pinfunction "VCCINT_66") (pintype "power_in"))
      (node (ref "U4") (pin "79") (pinfunction "VCCINT_79") (pintype "power_in"))
    )
    (net (code "255") (name "VCC1_2_PLL") (class "Default")
      (node (ref "C95") (pin "2") (pinfunction "2_2") (pintype "passive"))
      (node (ref "C96") (pin "2") (pinfunction "2_2") (pintype "passive"))
      (node (ref "L23") (pin "2") (pinfunction "2_2") (pintype "passive"))
      (node (ref "U4") (pin "155") (pinfunction "VCCD_PLL2_155") (pintype "power_in"))
      (node (ref "U4") (pin "53") (pinfunction "VCCA_PLL1_53") (pintype "power_in"))
    )
    (net (code "256") (name "VCC1_8") (class "Default")
      (node (ref "C47") (pin "1") (pinfunction "1_1") (pintype "passive"))
      (node (ref "C52") (pin "2") (pinfunction "2_2") (pintype "passive"))
      (node (ref "C71") (pin "1") (pinfunction "1_1") (pintype "passive"))
      (node (ref "C72") (pin "1") (pinfunction "1_1") (pintype "passive"))
      (node (ref "C73") (pin "1") (pinfunction "1_1") (pintype "passive"))
      (node (ref "C74") (pin "1") (pinfunction "1_1") (pintype "passive"))
      (node (ref "C75") (pin "1") (pinfunction "1_1") (pintype "passive"))
      (node (ref "C76") (pin "1") (pinfunction "1_1") (pintype "passive"))
      (node (ref "C77") (pin "1") (pinfunction "1_1") (pintype "passive"))
      (node (ref "C78") (pin "1") (pinfunction "1_1") (pintype "passive"))
      (node (ref "R54") (pin "1") (pinfunction "1_1") (pintype "passive"))
      (node (ref "T4") (pin "2") (pinfunction "VOUT_2") (pintype "passive"))
      (node (ref "U5") (pin "100") (pinfunction "DVDD_100") (pintype "power_in"))
      (node (ref "U5") (pin "26") (pinfunction "DVDD_26") (pintype "power_in"))
      (node (ref "U5") (pin "32") (pinfunction "DVDD_32") (pintype "power_in"))
      (node (ref "U5") (pin "37") (pinfunction "DVDD_37") (pintype "power_in"))
      (node (ref "U5") (pin "44") (pinfunction "DVDD_44") (pintype "power_in"))
      (node (ref "U5") (pin "68") (pinfunction "DVDD_68") (pintype "power_in"))
      (node (ref "U5") (pin "82") (pinfunction "DVDD_82") (pintype "power_in"))
      (node (ref "U5") (pin "89") (pinfunction "DVDD_89") (pintype "passive"))
    )
    (net (code "257") (name "VCC3_3") (class "Default")
      (node (ref "C103") (pin "2") (pinfunction "2_2") (pintype "passive"))
      (node (ref "C104") (pin "2") (pinfunction "2_2") (pintype "passive"))
      (node (ref "C105") (pin "2") (pinfunction "2_2") (pintype "passive"))
      (node (ref "C106") (pin "2") (pinfunction "2_2") (pintype "passive"))
      (node (ref "C107") (pin "2") (pinfunction "2_2") (pintype "passive"))
      (node (ref "C108") (pin "2") (pinfunction "2_2") (pintype "passive"))
      (node (ref "C109") (pin "2") (pinfunction "2_2") (pintype "passive"))
      (node (ref "C110") (pin "2") (pinfunction "2_2") (pintype "passive"))
      (node (ref "C112") (pin "2") (pinfunction "2_2") (pintype "passive"))
      (node (ref "C113") (pin "2") (pinfunction "2_2") (pintype "passive"))
      (node (ref "C114") (pin "2") (pinfunction "2_2") (pintype "passive"))
      (node (ref "C115") (pin "2") (pinfunction "2_2") (pintype "passive"))
      (node (ref "C116") (pin "2") (pinfunction "2_2") (pintype "passive"))
      (node (ref "C117") (pin "2") (pinfunction "2_2") (pintype "passive"))
      (node (ref "C118") (pin "2") (pinfunction "2_2") (pintype "passive"))
      (node (ref "C119") (pin "2") (pinfunction "2_2") (pintype "passive"))
      (node (ref "C120") (pin "2") (pinfunction "2_2") (pintype "passive"))
      (node (ref "C121") (pin "2") (pinfunction "2_2") (pintype "passive"))
      (node (ref "C122") (pin "2") (pinfunction "2_2") (pintype "passive"))
      (node (ref "C123") (pin "2") (pinfunction "2_2") (pintype "passive"))
      (node (ref "C124") (pin "2") (pinfunction "2_2") (pintype "passive"))
      (node (ref "C125") (pin "2") (pinfunction "2_2") (pintype "passive"))
      (node (ref "C126") (pin "2") (pinfunction "2_2") (pintype "passive"))
      (node (ref "C127") (pin "2") (pinfunction "2_2") (pintype "passive"))
      (node (ref "C128") (pin "2") (pinfunction "2_2") (pintype "passive"))
      (node (ref "C129") (pin "2") (pinfunction "2_2") (pintype "passive"))
      (node (ref "C130") (pin "2") (pinfunction "2_2") (pintype "passive"))
      (node (ref "C34") (pin "1") (pinfunction "1_1") (pintype "passive"))
      (node (ref "C37") (pin "1") (pinfunction "1_1") (pintype "passive"))
      (node (ref "C39") (pin "1") (pinfunction "1_1") (pintype "passive"))
      (node (ref "C56") (pin "1") (pinfunction "1_1") (pintype "passive"))
      (node (ref "C57") (pin "1") (pinfunction "1_1") (pintype "passive"))
      (node (ref "C58") (pin "1") (pinfunction "1_1") (pintype "passive"))
      (node (ref "C59") (pin "1") (pinfunction "1_1") (pintype "passive"))
      (node (ref "C60") (pin "2") (pinfunction "2_2") (pintype "passive"))
      (node (ref "C61") (pin "1") (pinfunction "1_1") (pintype "passive"))
      (node (ref "C63") (pin "2") (pinfunction "2_2") (pintype "passive"))
      (node (ref "C64") (pin "1") (pinfunction "1_1") (pintype "passive"))
      (node (ref "C66") (pin "1") (pinfunction "1_1") (pintype "passive"))
      (node (ref "C67") (pin "1") (pinfunction "1_1") (pintype "passive"))
      (node (ref "C68") (pin "1") (pinfunction "1_1") (pintype "passive"))
      (node (ref "C70") (pin "2") (pinfunction "2_2") (pintype "passive"))
      (node (ref "C82") (pin "2") (pinfunction "2_2") (pintype "passive"))
      (node (ref "C83") (pin "2") (pinfunction "2_2") (pintype "passive"))
      (node (ref "C84") (pin "2") (pinfunction "2_2") (pintype "passive"))
      (node (ref "C85") (pin "2") (pinfunction "2_2") (pintype "passive"))
      (node (ref "L17") (pin "1") (pinfunction "1_1") (pintype "passive"))
      (node (ref "L18") (pin "1") (pinfunction "1_1") (pintype "passive"))
      (node (ref "L19") (pin "1") (pinfunction "1_1") (pintype "passive"))
      (node (ref "L20") (pin "1") (pinfunction "1_1") (pintype "passive"))
      (node (ref "L21") (pin "1") (pinfunction "1_1") (pintype "passive"))
      (node (ref "L25") (pin "1") (pinfunction "1_1") (pintype "passive"))
      (node (ref "P10") (pin "30") (pinfunction "30_30") (pintype "passive"))
      (node (ref "P2") (pin "4") (pinfunction "4_4") (pintype "passive"))
      (node (ref "P4") (pin "4") (pinfunction "4_4") (pintype "passive"))
      (node (ref "P5") (pin "4") (pinfunction "4_4") (pintype "passive"))
      (node (ref "R36") (pin "2") (pinfunction "2_2") (pintype "passive"))
      (node (ref "R37") (pin "2") (pinfunction "2_2") (pintype "passive"))
      (node (ref "R38") (pin "2") (pinfunction "2_2") (pintype "passive"))
      (node (ref "R39") (pin "2") (pinfunction "2_2") (pintype "passive"))
      (node (ref "R40") (pin "2") (pinfunction "2_2") (pintype "passive"))
      (node (ref "R41") (pin "1") (pinfunction "1_1") (pintype "passive"))
      (node (ref "R43") (pin "2") (pinfunction "2_2") (pintype "passive"))
      (node (ref "R45") (pin "2") (pinfunction "2_2") (pintype "passive"))
      (node (ref "R50") (pin "2") (pinfunction "2_2") (pintype "passive"))
      (node (ref "R58") (pin "1") (pinfunction "1_1") (pintype "passive"))
      (node (ref "R59") (pin "2") (pinfunction "2_2") (pintype "passive"))
      (node (ref "R61") (pin "2") (pinfunction "2_2") (pintype "passive"))
      (node (ref "T2") (pin "3") (pinfunction "Vout_3") (pintype "passive"))
      (node (ref "T3") (pin "3") (pinfunction "VIN_3") (pintype "passive"))
      (node (ref "T4") (pin "3") (pinfunction "VIN_3") (pintype "passive"))
      (node (ref "U4") (pin "109") (pinfunction "VCCIO3_109") (pintype "power_in"))
      (node (ref "U4") (pin "117") (pinfunction "IO,_VREFB3N1_117") (pintype "bidirectional"))
      (node (ref "U4") (pin "122") (pinfunction "VCCIO3_122") (pintype "power_in"))
      (node (ref "U4") (pin "13") (pinfunction "IO,_VREFB1N0_13") (pintype "bidirectional"))
      (node (ref "U4") (pin "136") (pinfunction "VCCIO3_136") (pintype "power_in"))
      (node (ref "U4") (pin "145") (pinfunction "IO,_VREFB3N0_145") (pintype "bidirectional"))
      (node (ref "U4") (pin "148") (pinfunction "VCCIO3_148") (pintype "power_in"))
      (node (ref "U4") (pin "166") (pinfunction "VCCIO2_166") (pintype "power_in"))
      (node (ref "U4") (pin "170") (pinfunction "IO,_VREFB2N0_170") (pintype "bidirectional"))
      (node (ref "U4") (pin "172") (pinfunction "VCCIO2_172") (pintype "power_in"))
      (node (ref "U4") (pin "183") (pinfunction "VCCIO2_183") (pintype "power_in"))
      (node (ref "U4") (pin "192") (pinfunction "IO,_VREFB2N1_192") (pintype "bidirectional"))
      (node (ref "U4") (pin "194") (pinfunction "VCCIO2_194") (pintype "power_in"))
      (node (ref "U4") (pin "202") (pinfunction "VCCIO2_202") (pintype "power_in"))
      (node (ref "U4") (pin "29") (pinfunction "VCCIO1_29") (pintype "power_in"))
      (node (ref "U4") (pin "37") (pinfunction "IO,_VREFB1N1_37") (pintype "bidirectional"))
      (node (ref "U4") (pin "42") (pinfunction "VCCIO1_42") (pintype "power_in"))
      (node (ref "U4") (pin "62") (pinfunction "VCCIO4_62") (pintype "power_in"))
      (node (ref "U4") (pin "67") (pinfunction "IO,_VREFB4N1_67") (pintype "bidirectional"))
      (node (ref "U4") (pin "7") (pinfunction "VCCIO1_7") (pintype "power_in"))
      (node (ref "U4") (pin "71") (pinfunction "VCCIO4_71") (pintype "power_in"))
      (node (ref "U4") (pin "83") (pinfunction "VCCIO4_83") (pintype "power_in"))
      (node (ref "U4") (pin "89") (pinfunction "IO,_VREFB4N0_89") (pintype "bidirectional"))
      (node (ref "U4") (pin "91") (pinfunction "VCCIO4_91") (pintype "power_in"))
      (node (ref "U4") (pin "98") (pinfunction "VCCIO4_98") (pintype "power_in"))
      (node (ref "U5") (pin "10") (pinfunction "AVDD_10") (pintype "power_in"))
      (node (ref "U5") (pin "14") (pinfunction "AVDD_14") (pintype "power_in"))
      (node (ref "U5") (pin "16") (pinfunction "AVDD_16") (pintype "power_in"))
      (node (ref "U5") (pin "18") (pinfunction "AVDD_18") (pintype "power_in"))
      (node (ref "U5") (pin "2") (pinfunction "AVDD_2") (pintype "power_in"))
      (node (ref "U5") (pin "23") (pinfunction "AVDD_23") (pintype "power_in"))
      (node (ref "U5") (pin "24") (pinfunction "AVDD_24") (pintype "power_in"))
      (node (ref "U5") (pin "3") (pinfunction "AVDD_3") (pintype "power_in"))
      (node (ref "U5") (pin "46") (pinfunction "IOVDD_46") (pintype "bidirectional"))
      (node (ref "U5") (pin "61") (pinfunction "CLKVDD_61") (pintype "passive"))
      (node (ref "U5") (pin "8") (pinfunction "AVDD_8") (pintype "passive"))
      (node (ref "U5") (pin "80") (pinfunction "IOVDD_80") (pintype "power_in"))
      (node (ref "U6") (pin "3") (pinfunction "VCC_3") (pintype "power_in"))
      (node (ref "U6") (pin "7") (pinfunction "VCC_7") (pintype "power_in"))
      (node (ref "U6") (pin "8") (pinfunction "VCC_8") (pintype "power_in"))
      (node (ref "U7") (pin "100") (pinfunction "VDD_3_100") (pintype "power_in"))
      (node (ref "U7") (pin "11") (pinfunction "VDD_5_11") (pintype "power_in"))
      (node (ref "U7") (pin "28") (pinfunction "VDD_4_28") (pintype "power_in"))
      (node (ref "U7") (pin "50") (pinfunction "VDD_1_50") (pintype "power_in"))
      (node (ref "U7") (pin "75") (pinfunction "VDD_2_75") (pintype "power_in"))
    )
    (net (code "258") (name "VCC3_3_TCXO") (class "Default")
      (node (ref "C1") (pin "2") (pinfunction "2_2") (pintype "passive"))
      (node (ref "C3") (pin "1") (pinfunction "1_1") (pintype "passive"))
      (node (ref "L18") (pin "2") (pinfunction "2_2") (pintype "passive"))
      (node (ref "L2") (pin "1") (pinfunction "1_1") (pintype "passive"))
    )
    (net (code "259") (name "VOUT3_3_4360") (class "Default")
      (node (ref "L12") (pin "2") (pinfunction "2_2") (pintype "passive"))
      (node (ref "L13") (pin "2") (pinfunction "2_2") (pintype "passive"))
      (node (ref "L21") (pin "2") (pinfunction "2_2") (pintype "passive"))
    )
    (net (code "260") (name "VVCO3_3_4360") (class "Default")
      (node (ref "C12") (pin "1") (pinfunction "1_1") (pintype "passive"))
      (node (ref "C14") (pin "1") (pinfunction "1_1") (pintype "passive"))
      (node (ref "C28") (pin "1") (pinfunction "1_1") (pintype "passive"))
      (node (ref "C29") (pin "1") (pinfunction "1_1") (pintype "passive"))
      (node (ref "L20") (pin "2") (pinfunction "2_2") (pintype "passive"))
      (node (ref "U1") (pin "6") (pinfunction "V_VCO_6") (pintype "passive"))
    )
    (net (code "261") (name "unconnected-(LL1-SecCT-Pad2)") (class "Default")
      (node (ref "LL1") (pin "2") (pinfunction "SecCT_2") (pintype "passive"))
    )
    (net (code "262") (name "unconnected-(LL2-SecCT-Pad2)") (class "Default")
      (node (ref "LL2") (pin "2") (pinfunction "SecCT_2") (pintype "passive"))
    )
    (net (code "263") (name "unconnected-(P2-Pad6)") (class "Default")
      (node (ref "P2") (pin "6") (pinfunction "6_6") (pintype "passive"))
    )
    (net (code "264") (name "unconnected-(P2-Pad7)") (class "Default")
      (node (ref "P2") (pin "7") (pinfunction "7_7") (pintype "passive"))
    )
    (net (code "265") (name "unconnected-(P2-Pad8)") (class "Default")
      (node (ref "P2") (pin "8") (pinfunction "8_8") (pintype "passive"))
    )
    (net (code "266") (name "unconnected-(P3-Pad2)") (class "Default")
      (node (ref "P3") (pin "2") (pinfunction "2_2") (pintype "passive"))
    )
    (net (code "267") (name "unconnected-(U2-NC1-Pad1)") (class "Default")
      (node (ref "U2") (pin "1") (pinfunction "NC1_1") (pintype "passive"))
    )
    (net (code "268") (name "unconnected-(U2-NC6-Pad6)") (class "Default")
      (node (ref "U2") (pin "6") (pinfunction "NC6_6") (pintype "passive"))
    )
    (net (code "269") (name "unconnected-(U2-NC7-Pad7)") (class "Default")
      (node (ref "U2") (pin "7") (pinfunction "NC7_7") (pintype "passive"))
    )
    (net (code "270") (name "unconnected-(U2-NC13-Pad13)") (class "Default")
      (node (ref "U2") (pin "13") (pinfunction "NC13_13") (pintype "passive"))
    )
    (net (code "271") (name "unconnected-(U2-NC15-Pad15)") (class "Default")
      (node (ref "U2") (pin "15") (pinfunction "NC15_15") (pintype "passive"))
    )
    (net (code "272") (name "unconnected-(U4A-IO,_DQ1L5{slash}_-Pad34)") (class "Default")
      (node (ref "U4") (pin "34") (pinfunction "IO,_DQ1L5/__34") (pintype "bidirectional"))
    )
    (net (code "273") (name "unconnected-(U4A-IO,_LVDS0n-Pad45)") (class "Default")
      (node (ref "U4") (pin "45") (pinfunction "IO,_LVDS0n_45") (pintype "bidirectional"))
    )
    (net (code "274") (name "unconnected-(U4A-IO,_LVDS0p-Pad44)") (class "Default")
      (node (ref "U4") (pin "44") (pinfunction "IO,_LVDS0p_44") (pintype "bidirectional"))
    )
    (net (code "275") (name "unconnected-(U4A-IO,_LVDS2n,_(DM1L{slash}BWS#1L){slash}_-Pad41)") (class "Default")
      (node (ref "U4") (pin "41") (pinfunction "IO,_LVDS2n,_(DM1L/BWS#1L)/__41") (pintype "bidirectional"))
    )
    (net (code "276") (name "unconnected-(U4A-IO,_LVDS2p,_DQ1L8{slash}_-Pad40)") (class "Default")
      (node (ref "U4") (pin "40") (pinfunction "IO,_LVDS2p,_DQ1L8/__40") (pintype "bidirectional"))
    )
    (net (code "277") (name "unconnected-(U4A-IO,_LVDS3n,_DQ1L7{slash}_-Pad39)") (class "Default")
      (node (ref "U4") (pin "39") (pinfunction "IO,_LVDS3n,_DQ1L7/__39") (pintype "bidirectional"))
    )
    (net (code "278") (name "unconnected-(U4A-IO,_LVDS5p,_DQ1L6{slash}_-Pad35)") (class "Default")
      (node (ref "U4") (pin "35") (pinfunction "IO,_LVDS5p,_DQ1L6/__35") (pintype "bidirectional"))
    )
    (net (code "279") (name "unconnected-(U4A-IO,_LVDS6n,_DQ1L4{slash}_-Pad33)") (class "Default")
      (node (ref "U4") (pin "33") (pinfunction "IO,_LVDS6n,_DQ1L4/__33") (pintype "bidirectional"))
    )
    (net (code "280") (name "unconnected-(U4A-IO,_LVDS7n-Pad31)") (class "Default")
      (node (ref "U4") (pin "31") (pinfunction "IO,_LVDS7n_31") (pintype "bidirectional"))
    )
    (net (code "281") (name "unconnected-(U4A-IO,_LVDS7p,_(DPCLK1{slash}DQS1L){slash}(DPCLK1{slash}DQS1L)-Pad30)") (class "Default")
      (node (ref "U4") (pin "30") (pinfunction "IO,_LVDS7p,_(DPCLK1/DQS1L)/(DPCLK1/DQS1L)_30") (pintype "bidirectional"))
    )
    (net (code "282") (name "unconnected-(U4A-IO,_LVDS8n-Pad15)") (class "Default")
      (node (ref "U4") (pin "15") (pinfunction "IO,_LVDS8n_15") (pintype "bidirectional"))
    )
    (net (code "283") (name "unconnected-(U4A-IO,_LVDS8p,_(DPCLK0{slash}DQS0L){slash}(DPCLK0{slash}DQS0L)-Pad14)") (class "Default")
      (node (ref "U4") (pin "14") (pinfunction "IO,_LVDS8p,_(DPCLK0/DQS0L)/(DPCLK0/DQS0L)_14") (pintype "bidirectional"))
    )
    (net (code "284") (name "unconnected-(U4A-IO,_LVDS12n,_DQ1L3{slash}_-Pad12)") (class "Default")
      (node (ref "U4") (pin "12") (pinfunction "IO,_LVDS12n,_DQ1L3/__12") (pintype "bidirectional"))
    )
    (net (code "285") (name "unconnected-(U4A-IO,_LVDS12p,_DQ1L2{slash}_-Pad11)") (class "Default")
      (node (ref "U4") (pin "11") (pinfunction "IO,_LVDS12p,_DQ1L2/__11") (pintype "bidirectional"))
    )
    (net (code "286") (name "unconnected-(U4A-IO,_LVDS13n,_DQ1L1{slash}_-Pad10)") (class "Default")
      (node (ref "U4") (pin "10") (pinfunction "IO,_LVDS13n,_DQ1L1/__10") (pintype "bidirectional"))
    )
    (net (code "287") (name "unconnected-(U4A-IO,_LVDS13p,_DQ1L0{slash}_-Pad8)") (class "Default")
      (node (ref "U4") (pin "8") (pinfunction "IO,_LVDS13p,_DQ1L0/__8") (pintype "bidirectional"))
    )
    (net (code "288") (name "unconnected-(U4A-IO,_LVDS14n-Pad6)") (class "Default")
      (node (ref "U4") (pin "6") (pinfunction "IO,_LVDS14n_6") (pintype "bidirectional"))
    )
    (net (code "289") (name "unconnected-(U4A-IO,_LVDS14p-Pad5)") (class "Default")
      (node (ref "U4") (pin "5") (pinfunction "IO,_LVDS14p_5") (pintype "bidirectional"))
    )
    (net (code "290") (name "unconnected-(U4A-IO,_LVDS15n_(CLKUSR)-Pad4)") (class "Default")
      (node (ref "U4") (pin "4") (pinfunction "IO,_LVDS15n_(CLKUSR)_4") (pintype "bidirectional"))
    )
    (net (code "291") (name "unconnected-(U4A-IO,_LVDS15p_(CRC_ERROR)-Pad3)") (class "Default")
      (node (ref "U4") (pin "3") (pinfunction "IO,_LVDS15p_(CRC_ERROR)_3") (pintype "bidirectional"))
    )
    (net (code "292") (name "unconnected-(U4A-IO,_PLL1_OUTn-Pad48)") (class "Default")
      (node (ref "U4") (pin "48") (pinfunction "IO,_PLL1_OUTn_48") (pintype "bidirectional"))
    )
    (net (code "293") (name "unconnected-(U4A-IO-Pad43)") (class "Default")
      (node (ref "U4") (pin "43") (pinfunction "IO_43") (pintype "bidirectional"))
    )
    (net (code "294") (name "unconnected-(U4A-IO-Pad46)") (class "Default")
      (node (ref "U4") (pin "46") (pinfunction "IO_46") (pintype "bidirectional"))
    )
    (net (code "295") (name "unconnected-(U4B-IO,_LVDS16n-Pad208)") (class "Default")
      (node (ref "U4") (pin "208") (pinfunction "IO,_LVDS16n_208") (pintype "bidirectional"))
    )
    (net (code "296") (name "unconnected-(U4B-IO,_LVDS16p,_(DM1T{slash}BWS#1T){slash}(DM1T1{slash}BWS#1T1)-Pad207)") (class "Default")
      (node (ref "U4") (pin "207") (pinfunction "IO,_LVDS16p,_(DM1T/BWS#1T)/(DM1T1/BWS#1T1)_207") (pintype "bidirectional"))
    )
    (net (code "297") (name "unconnected-(U4B-IO,_LVDS17n_(DEV_CLRn)-Pad206)") (class "Default")
      (node (ref "U4") (pin "206") (pinfunction "IO,_LVDS17n_(DEV_CLRn)_206") (pintype "bidirectional"))
    )
    (net (code "298") (name "unconnected-(U4B-IO,_LVDS17p,_DQ1T8{slash}DQ1T17-Pad205)") (class "Default")
      (node (ref "U4") (pin "205") (pinfunction "IO,_LVDS17p,_DQ1T8/DQ1T17_205") (pintype "bidirectional"))
    )
    (net (code "299") (name "unconnected-(U4B-IO,_LVDS18n,_DQ1T6{slash}DQ1T15-Pad201)") (class "Default")
      (node (ref "U4") (pin "201") (pinfunction "IO,_LVDS18n,_DQ1T6/DQ1T15_201") (pintype "bidirectional"))
    )
    (net (code "300") (name "unconnected-(U4B-IO,_LVDS18p,_DQ1T7{slash}DQ1T16-Pad203)") (class "Default")
      (node (ref "U4") (pin "203") (pinfunction "IO,_LVDS18p,_DQ1T7/DQ1T16_203") (pintype "bidirectional"))
    )
    (net (code "301") (name "unconnected-(U4B-IO,_LVDS19n-Pad199)") (class "Default")
      (node (ref "U4") (pin "199") (pinfunction "IO,_LVDS19n_199") (pintype "bidirectional"))
    )
    (net (code "302") (name "unconnected-(U4B-IO,_LVDS19p,_(DPCLK10{slash}DQS1T){slash}(DPCLK10{slash}DQS1T)-Pad200)") (class "Default")
      (node (ref "U4") (pin "200") (pinfunction "IO,_LVDS19p,_(DPCLK10/DQS1T)/(DPCLK10/DQS1T)_200") (pintype "bidirectional"))
    )
    (net (code "303") (name "unconnected-(U4B-IO,_LVDS21n-Pad197)") (class "Default")
      (node (ref "U4") (pin "197") (pinfunction "IO,_LVDS21n_197") (pintype "bidirectional"))
    )
    (net (code "304") (name "unconnected-(U4B-IO,_LVDS21p-Pad198)") (class "Default")
      (node (ref "U4") (pin "198") (pinfunction "IO,_LVDS21p_198") (pintype "bidirectional"))
    )
    (net (code "305") (name "unconnected-(U4B-IO,_LVDS23n,_DQ1T4{slash}DQ1T13-Pad193)") (class "Default")
      (node (ref "U4") (pin "193") (pinfunction "IO,_LVDS23n,_DQ1T4/DQ1T13_193") (pintype "bidirectional"))
    )
    (net (code "306") (name "unconnected-(U4B-IO,_LVDS23p,_DQ1T5{slash}DQ1T14-Pad195)") (class "Default")
      (node (ref "U4") (pin "195") (pinfunction "IO,_LVDS23p,_DQ1T5/DQ1T14_195") (pintype "bidirectional"))
    )
    (net (code "307") (name "unconnected-(U4B-IO,_LVDS24n,_DQ1T2{slash}DQ1T11-Pad189)") (class "Default")
      (node (ref "U4") (pin "189") (pinfunction "IO,_LVDS24n,_DQ1T2/DQ1T11_189") (pintype "bidirectional"))
    )
    (net (code "308") (name "unconnected-(U4B-IO,_LVDS24p,_DQ1T3{slash}DQ1T12-Pad191)") (class "Default")
      (node (ref "U4") (pin "191") (pinfunction "IO,_LVDS24p,_DQ1T3/DQ1T12_191") (pintype "bidirectional"))
    )
    (net (code "309") (name "unconnected-(U4B-IO,_LVDS25n-Pad187)") (class "Default")
      (node (ref "U4") (pin "187") (pinfunction "IO,_LVDS25n_187") (pintype "bidirectional"))
    )
    (net (code "310") (name "unconnected-(U4B-IO,_LVDS25p,_DQ1T1{slash}DQ1T10-Pad188)") (class "Default")
      (node (ref "U4") (pin "188") (pinfunction "IO,_LVDS25p,_DQ1T1/DQ1T10_188") (pintype "bidirectional"))
    )
    (net (code "311") (name "unconnected-(U4B-IO,_LVDS26p,_DQ1T0{slash}DQ1T9-Pad185)") (class "Default")
      (node (ref "U4") (pin "185") (pinfunction "IO,_LVDS26p,_DQ1T0/DQ1T9_185") (pintype "bidirectional"))
    )
    (net (code "312") (name "unconnected-(U4B-IO,_LVDS28n-Pad181)") (class "Default")
      (node (ref "U4") (pin "181") (pinfunction "IO,_LVDS28n_181") (pintype "bidirectional"))
    )
    (net (code "313") (name "unconnected-(U4B-IO,_LVDS28p-Pad182)") (class "Default")
      (node (ref "U4") (pin "182") (pinfunction "IO,_LVDS28p_182") (pintype "bidirectional"))
    )
    (net (code "314") (name "unconnected-(U4B-IO,_LVDS29n,_DM0T{slash}(DM1T0{slash}BWS#1T0)-Pad179)") (class "Default")
      (node (ref "U4") (pin "179") (pinfunction "IO,_LVDS29n,_DM0T/(DM1T0/BWS#1T0)_179") (pintype "bidirectional"))
    )
    (net (code "315") (name "unconnected-(U4B-IO,_LVDS29p-Pad180)") (class "Default")
      (node (ref "U4") (pin "180") (pinfunction "IO,_LVDS29p_180") (pintype "bidirectional"))
    )
    (net (code "316") (name "unconnected-(U4B-IO,_LVDS31n,_DQ0T7{slash}DQ1T7-Pad175)") (class "Default")
      (node (ref "U4") (pin "175") (pinfunction "IO,_LVDS31n,_DQ0T7/DQ1T7_175") (pintype "bidirectional"))
    )
    (net (code "317") (name "unconnected-(U4B-IO,_LVDS31p,__{slash}DQ1T8-Pad176)") (class "Default")
      (node (ref "U4") (pin "176") (pinfunction "IO,_LVDS31p,__/DQ1T8_176") (pintype "bidirectional"))
    )
    (net (code "318") (name "unconnected-(U4B-IO,_LVDS33n,_DQ0T5{slash}DQ1T5-Pad171)") (class "Default")
      (node (ref "U4") (pin "171") (pinfunction "IO,_LVDS33n,_DQ0T5/DQ1T5_171") (pintype "bidirectional"))
    )
    (net (code "319") (name "unconnected-(U4B-IO,_LVDS33p,_DQ0T6{slash}DQ1T6-Pad173)") (class "Default")
      (node (ref "U4") (pin "173") (pinfunction "IO,_LVDS33p,_DQ0T6/DQ1T6_173") (pintype "bidirectional"))
    )
    (net (code "320") (name "unconnected-(U4B-IO,_LVDS34n-Pad168)") (class "Default")
      (node (ref "U4") (pin "168") (pinfunction "IO,_LVDS34n_168") (pintype "bidirectional"))
    )
    (net (code "321") (name "unconnected-(U4B-IO,_LVDS34p,_(DPCLK8{slash}DQS0T){slash}(DPCLK8{slash}DQS0T)-Pad169)") (class "Default")
      (node (ref "U4") (pin "169") (pinfunction "IO,_LVDS34p,_(DPCLK8/DQS0T)/(DPCLK8/DQS0T)_169") (pintype "bidirectional"))
    )
    (net (code "322") (name "unconnected-(U4B-IO,_LVDS35n,_DQ0T3{slash}DQ1T3-Pad164)") (class "Default")
      (node (ref "U4") (pin "164") (pinfunction "IO,_LVDS35n,_DQ0T3/DQ1T3_164") (pintype "bidirectional"))
    )
    (net (code "323") (name "unconnected-(U4B-IO,_LVDS35p,_DQ0T4{slash}DQ1T4-Pad165)") (class "Default")
      (node (ref "U4") (pin "165") (pinfunction "IO,_LVDS35p,_DQ0T4/DQ1T4_165") (pintype "bidirectional"))
    )
    (net (code "324") (name "unconnected-(U4B-IO,_LVDS36n,_DQ0T1{slash}DQ1T1-Pad162)") (class "Default")
      (node (ref "U4") (pin "162") (pinfunction "IO,_LVDS36n,_DQ0T1/DQ1T1_162") (pintype "bidirectional"))
    )
    (net (code "325") (name "unconnected-(U4B-IO,_LVDS36p,_DQ0T2{slash}DQ1T2-Pad163)") (class "Default")
      (node (ref "U4") (pin "163") (pinfunction "IO,_LVDS36p,_DQ0T2/DQ1T2_163") (pintype "bidirectional"))
    )
    (net (code "326") (name "unconnected-(U4B-IO,_LVDS37n-Pad160)") (class "Default")
      (node (ref "U4") (pin "160") (pinfunction "IO,_LVDS37n_160") (pintype "bidirectional"))
    )
    (net (code "327") (name "unconnected-(U4B-IO,_LVDS37p,_DQ0T0{slash}DQ1T0-Pad161)") (class "Default")
      (node (ref "U4") (pin "161") (pinfunction "IO,_LVDS37p,_DQ0T0/DQ1T0_161") (pintype "bidirectional"))
    )
    (net (code "328") (name "unconnected-(U4C-IO,_DQ1R2{slash}DQ1R11-Pad118)") (class "Default")
      (node (ref "U4") (pin "118") (pinfunction "IO,_DQ1R2/DQ1R11_118") (pintype "bidirectional"))
    )
    (net (code "329") (name "unconnected-(U4C-IO,_LVDS38n-Pad149)") (class "Default")
      (node (ref "U4") (pin "149") (pinfunction "IO,_LVDS38n_149") (pintype "bidirectional"))
    )
    (net (code "330") (name "unconnected-(U4C-IO,_LVDS38p-Pad150)") (class "Default")
      (node (ref "U4") (pin "150") (pinfunction "IO,_LVDS38p_150") (pintype "bidirectional"))
    )
    (net (code "331") (name "unconnected-(U4C-IO,_LVDS39n,_DQ0R1{slash}DQ1R1-Pad146)") (class "Default")
      (node (ref "U4") (pin "146") (pinfunction "IO,_LVDS39n,_DQ0R1/DQ1R1_146") (pintype "bidirectional"))
    )
    (net (code "332") (name "unconnected-(U4C-IO,_LVDS39p,_DQ0R0{slash}DQ1R0-Pad147)") (class "Default")
      (node (ref "U4") (pin "147") (pinfunction "IO,_LVDS39p,_DQ0R0/DQ1R0_147") (pintype "bidirectional"))
    )
    (net (code "333") (name "unconnected-(U4C-IO,_LVDS42n,_DQ0R3{slash}DQ1R3-Pad143)") (class "Default")
      (node (ref "U4") (pin "143") (pinfunction "IO,_LVDS42n,_DQ0R3/DQ1R3_143") (pintype "bidirectional"))
    )
    (net (code "334") (name "unconnected-(U4C-IO,_LVDS42p,_DQ0R2{slash}DQ1R2-Pad144)") (class "Default")
      (node (ref "U4") (pin "144") (pinfunction "IO,_LVDS42p,_DQ0R2/DQ1R2_144") (pintype "bidirectional"))
    )
    (net (code "335") (name "unconnected-(U4C-IO,_LVDS44n,_DQ0R5{slash}DQ1R5-Pad141)") (class "Default")
      (node (ref "U4") (pin "141") (pinfunction "IO,_LVDS44n,_DQ0R5/DQ1R5_141") (pintype "bidirectional"))
    )
    (net (code "336") (name "unconnected-(U4C-IO,_LVDS44p,_DQ0R4{slash}DQ1R4-Pad142)") (class "Default")
      (node (ref "U4") (pin "142") (pinfunction "IO,_LVDS44p,_DQ0R4/DQ1R4_142") (pintype "bidirectional"))
    )
    (net (code "337") (name "unconnected-(U4C-IO,_LVDS45n,_DQ0R7{slash}DQ1R7-Pad138)") (class "Default")
      (node (ref "U4") (pin "138") (pinfunction "IO,_LVDS45n,_DQ0R7/DQ1R7_138") (pintype "bidirectional"))
    )
    (net (code "338") (name "unconnected-(U4C-IO,_LVDS45p,_DQ0R6{slash}DQ1R6-Pad139)") (class "Default")
      (node (ref "U4") (pin "139") (pinfunction "IO,_LVDS45p,_DQ0R6/DQ1R6_139") (pintype "bidirectional"))
    )
    (net (code "339") (name "unconnected-(U4C-IO,_LVDS46n,_DM0R{slash}(DM1R0{slash}BWS#1R0)-Pad135)") (class "Default")
      (node (ref "U4") (pin "135") (pinfunction "IO,_LVDS46n,_DM0R/(DM1R0/BWS#1R0)_135") (pintype "bidirectional"))
    )
    (net (code "340") (name "unconnected-(U4C-IO,_LVDS46p,__{slash}DQ1R8-Pad137)") (class "Default")
      (node (ref "U4") (pin "137") (pinfunction "IO,_LVDS46p,__/DQ1R8_137") (pintype "bidirectional"))
    )
    (net (code "341") (name "unconnected-(U4C-IO,_LVDS47n,_DQ1R0{slash}DQ1R9-Pad133)") (class "Default")
      (node (ref "U4") (pin "133") (pinfunction "IO,_LVDS47n,_DQ1R0/DQ1R9_133") (pintype "bidirectional"))
    )
    (net (code "342") (name "unconnected-(U4C-IO,_LVDS47p,_(DPCLK7{slash}DQS0R){slash}(DPCLK7{slash}DQS0R)-Pad134)") (class "Default")
      (node (ref "U4") (pin "134") (pinfunction "IO,_LVDS47p,_(DPCLK7/DQS0R)/(DPCLK7/DQS0R)_134") (pintype "bidirectional"))
    )
    (net (code "343") (name "unconnected-(U4C-IO,_LVDS48n,_DQ1R1{slash}DQ1R10-Pad127)") (class "Default")
      (node (ref "U4") (pin "127") (pinfunction "IO,_LVDS48n,_DQ1R1/DQ1R10_127") (pintype "bidirectional"))
    )
    (net (code "344") (name "unconnected-(U4C-IO,_LVDS48p,_(DPCLK6{slash}DQS1R){slash}(DPCLK6{slash}DQS1R)-Pad128)") (class "Default")
      (node (ref "U4") (pin "128") (pinfunction "IO,_LVDS48p,_(DPCLK6/DQS1R)/(DPCLK6/DQS1R)_128") (pintype "bidirectional"))
    )
    (net (code "345") (name "unconnected-(U4C-IO,_LVDS51p,_DQ1R3{slash}DQ1R12-Pad116)") (class "Default")
      (node (ref "U4") (pin "116") (pinfunction "IO,_LVDS51p,_DQ1R3/DQ1R12_116") (pintype "bidirectional"))
    )
    (net (code "346") (name "unconnected-(U4C-IO,_PLL2_OUTn-Pad152)") (class "Default")
      (node (ref "U4") (pin "152") (pinfunction "IO,_PLL2_OUTn_152") (pintype "bidirectional"))
    )
    (net (code "347") (name "unconnected-(U4D-IO,_LVDS64p-Pad81)") (class "Default")
      (node (ref "U4") (pin "81") (pinfunction "IO,_LVDS64p_81") (pintype "bidirectional"))
    )
    (net (code "348") (name "unconnected-(U4D-IO,_LVDS77n_(DEV_OE)-Pad56)") (class "Default")
      (node (ref "U4") (pin "56") (pinfunction "IO,_LVDS77n_(DEV_OE)_56") (pintype "bidirectional"))
    )
    (net (code "349") (name "unconnected-(U4I-CLK1,_LVDSCLK0n_INPUT-Pad24)") (class "Default")
      (node (ref "U4") (pin "24") (pinfunction "CLK1,_LVDSCLK0n_INPUT_24") (pintype "input"))
    )
    (net (code "350") (name "unconnected-(U4I-CLK2,_LVDSCLK1p_INPUT-Pad27)") (class "Default")
      (node (ref "U4") (pin "27") (pinfunction "CLK2,_LVDSCLK1p_INPUT_27") (pintype "input"))
    )
    (net (code "351") (name "unconnected-(U4I-CLK4,_LVDSCLK2p_INPUT-Pad132)") (class "Default")
      (node (ref "U4") (pin "132") (pinfunction "CLK4,_LVDSCLK2p_INPUT_132") (pintype "input"))
    )
    (net (code "352") (name "unconnected-(U4I-CLK5,_LVDSCLK2n_INPUT-Pad131)") (class "Default")
      (node (ref "U4") (pin "131") (pinfunction "CLK5,_LVDSCLK2n_INPUT_131") (pintype "input"))
    )
    (net (code "353") (name "unconnected-(U4I-CLK6,_LVDSCLK3p_INPUT-Pad130)") (class "Default")
      (node (ref "U4") (pin "130") (pinfunction "CLK6,_LVDSCLK3p_INPUT_130") (pintype "input"))
    )
    (net (code "354") (name "unconnected-(U4I-CLK7,_LVDSCLK3n_INPUT-Pad129)") (class "Default")
      (node (ref "U4") (pin "129") (pinfunction "CLK7,_LVDSCLK3n_INPUT_129") (pintype "input"))
    )
    (net (code "355") (name "unconnected-(U5-CLK1-Pad59)") (class "Default")
      (node (ref "U5") (pin "59") (pinfunction "CLK1_59") (pintype "bidirectional"))
    )
    (net (code "356") (name "unconnected-(U5-CLK1C-Pad60)") (class "Default")
      (node (ref "U5") (pin "60") (pinfunction "CLK1C_60") (pintype "bidirectional"))
    )
    (net (code "357") (name "unconnected-(U5-LPF-Pad66)") (class "Default")
      (node (ref "U5") (pin "66") (pinfunction "LPF_66") (pintype "bidirectional"))
    )
    (net (code "358") (name "unconnected-(U5-PHSTR-Pad94)") (class "Default")
      (node (ref "U5") (pin "94") (pinfunction "PHSTR_94") (pintype "bidirectional"))
    )
    (net (code "359") (name "unconnected-(U5-SLEEP-Pad96)") (class "Default")
      (node (ref "U5") (pin "96") (pinfunction "SLEEP_96") (pintype "bidirectional"))
    )
    (net (code "360") (name "unconnected-(U7-NC-Pad73)") (class "Default")
      (node (ref "U7") (pin "73") (pinfunction "NC_73") (pintype "passive"))
    )
  )
)
